# Open-Source_Control_V2_R2.net
KiCad netlist of a schematic drawn in EAGLE
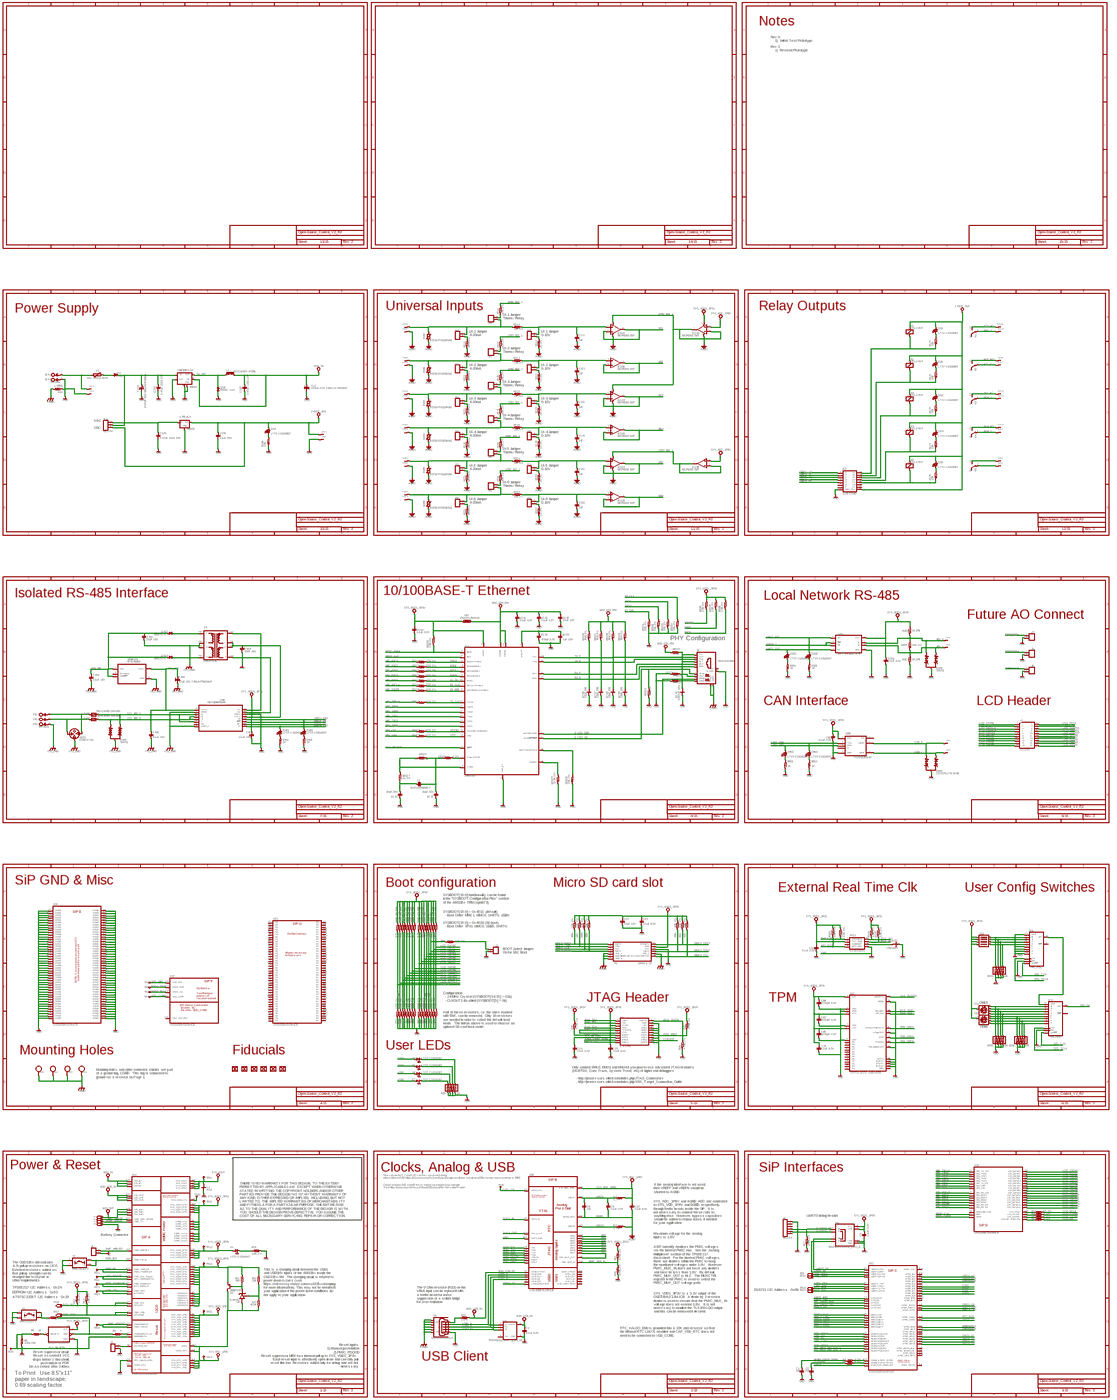
[diagram p0: schematic, sheet 1, overview]
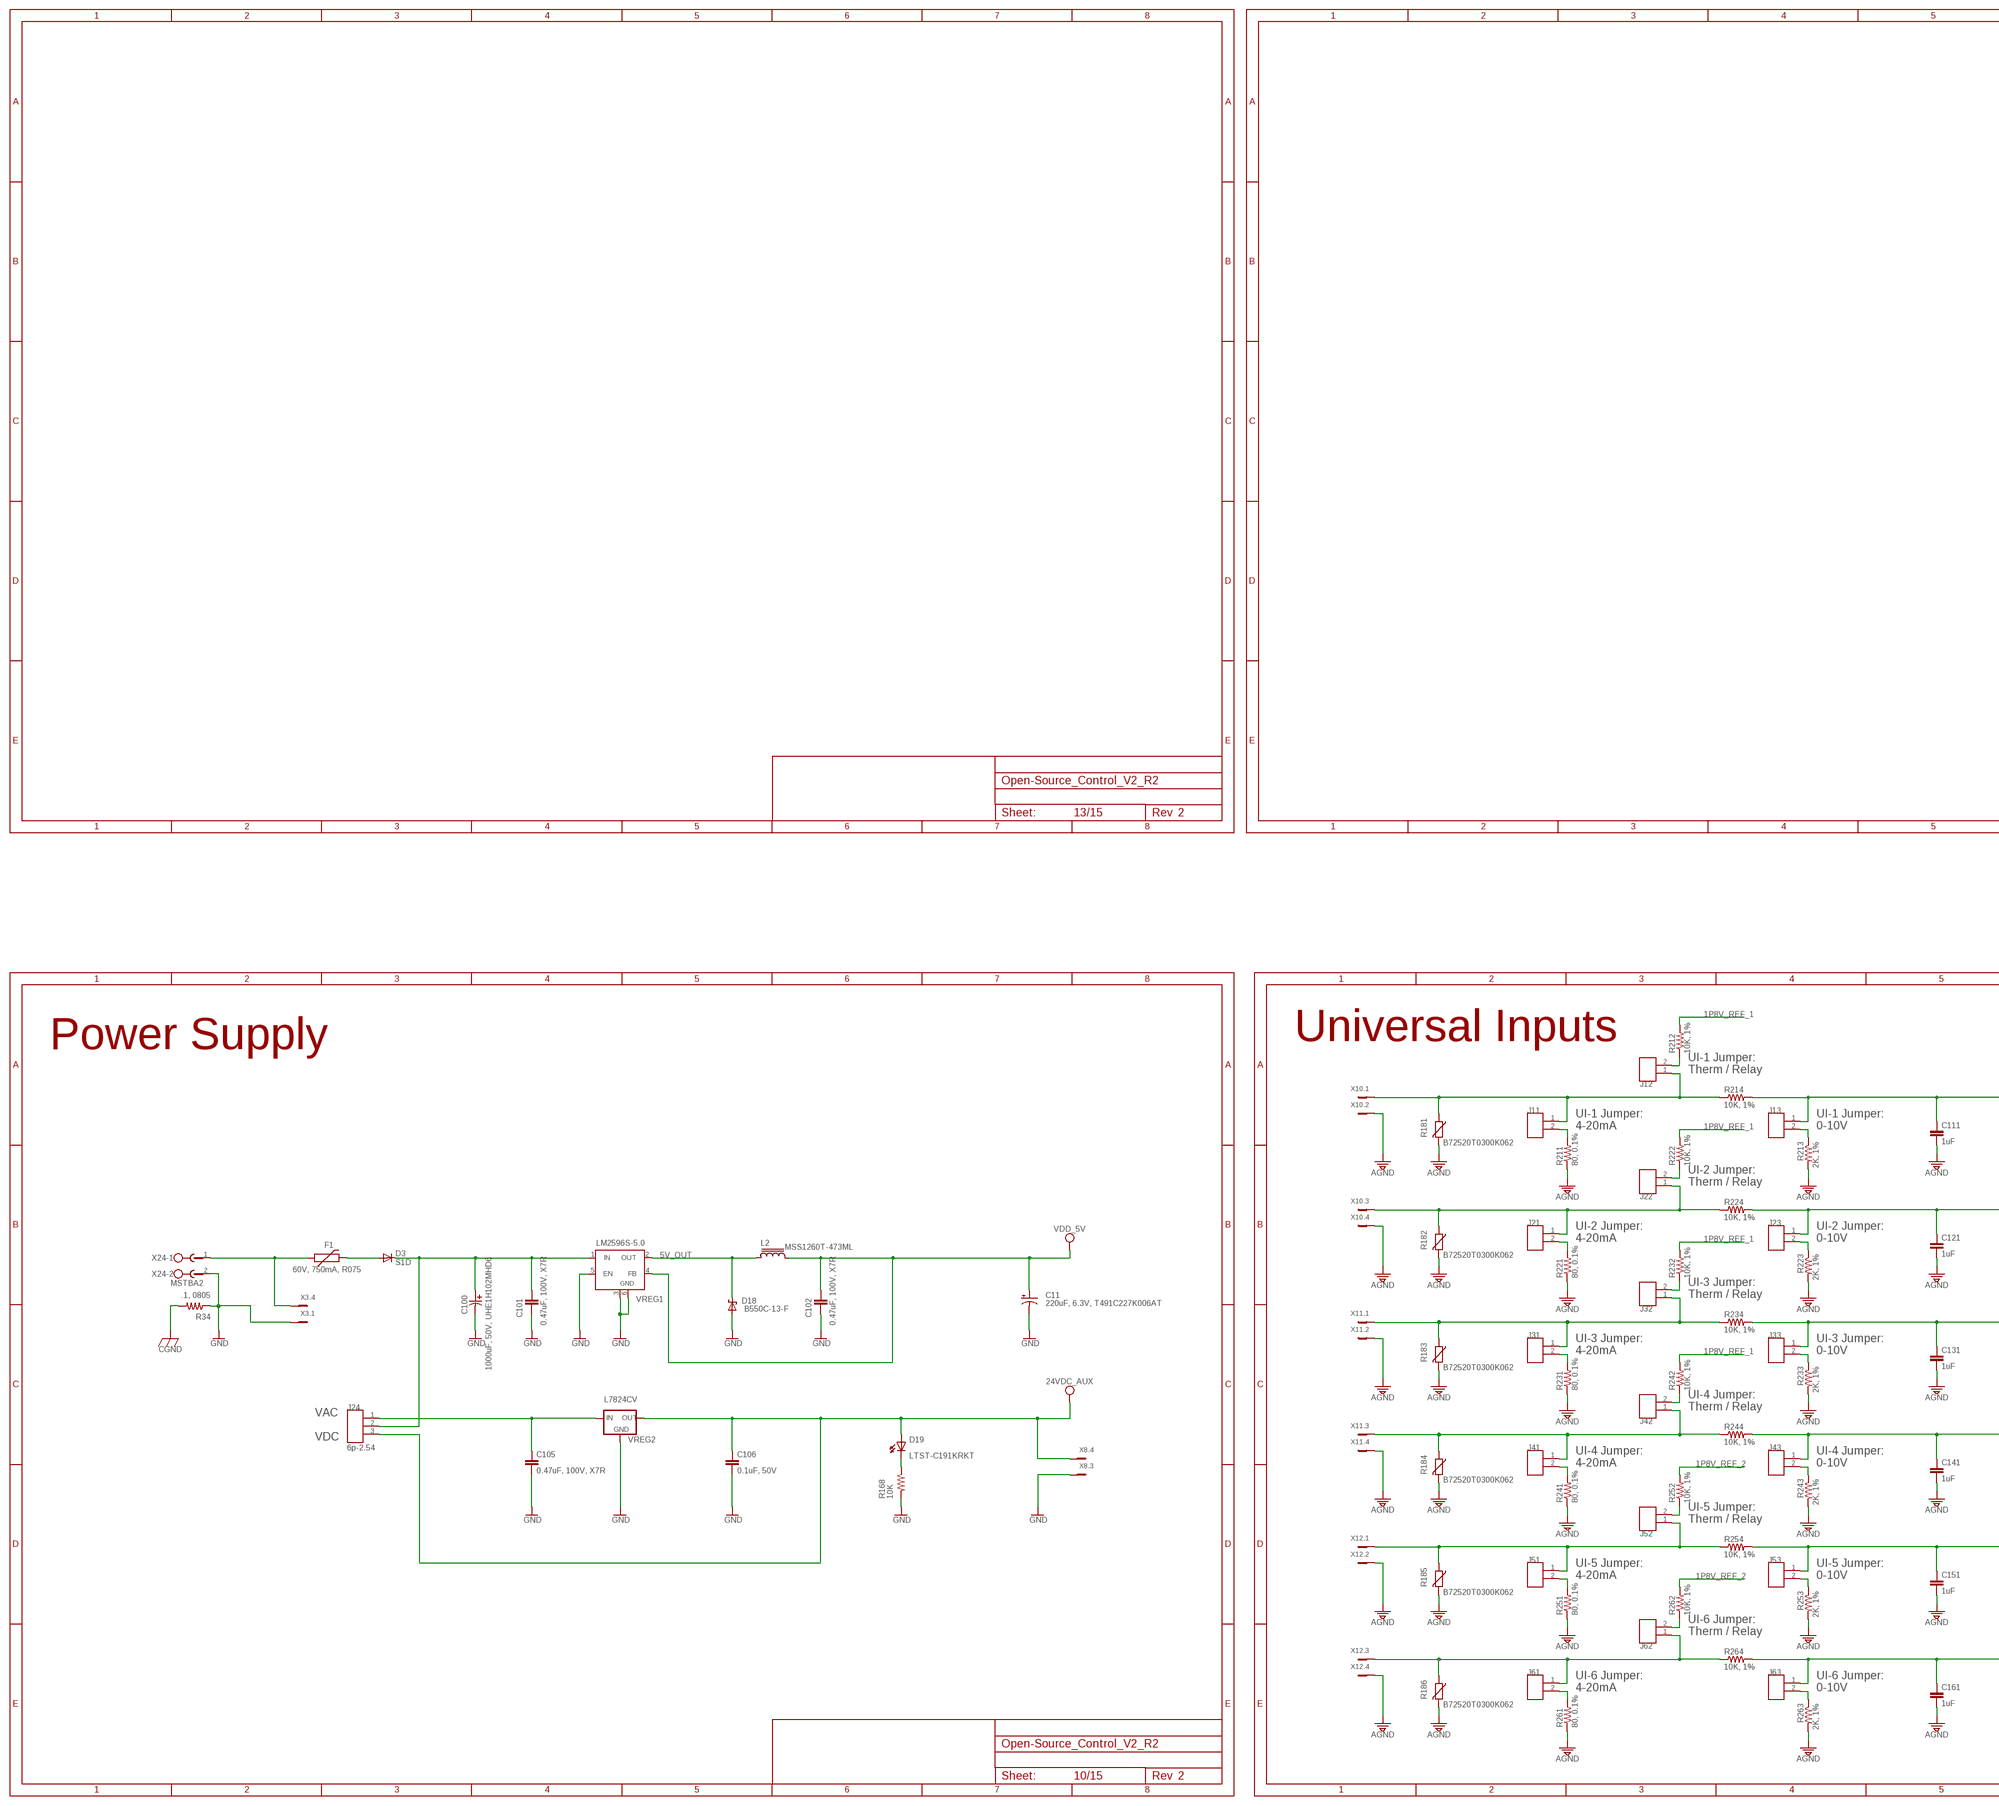
[diagram p1: schematic, sheet 1, part 1 of 6]
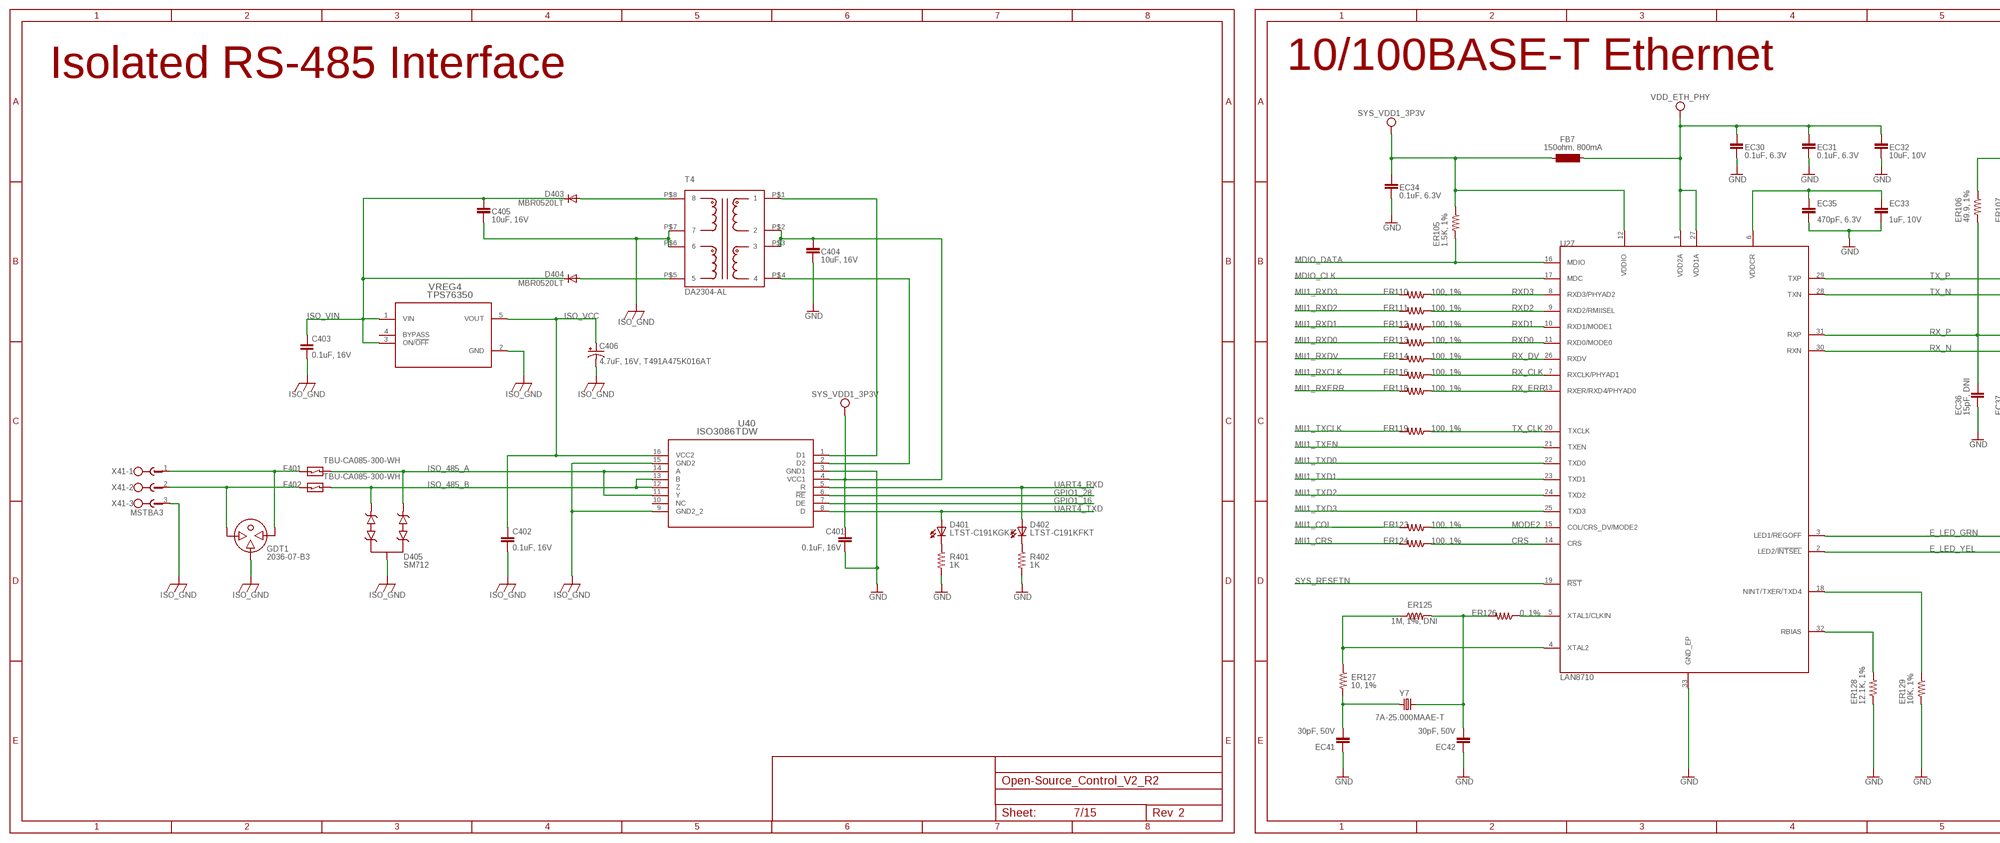
[diagram p2: schematic, sheet 1, part 2 of 6]
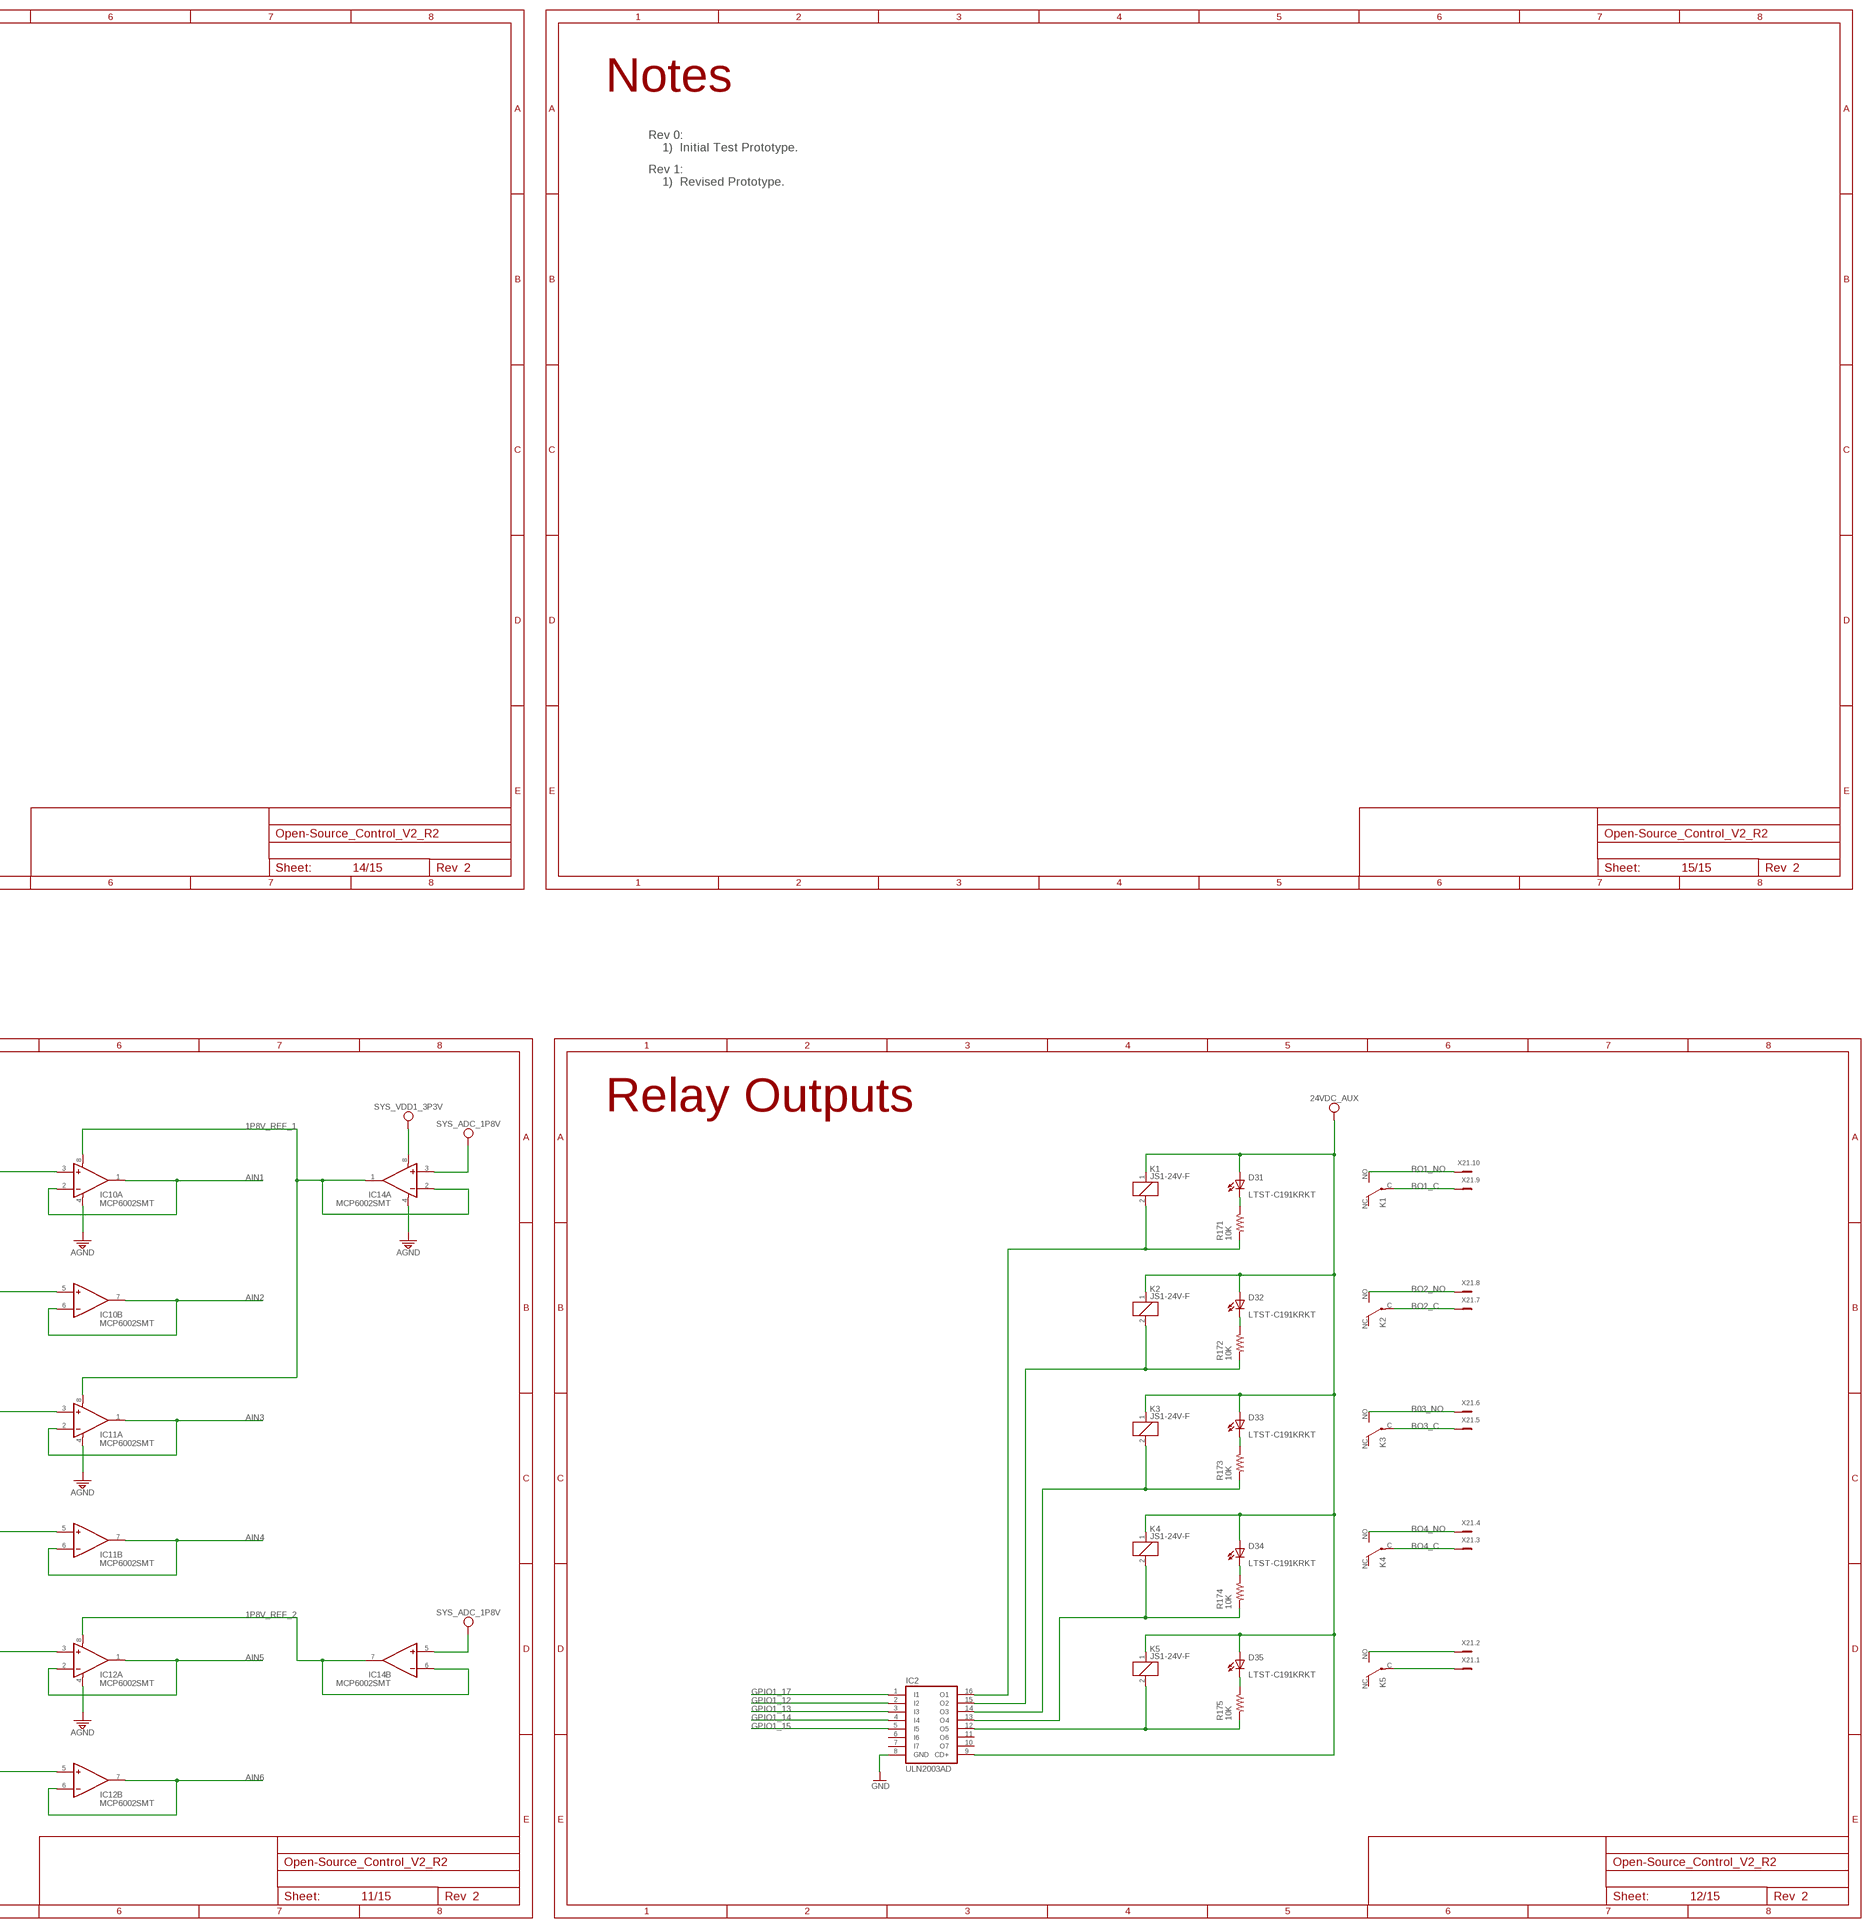
[diagram p3: schematic, sheet 1, part 3 of 6]
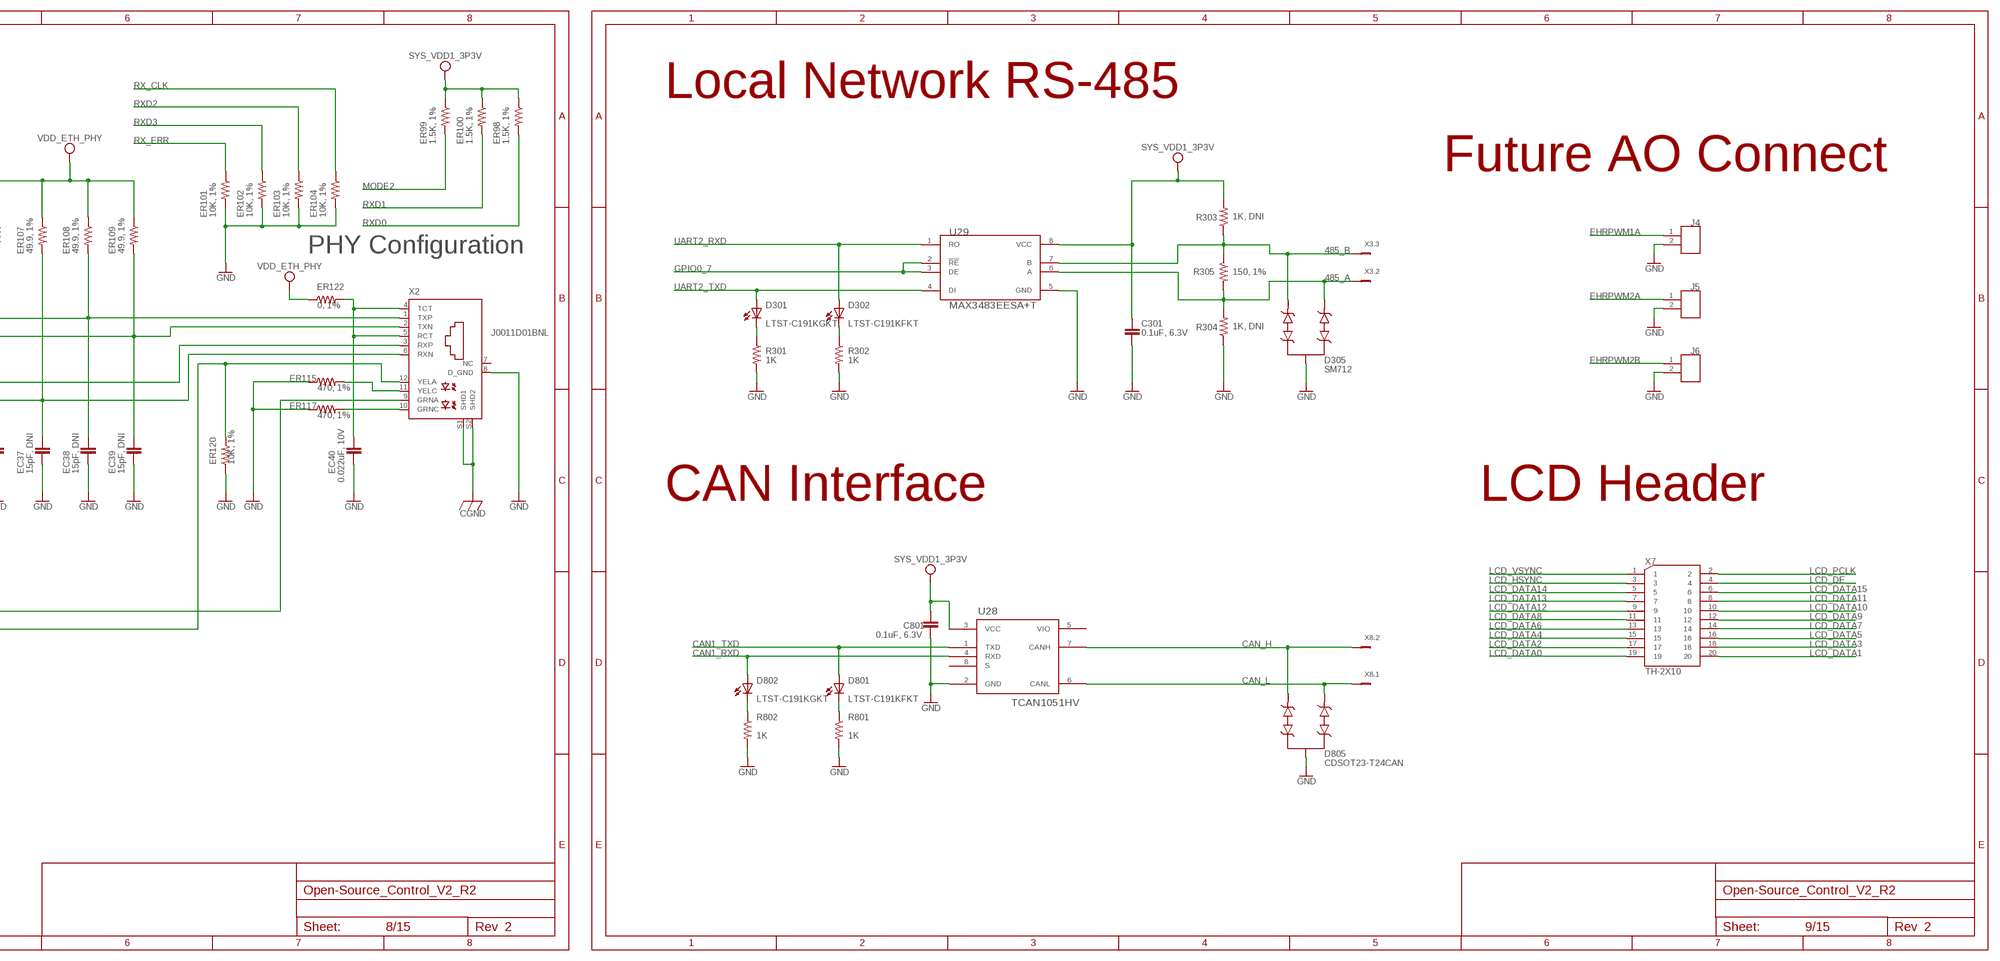
[diagram p4: schematic, sheet 1, part 4 of 6]
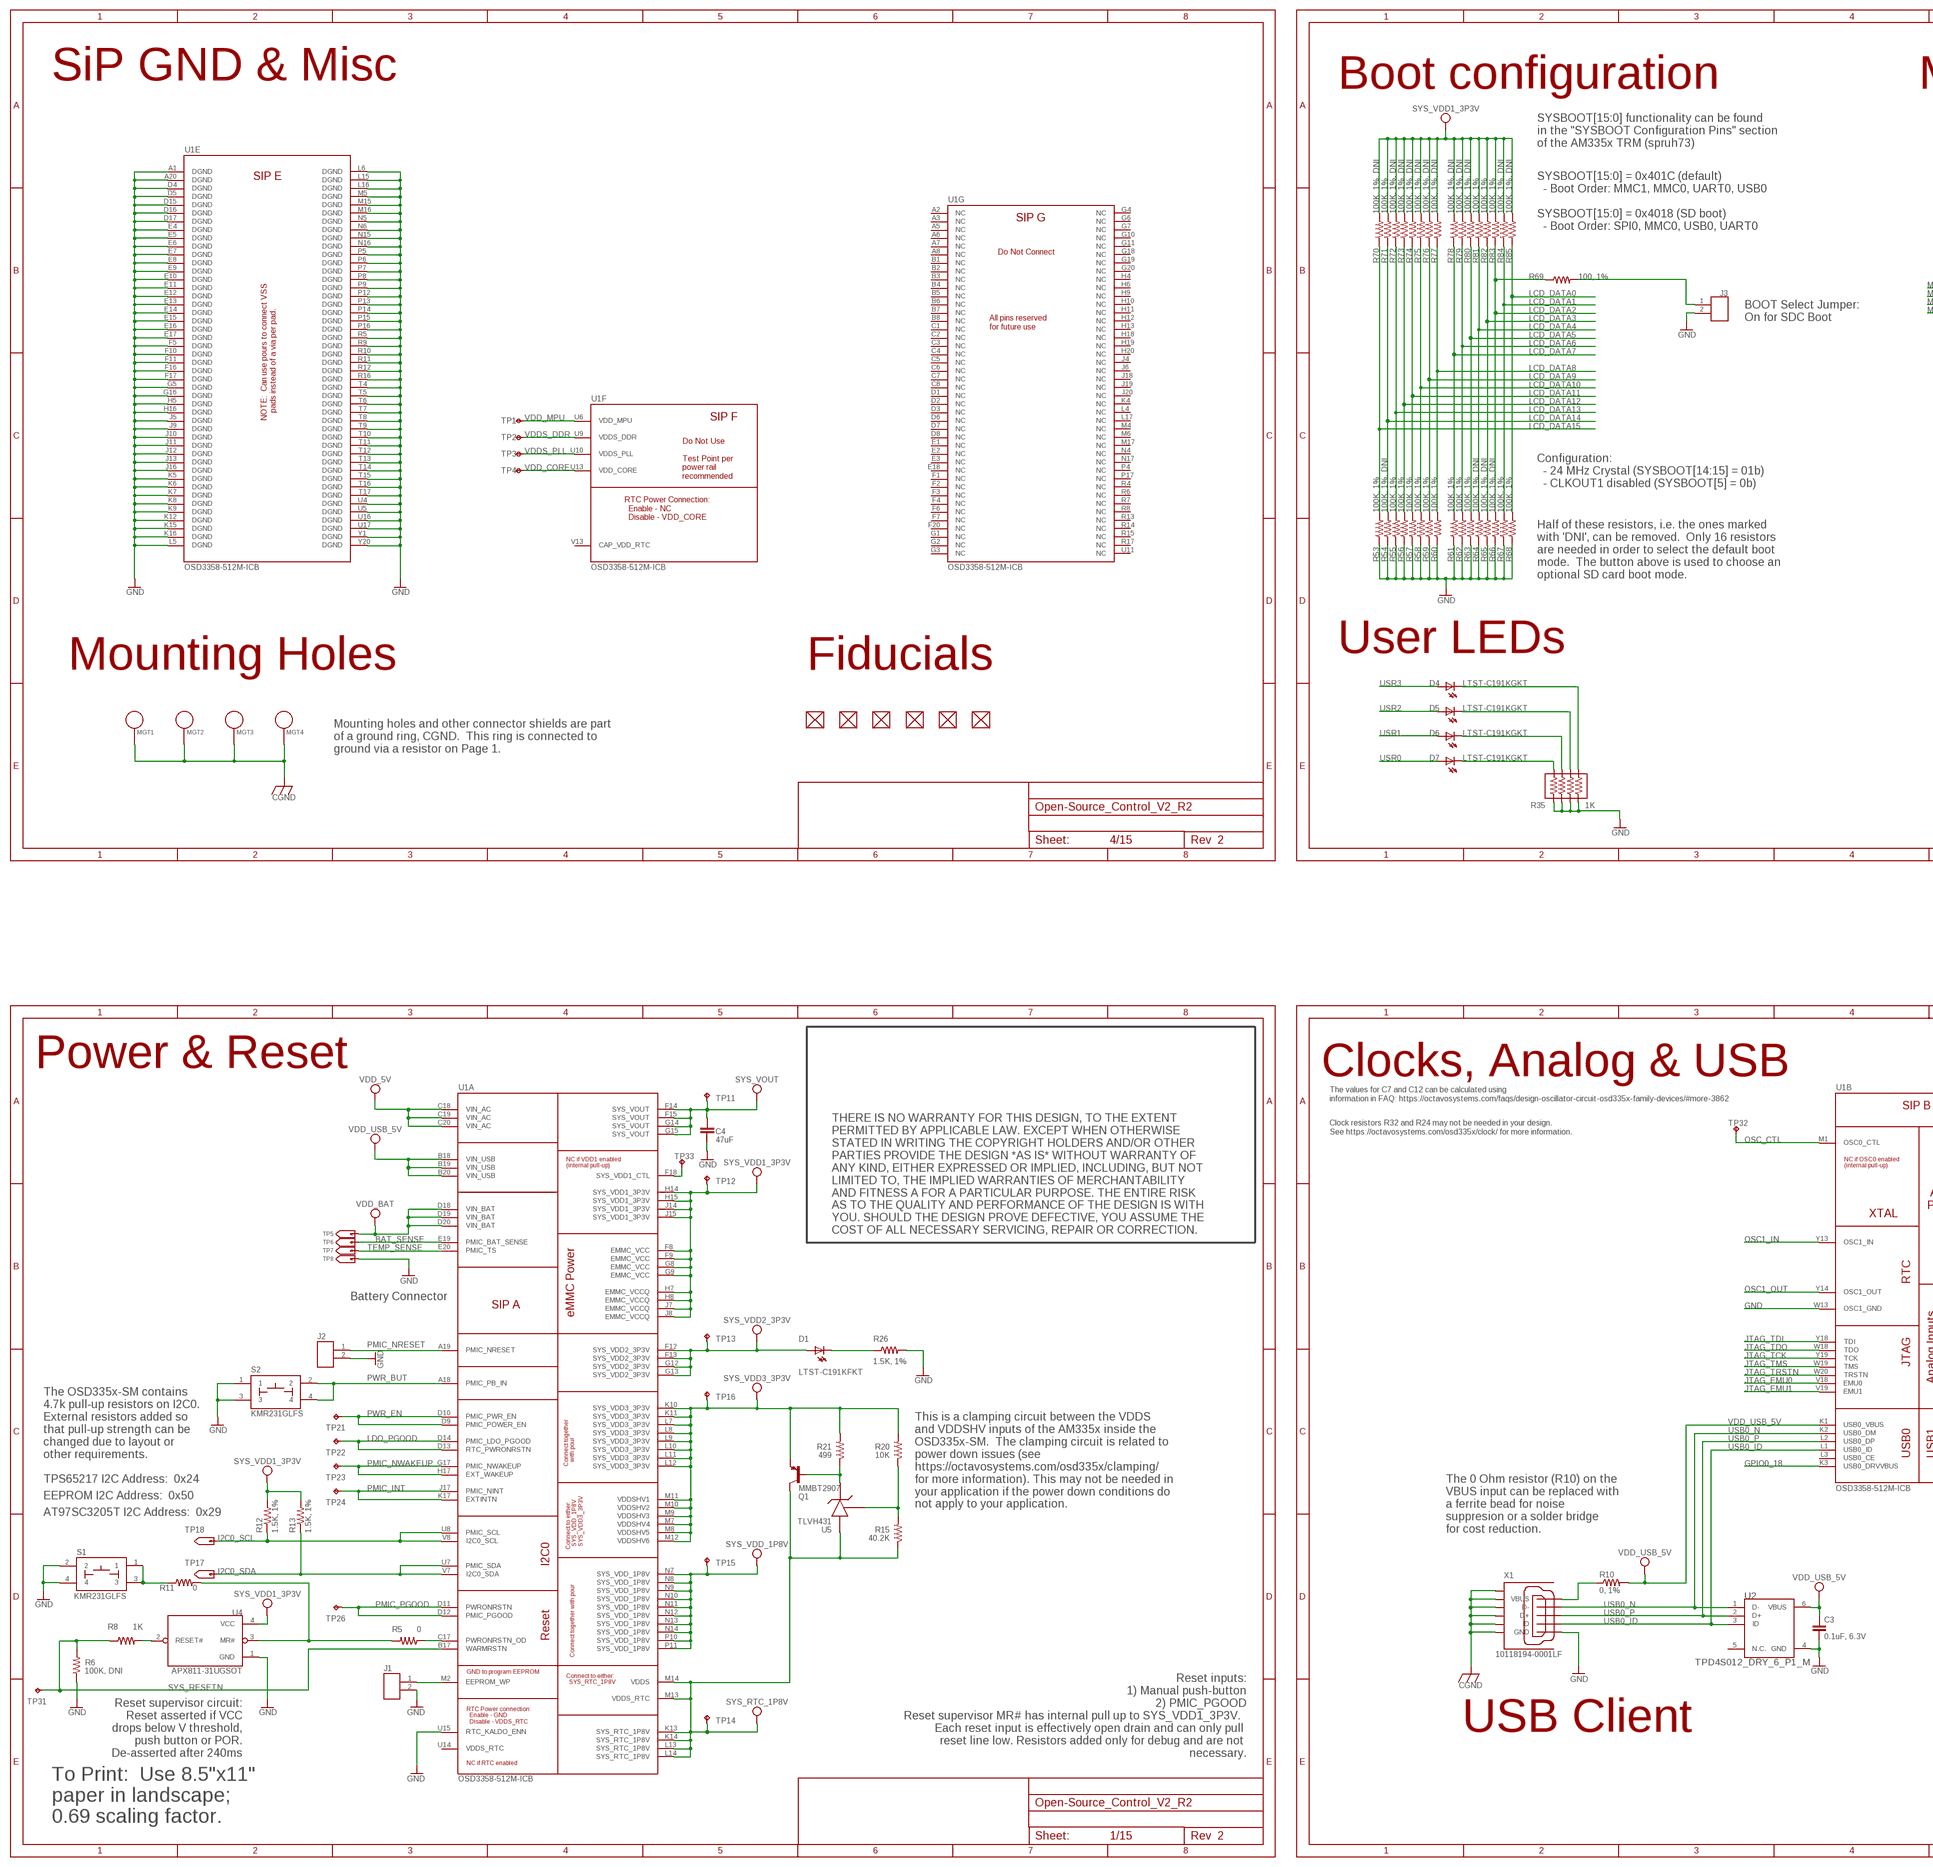
[diagram p5: schematic, sheet 1, part 5 of 6]
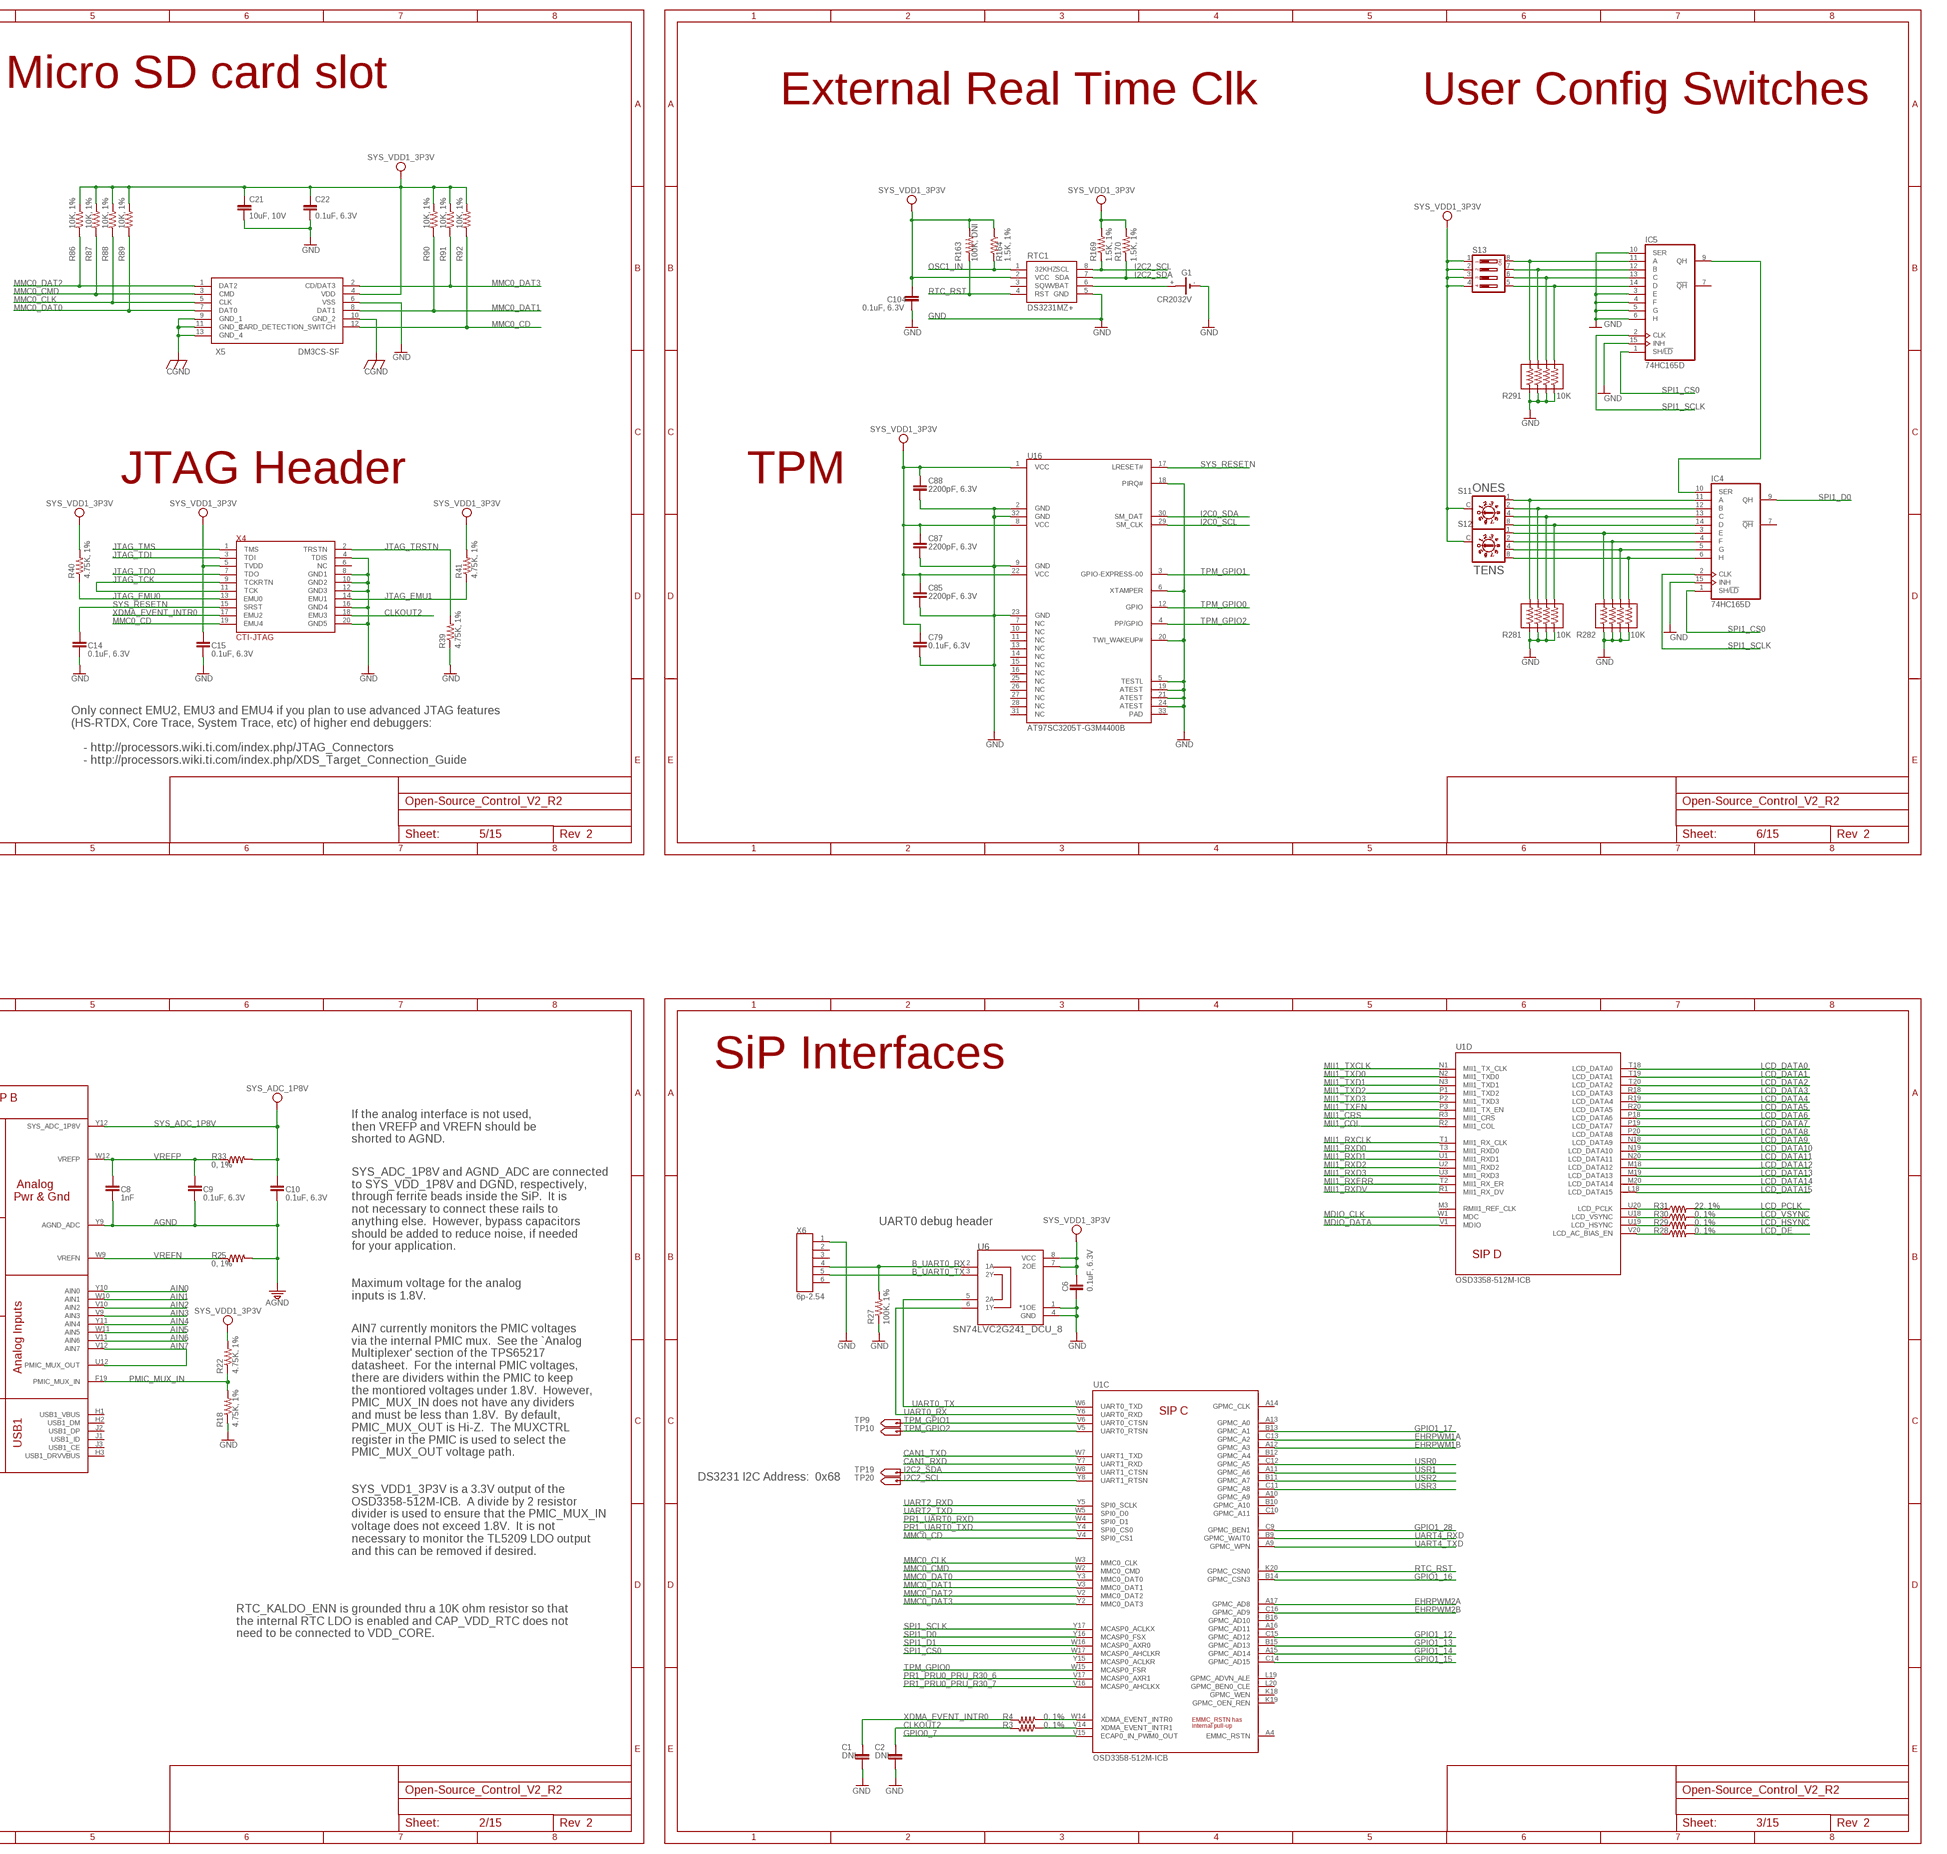
[diagram p6: schematic, sheet 1, part 6 of 6]

(export (version "E")
  (design (tool "Eeschema 10.0.6"))
  (components
    (comp (ref "C1")
      (value "DNI")
      (footprint "eagle-import:C0603")
      (libsource (lib "eagle-import") (part "CC0603"))
    )
    (comp (ref "C2")
      (value "DNI")
      (footprint "eagle-import:C0603")
      (libsource (lib "eagle-import") (part "CC0603"))
    )
    (comp (ref "C3")
      (value "0.1uF, 6.3V")
      (footprint "eagle-import:C0402")
      (libsource (lib "eagle-import") (part "CC0402"))
    )
    (comp (ref "C4")
      (value "47uF")
      (footprint "eagle-import:C0805")
      (libsource (lib "eagle-import") (part "CC0805"))
    )
    (comp (ref "C6")
      (value "0.1uF, 6.3V")
      (footprint "eagle-import:C0402")
      (libsource (lib "eagle-import") (part "CC0402"))
    )
    (comp (ref "C8")
      (value "1nF")
      (footprint "eagle-import:C0402")
      (libsource (lib "eagle-import") (part "CC0402"))
    )
    (comp (ref "C9")
      (value "0.1uF, 6.3V")
      (footprint "eagle-import:C0402")
      (libsource (lib "eagle-import") (part "CC0402"))
    )
    (comp (ref "C10")
      (value "0.1uF, 6.3V")
      (footprint "eagle-import:C0402")
      (libsource (lib "eagle-import") (part "CC0402"))
    )
    (comp (ref "C11")
      (value "220uF, 6.3V, T491C227K006AT")
      (footprint "eagle-import:C_6032-28R")
      (libsource (lib "eagle-import") (part "CPOL-USC/6032-28R"))
    )
    (comp (ref "C14")
      (value "0.1uF, 6.3V")
      (footprint "eagle-import:C0402")
      (libsource (lib "eagle-import") (part "CC0402"))
    )
    (comp (ref "C15")
      (value "0.1uF, 6.3V")
      (footprint "eagle-import:C0402")
      (libsource (lib "eagle-import") (part "CC0402"))
    )
    (comp (ref "C21")
      (value "10uF, 10V")
      (footprint "eagle-import:C0805")
      (libsource (lib "eagle-import") (part "CC0805"))
    )
    (comp (ref "C22")
      (value "0.1uF, 6.3V")
      (footprint "eagle-import:C0402")
      (libsource (lib "eagle-import") (part "CC0402"))
    )
    (comp (ref "C79")
      (value "0.1uF, 6.3V")
      (footprint "eagle-import:C0402")
      (libsource (lib "eagle-import") (part "CC0402"))
    )
    (comp (ref "C85")
      (value "2200pF, 6.3V")
      (footprint "eagle-import:C0402")
      (libsource (lib "eagle-import") (part "CC0402"))
    )
    (comp (ref "C87")
      (value "2200pF, 6.3V")
      (footprint "eagle-import:C0402")
      (libsource (lib "eagle-import") (part "CC0402"))
    )
    (comp (ref "C88")
      (value "2200pF, 6.3V")
      (footprint "eagle-import:C0402")
      (libsource (lib "eagle-import") (part "CC0402"))
    )
    (comp (ref "C100")
      (value "1000uF, 50V, UHE1H102MHD6")
      (footprint "eagle-import:PCAP_16X25-THRU-ELECT")
      (fields (field (name "MANUFACTURER_PART_NUMBER") "UHE1H102MHD6"))
      (libsource (lib "eagle-import") (part "UHE1H102MHD6"))
    )
    (comp (ref "C101")
      (value "0.47uF, 100V, X7R")
      (footprint "eagle-import:1206")
      (libsource (lib "eagle-import") (part "4.7UF-1206-16V-(+80/-20%)"))
    )
    (comp (ref "C102")
      (value "0.47uF, 100V, X7R")
      (footprint "eagle-import:1206")
      (libsource (lib "eagle-import") (part "4.7UF-1206-16V-(+80/-20%)"))
    )
    (comp (ref "C104")
      (value "0.1uF, 6.3V")
      (footprint "eagle-import:C0402")
      (libsource (lib "eagle-import") (part "CC0402"))
    )
    (comp (ref "C105")
      (value "0.47uF, 100V, X7R")
      (footprint "eagle-import:1206")
      (libsource (lib "eagle-import") (part "4.7UF-1206-16V-(+80/-20%)"))
    )
    (comp (ref "C106")
      (value "0.1uF, 50V")
      (footprint "eagle-import:1206")
      (libsource (lib "eagle-import") (part "4.7UF-1206-16V-(+80/-20%)"))
    )
    (comp (ref "C111")
      (value "1uF")
      (footprint "eagle-import:C0805")
      (libsource (lib "eagle-import") (part "CC0805"))
    )
    (comp (ref "C121")
      (value "1uF")
      (footprint "eagle-import:C0805")
      (libsource (lib "eagle-import") (part "CC0805"))
    )
    (comp (ref "C131")
      (value "1uF")
      (footprint "eagle-import:C0805")
      (libsource (lib "eagle-import") (part "CC0805"))
    )
    (comp (ref "C141")
      (value "1uF")
      (footprint "eagle-import:C0805")
      (libsource (lib "eagle-import") (part "CC0805"))
    )
    (comp (ref "C151")
      (value "1uF")
      (footprint "eagle-import:C0805")
      (libsource (lib "eagle-import") (part "CC0805"))
    )
    (comp (ref "C161")
      (value "1uF")
      (footprint "eagle-import:C0805")
      (libsource (lib "eagle-import") (part "CC0805"))
    )
    (comp (ref "C301")
      (value "0.1uF, 6.3V")
      (footprint "eagle-import:C0402")
      (libsource (lib "eagle-import") (part "CC0402"))
    )
    (comp (ref "C401")
      (value "0.1uF, 16V")
      (footprint "eagle-import:C0402")
      (libsource (lib "eagle-import") (part "CC0402"))
    )
    (comp (ref "C402")
      (value "0.1uF, 16V")
      (footprint "eagle-import:C0402")
      (libsource (lib "eagle-import") (part "CC0402"))
    )
    (comp (ref "C403")
      (value "0.1uF, 16V")
      (footprint "eagle-import:C0402")
      (libsource (lib "eagle-import") (part "CC0402"))
    )
    (comp (ref "C404")
      (value "10uF, 16V")
      (footprint "eagle-import:C0805")
      (libsource (lib "eagle-import") (part "CC0805"))
    )
    (comp (ref "C405")
      (value "10uF, 16V")
      (footprint "eagle-import:C0805")
      (libsource (lib "eagle-import") (part "CC0805"))
    )
    (comp (ref "C406")
      (value "4.7uF, 16V, T491A475K016AT")
      (footprint "eagle-import:A_3216-18R")
      (libsource (lib "eagle-import") (part "CPOL-USA/3216-18R"))
    )
    (comp (ref "C801")
      (value "0.1uF, 6.3V")
      (footprint "eagle-import:C0402")
      (libsource (lib "eagle-import") (part "CC0402"))
    )
    (comp (ref "D1")
      (value "LTST-C191KFKT")
      (footprint "eagle-import:EIA-STD")
      (libsource (lib "eagle-import") (part "LTST-C191KFKTLED_EIA-STD"))
    )
    (comp (ref "D3")
      (value "S1D")
      (footprint "eagle-import:SMA")
      (libsource (lib "eagle-import") (part "S1M"))
    )
    (comp (ref "D4")
      (value "LTST-C191KGKT")
      (footprint "eagle-import:EIA-STD")
      (libsource (lib "eagle-import") (part "LTST-C191KGKTLED_EIA-STD"))
    )
    (comp (ref "D5")
      (value "LTST-C191KGKT")
      (footprint "eagle-import:EIA-STD")
      (libsource (lib "eagle-import") (part "LTST-C191KGKTLED_EIA-STD"))
    )
    (comp (ref "D6")
      (value "LTST-C191KGKT")
      (footprint "eagle-import:EIA-STD")
      (libsource (lib "eagle-import") (part "LTST-C191KGKTLED_EIA-STD"))
    )
    (comp (ref "D7")
      (value "LTST-C191KGKT")
      (footprint "eagle-import:EIA-STD")
      (libsource (lib "eagle-import") (part "LTST-C191KGKTLED_EIA-STD"))
    )
    (comp (ref "D18")
      (value "B550C-13-F")
      (footprint "eagle-import:SMC")
      (libsource (lib "eagle-import") (part "B520C-13-F"))
    )
    (comp (ref "D19")
      (value "LTST-C191KRKT")
      (footprint "eagle-import:EIA-STD")
      (libsource (lib "eagle-import") (part "LTST-C191KRKTLED_EIA-STD"))
    )
    (comp (ref "D31")
      (value "LTST-C191KRKT")
      (footprint "eagle-import:EIA-STD")
      (libsource (lib "eagle-import") (part "LTST-C191KRKTLED_EIA-STD"))
    )
    (comp (ref "D32")
      (value "LTST-C191KRKT")
      (footprint "eagle-import:EIA-STD")
      (libsource (lib "eagle-import") (part "LTST-C191KRKTLED_EIA-STD"))
    )
    (comp (ref "D33")
      (value "LTST-C191KRKT")
      (footprint "eagle-import:EIA-STD")
      (libsource (lib "eagle-import") (part "LTST-C191KRKTLED_EIA-STD"))
    )
    (comp (ref "D34")
      (value "LTST-C191KRKT")
      (footprint "eagle-import:EIA-STD")
      (libsource (lib "eagle-import") (part "LTST-C191KRKTLED_EIA-STD"))
    )
    (comp (ref "D35")
      (value "LTST-C191KRKT")
      (footprint "eagle-import:EIA-STD")
      (libsource (lib "eagle-import") (part "LTST-C191KRKTLED_EIA-STD"))
    )
    (comp (ref "D301")
      (value "LTST-C191KGKT")
      (footprint "eagle-import:EIA-STD")
      (libsource (lib "eagle-import") (part "LTST-C191KGKTLED_EIA-STD"))
    )
    (comp (ref "D302")
      (value "LTST-C191KFKT")
      (footprint "eagle-import:EIA-STD")
      (libsource (lib "eagle-import") (part "LTST-C191KFKTLED_EIA-STD"))
    )
    (comp (ref "D305")
      (value "SM712")
      (footprint "eagle-import:SOT23-3")
      (libsource (lib "eagle-import") (part "SM712"))
    )
    (comp (ref "D401")
      (value "LTST-C191KGKT")
      (footprint "eagle-import:EIA-STD")
      (libsource (lib "eagle-import") (part "LTST-C191KGKTLED_EIA-STD"))
    )
    (comp (ref "D402")
      (value "LTST-C191KFKT")
      (footprint "eagle-import:EIA-STD")
      (libsource (lib "eagle-import") (part "LTST-C191KFKTLED_EIA-STD"))
    )
    (comp (ref "D403")
      (value "MBR0520LT")
      (footprint "eagle-import:SOD123")
      (libsource (lib "eagle-import") (part "MBR0520LT"))
    )
    (comp (ref "D404")
      (value "MBR0520LT")
      (footprint "eagle-import:SOD123")
      (libsource (lib "eagle-import") (part "MBR0520LT"))
    )
    (comp (ref "D405")
      (value "SM712")
      (footprint "eagle-import:SOT23-3")
      (libsource (lib "eagle-import") (part "SM712"))
    )
    (comp (ref "D801")
      (value "LTST-C191KFKT")
      (footprint "eagle-import:EIA-STD")
      (libsource (lib "eagle-import") (part "LTST-C191KFKTLED_EIA-STD"))
    )
    (comp (ref "D802")
      (value "LTST-C191KGKT")
      (footprint "eagle-import:EIA-STD")
      (libsource (lib "eagle-import") (part "LTST-C191KGKTLED_EIA-STD"))
    )
    (comp (ref "D805")
      (value "CDSOT23-T24CAN")
      (footprint "eagle-import:SOT23-3")
      (libsource (lib "eagle-import") (part "CDSOT23-T24CAN"))
    )
    (comp (ref "EC30")
      (value "0.1uF, 6.3V")
      (footprint "eagle-import:C0402")
      (libsource (lib "eagle-import") (part "CC0402"))
    )
    (comp (ref "EC31")
      (value "0.1uF, 6.3V")
      (footprint "eagle-import:C0402")
      (libsource (lib "eagle-import") (part "CC0402"))
    )
    (comp (ref "EC32")
      (value "10uF, 10V")
      (footprint "eagle-import:C0805")
      (libsource (lib "eagle-import") (part "CC0805"))
    )
    (comp (ref "EC33")
      (value "1uF, 10V")
      (footprint "eagle-import:C0402")
      (libsource (lib "eagle-import") (part "CC0402"))
    )
    (comp (ref "EC34")
      (value "0.1uF, 6.3V")
      (footprint "eagle-import:C0402")
      (libsource (lib "eagle-import") (part "CC0402"))
    )
    (comp (ref "EC35")
      (value "470pF, 6.3V")
      (footprint "eagle-import:C0402")
      (libsource (lib "eagle-import") (part "CC0402"))
    )
    (comp (ref "EC36")
      (value "15pF, DNI")
      (footprint "eagle-import:C0402")
      (libsource (lib "eagle-import") (part "CC0402"))
    )
    (comp (ref "EC37")
      (value "15pF, DNI")
      (footprint "eagle-import:C0402")
      (libsource (lib "eagle-import") (part "CC0402"))
    )
    (comp (ref "EC38")
      (value "15pF, DNI")
      (footprint "eagle-import:C0402")
      (libsource (lib "eagle-import") (part "CC0402"))
    )
    (comp (ref "EC39")
      (value "15pF, DNI")
      (footprint "eagle-import:C0402")
      (libsource (lib "eagle-import") (part "CC0402"))
    )
    (comp (ref "EC40")
      (value "0.022uF, 10V")
      (footprint "eagle-import:C0402")
      (libsource (lib "eagle-import") (part "CC0402"))
    )
    (comp (ref "EC41")
      (value "30pF, 50V")
      (footprint "eagle-import:C0402")
      (libsource (lib "eagle-import") (part "CC0402"))
    )
    (comp (ref "EC42")
      (value "30pF, 50V")
      (footprint "eagle-import:C0402")
      (libsource (lib "eagle-import") (part "CC0402"))
    )
    (comp (ref "ER98")
      (value "1.5K, 1%")
      (footprint "eagle-import:R0402")
      (libsource (lib "eagle-import") (part "OSD3358-SM-RED Platform_R-US_R0402"))
    )
    (comp (ref "ER99")
      (value "1.5K, 1%")
      (footprint "eagle-import:R0402")
      (libsource (lib "eagle-import") (part "OSD3358-SM-RED Platform_R-US_R0402"))
    )
    (comp (ref "ER100")
      (value "1.5K, 1%")
      (footprint "eagle-import:R0402")
      (libsource (lib "eagle-import") (part "OSD3358-SM-RED Platform_R-US_R0402"))
    )
    (comp (ref "ER101")
      (value "10K, 1%")
      (footprint "eagle-import:R0402")
      (libsource (lib "eagle-import") (part "OSD3358-SM-RED Platform_R-US_R0402"))
    )
    (comp (ref "ER102")
      (value "10K, 1%")
      (footprint "eagle-import:R0402")
      (libsource (lib "eagle-import") (part "OSD3358-SM-RED Platform_R-US_R0402"))
    )
    (comp (ref "ER103")
      (value "10K, 1%")
      (footprint "eagle-import:R0402")
      (libsource (lib "eagle-import") (part "OSD3358-SM-RED Platform_R-US_R0402"))
    )
    (comp (ref "ER104")
      (value "10K, 1%")
      (footprint "eagle-import:R0402")
      (libsource (lib "eagle-import") (part "OSD3358-SM-RED Platform_R-US_R0402"))
    )
    (comp (ref "ER105")
      (value "1.5K, 1%")
      (footprint "eagle-import:R0402")
      (libsource (lib "eagle-import") (part "OSD3358-SM-RED Platform_R-US_R0402"))
    )
    (comp (ref "ER106")
      (value "49.9, 1%")
      (footprint "eagle-import:R0402")
      (libsource (lib "eagle-import") (part "OSD3358-SM-RED Platform_R-US_R0402"))
    )
    (comp (ref "ER107")
      (value "49.9, 1%")
      (footprint "eagle-import:R0402")
      (libsource (lib "eagle-import") (part "OSD3358-SM-RED Platform_R-US_R0402"))
    )
    (comp (ref "ER108")
      (value "49.9, 1%")
      (footprint "eagle-import:R0402")
      (libsource (lib "eagle-import") (part "OSD3358-SM-RED Platform_R-US_R0402"))
    )
    (comp (ref "ER109")
      (value "49.9, 1%")
      (footprint "eagle-import:R0402")
      (libsource (lib "eagle-import") (part "OSD3358-SM-RED Platform_R-US_R0402"))
    )
    (comp (ref "ER110")
      (value "100, 1%")
      (footprint "eagle-import:R0402")
      (libsource (lib "eagle-import") (part "OSD3358-SM-RED Platform_R-US_R0402"))
    )
    (comp (ref "ER111")
      (value "100, 1%")
      (footprint "eagle-import:R0402")
      (libsource (lib "eagle-import") (part "OSD3358-SM-RED Platform_R-US_R0402"))
    )
    (comp (ref "ER112")
      (value "100, 1%")
      (footprint "eagle-import:R0402")
      (libsource (lib "eagle-import") (part "OSD3358-SM-RED Platform_R-US_R0402"))
    )
    (comp (ref "ER113")
      (value "100, 1%")
      (footprint "eagle-import:R0402")
      (libsource (lib "eagle-import") (part "OSD3358-SM-RED Platform_R-US_R0402"))
    )
    (comp (ref "ER114")
      (value "100, 1%")
      (footprint "eagle-import:R0402")
      (libsource (lib "eagle-import") (part "OSD3358-SM-RED Platform_R-US_R0402"))
    )
    (comp (ref "ER115")
      (value "470, 1%")
      (footprint "eagle-import:R0402")
      (libsource (lib "eagle-import") (part "OSD3358-SM-RED Platform_R-US_R0402"))
    )
    (comp (ref "ER116")
      (value "100, 1%")
      (footprint "eagle-import:R0402")
      (libsource (lib "eagle-import") (part "OSD3358-SM-RED Platform_R-US_R0402"))
    )
    (comp (ref "ER117")
      (value "470, 1%")
      (footprint "eagle-import:R0402")
      (libsource (lib "eagle-import") (part "OSD3358-SM-RED Platform_R-US_R0402"))
    )
    (comp (ref "ER118")
      (value "100, 1%")
      (footprint "eagle-import:R0402")
      (libsource (lib "eagle-import") (part "OSD3358-SM-RED Platform_R-US_R0402"))
    )
    (comp (ref "ER119")
      (value "100, 1%")
      (footprint "eagle-import:R0402")
      (libsource (lib "eagle-import") (part "OSD3358-SM-RED Platform_R-US_R0402"))
    )
    (comp (ref "ER120")
      (value "10K, 1%")
      (footprint "eagle-import:R0402")
      (libsource (lib "eagle-import") (part "OSD3358-SM-RED Platform_R-US_R0402"))
    )
    (comp (ref "ER122")
      (value "0, 1%")
      (footprint "eagle-import:R0402")
      (libsource (lib "eagle-import") (part "OSD3358-SM-RED Platform_R-US_R0402"))
    )
    (comp (ref "ER123")
      (value "100, 1%")
      (footprint "eagle-import:R0402")
      (libsource (lib "eagle-import") (part "OSD3358-SM-RED Platform_R-US_R0402"))
    )
    (comp (ref "ER124")
      (value "100, 1%")
      (footprint "eagle-import:R0402")
      (libsource (lib "eagle-import") (part "OSD3358-SM-RED Platform_R-US_R0402"))
    )
    (comp (ref "ER125")
      (value "1M, 1%, DNI")
      (footprint "eagle-import:R0402")
      (libsource (lib "eagle-import") (part "OSD3358-SM-RED Platform_R-US_R0402"))
    )
    (comp (ref "ER126")
      (value "0, 1%")
      (footprint "eagle-import:R0402")
      (libsource (lib "eagle-import") (part "OSD3358-SM-RED Platform_R-US_R0402"))
    )
    (comp (ref "ER127")
      (value "10, 1%")
      (footprint "eagle-import:R0402")
      (libsource (lib "eagle-import") (part "OSD3358-SM-RED Platform_R-US_R0402"))
    )
    (comp (ref "ER128")
      (value "12.1K, 1%")
      (footprint "eagle-import:R0402")
      (libsource (lib "eagle-import") (part "OSD3358-SM-RED Platform_R-US_R0402"))
    )
    (comp (ref "ER129")
      (value "10K, 1%")
      (footprint "eagle-import:R0402")
      (libsource (lib "eagle-import") (part "OSD3358-SM-RED Platform_R-US_R0402"))
    )
    (comp (ref "F1")
      (value "60V, 750mA, R075")
      (footprint "eagle-import:PTH")
      (libsource (lib "eagle-import") (part "PPTC_PTH"))
    )
    (comp (ref "F401")
      (value "TBU-CA085-300-WH")
      (footprint "eagle-import:TBU-CA")
      (libsource (lib "eagle-import") (part "TBU-CA085-300-WH"))
    )
    (comp (ref "F402")
      (value "TBU-CA085-300-WH")
      (footprint "eagle-import:TBU-CA")
      (libsource (lib "eagle-import") (part "TBU-CA085-300-WH"))
    )
    (comp (ref "FB7")
      (value "150ohm, 800mA")
      (footprint "eagle-import:C0805")
      (libsource (lib "eagle-import") (part "BLM21AG151SN1DFB_0805"))
    )
    (comp (ref "FUD1")
      (value "FIDUCIAL")
      (footprint "eagle-import:FIDUCIAL_40MIL")
      (libsource (lib "eagle-import") (part "FIDUCIAL"))
    )
    (comp (ref "FUD2")
      (value "FIDUCIAL")
      (footprint "eagle-import:FIDUCIAL_40MIL")
      (libsource (lib "eagle-import") (part "FIDUCIAL"))
    )
    (comp (ref "FUD3")
      (value "FIDUCIAL")
      (footprint "eagle-import:FIDUCIAL_40MIL")
      (libsource (lib "eagle-import") (part "FIDUCIAL"))
    )
    (comp (ref "FUD4")
      (value "FIDUCIAL")
      (footprint "eagle-import:FIDUCIAL_40MIL")
      (libsource (lib "eagle-import") (part "FIDUCIAL"))
    )
    (comp (ref "FUD5")
      (value "FIDUCIAL")
      (footprint "eagle-import:FIDUCIAL_40MIL")
      (libsource (lib "eagle-import") (part "FIDUCIAL"))
    )
    (comp (ref "FUD6")
      (value "FIDUCIAL")
      (footprint "eagle-import:FIDUCIAL_40MIL")
      (libsource (lib "eagle-import") (part "FIDUCIAL"))
    )
    (comp (ref "G1")
      (value "CR2032V")
      (footprint "eagle-import:CR2032V")
      (libsource (lib "eagle-import") (part "CR2032V"))
    )
    (comp (ref "GDT1")
      (value "2036-07-B3")
      (footprint "eagle-import:2036-XX-B3")
      (libsource (lib "eagle-import") (part "2036-09-B3"))
    )
    (comp (ref "IC2")
      (value "ULN2003AD")
      (footprint "eagle-import:SO16")
      (libsource (lib "eagle-import") (part "ULN2003AD"))
    )
    (comp (ref "IC4")
      (value "74HC165D")
      (footprint "eagle-import:SO16")
      (libsource (lib "eagle-import") (part "74165DHC"))
    )
    (comp (ref "IC5")
      (value "74HC165D")
      (footprint "eagle-import:SO16")
      (libsource (lib "eagle-import") (part "74165DHC"))
    )
    (comp (ref "IC10")
      (value "MCP6002SMT")
      (footprint "eagle-import:SOIC8")
      (libsource (lib "eagle-import") (part "MCP6002SMT"))
    )
    (comp (ref "IC11")
      (value "MCP6002SMT")
      (footprint "eagle-import:SOIC8")
      (libsource (lib "eagle-import") (part "MCP6002SMT"))
    )
    (comp (ref "IC12")
      (value "MCP6002SMT")
      (footprint "eagle-import:SOIC8")
      (libsource (lib "eagle-import") (part "MCP6002SMT"))
    )
    (comp (ref "IC14")
      (value "MCP6002SMT")
      (footprint "eagle-import:SOIC8")
      (libsource (lib "eagle-import") (part "MCP6002SMT"))
    )
    (comp (ref "J1")
      (value "826646-2")
      (footprint "eagle-import:H2-2.54")
      (libsource (lib "eagle-import") (part "826646-2"))
    )
    (comp (ref "J2")
      (value "826646-2")
      (footprint "eagle-import:H2-2.54")
      (libsource (lib "eagle-import") (part "OSD3358-SM-RED Platform_826646-2"))
    )
    (comp (ref "J3")
      (value "826646-2")
      (footprint "eagle-import:H2-2.54")
      (libsource (lib "eagle-import") (part "OSD3358-SM-RED Platform_826646-2"))
    )
    (comp (ref "J4")
      (value "826646-2")
      (footprint "eagle-import:H2-2.54")
      (libsource (lib "eagle-import") (part "OSD3358-SM-RED Platform_826646-2"))
    )
    (comp (ref "J5")
      (value "826646-2")
      (footprint "eagle-import:H2-2.54")
      (libsource (lib "eagle-import") (part "OSD3358-SM-RED Platform_826646-2"))
    )
    (comp (ref "J6")
      (value "826646-2")
      (footprint "eagle-import:H2-2.54")
      (libsource (lib "eagle-import") (part "OSD3358-SM-RED Platform_826646-2"))
    )
    (comp (ref "J11")
      (value "826646-2")
      (footprint "eagle-import:H2-2.54")
      (libsource (lib "eagle-import") (part "OSD3358-SM-RED Platform_826646-2"))
    )
    (comp (ref "J12")
      (value "826646-2")
      (footprint "eagle-import:H2-2.54")
      (libsource (lib "eagle-import") (part "OSD3358-SM-RED Platform_826646-2"))
    )
    (comp (ref "J13")
      (value "826646-2")
      (footprint "eagle-import:H2-2.54")
      (libsource (lib "eagle-import") (part "OSD3358-SM-RED Platform_826646-2"))
    )
    (comp (ref "J21")
      (value "826646-2")
      (footprint "eagle-import:H2-2.54")
      (libsource (lib "eagle-import") (part "OSD3358-SM-RED Platform_826646-2"))
    )
    (comp (ref "J22")
      (value "826646-2")
      (footprint "eagle-import:H2-2.54")
      (libsource (lib "eagle-import") (part "OSD3358-SM-RED Platform_826646-2"))
    )
    (comp (ref "J23")
      (value "826646-2")
      (footprint "eagle-import:H2-2.54")
      (libsource (lib "eagle-import") (part "OSD3358-SM-RED Platform_826646-2"))
    )
    (comp (ref "J24")
      (value "6p-2.54")
      (footprint "eagle-import:H3-2.54")
      (fields (field (name "MPN") "P125-1106A1BS116A1"))
      (libsource (lib "eagle-import") (part "826646-3"))
    )
    (comp (ref "J31")
      (value "826646-2")
      (footprint "eagle-import:H2-2.54")
      (libsource (lib "eagle-import") (part "OSD3358-SM-RED Platform_826646-2"))
    )
    (comp (ref "J32")
      (value "826646-2")
      (footprint "eagle-import:H2-2.54")
      (libsource (lib "eagle-import") (part "OSD3358-SM-RED Platform_826646-2"))
    )
    (comp (ref "J33")
      (value "826646-2")
      (footprint "eagle-import:H2-2.54")
      (libsource (lib "eagle-import") (part "OSD3358-SM-RED Platform_826646-2"))
    )
    (comp (ref "J41")
      (value "826646-2")
      (footprint "eagle-import:H2-2.54")
      (libsource (lib "eagle-import") (part "OSD3358-SM-RED Platform_826646-2"))
    )
    (comp (ref "J42")
      (value "826646-2")
      (footprint "eagle-import:H2-2.54")
      (libsource (lib "eagle-import") (part "OSD3358-SM-RED Platform_826646-2"))
    )
    (comp (ref "J43")
      (value "826646-2")
      (footprint "eagle-import:H2-2.54")
      (libsource (lib "eagle-import") (part "OSD3358-SM-RED Platform_826646-2"))
    )
    (comp (ref "J51")
      (value "826646-2")
      (footprint "eagle-import:H2-2.54")
      (libsource (lib "eagle-import") (part "OSD3358-SM-RED Platform_826646-2"))
    )
    (comp (ref "J52")
      (value "826646-2")
      (footprint "eagle-import:H2-2.54")
      (libsource (lib "eagle-import") (part "OSD3358-SM-RED Platform_826646-2"))
    )
    (comp (ref "J53")
      (value "826646-2")
      (footprint "eagle-import:H2-2.54")
      (libsource (lib "eagle-import") (part "OSD3358-SM-RED Platform_826646-2"))
    )
    (comp (ref "J61")
      (value "826646-2")
      (footprint "eagle-import:H2-2.54")
      (libsource (lib "eagle-import") (part "OSD3358-SM-RED Platform_826646-2"))
    )
    (comp (ref "J62")
      (value "826646-2")
      (footprint "eagle-import:H2-2.54")
      (libsource (lib "eagle-import") (part "OSD3358-SM-RED Platform_826646-2"))
    )
    (comp (ref "J63")
      (value "826646-2")
      (footprint "eagle-import:H2-2.54")
      (libsource (lib "eagle-import") (part "OSD3358-SM-RED Platform_826646-2"))
    )
    (comp (ref "K1")
      (value "JS1-24V-F")
      (footprint "eagle-import:JS-M")
      (fields (field (name "MF") "FARNELL") (field (name "MPN") "JSM1-12V-5"))
      (libsource (lib "eagle-import") (part "JS-M1-12V-5"))
    )
    (comp (ref "K2")
      (value "JS1-24V-F")
      (footprint "eagle-import:JS-M")
      (fields (field (name "MF") "FARNELL") (field (name "MPN") "JSM1-12V-5"))
      (libsource (lib "eagle-import") (part "JS-M1-12V-5"))
    )
    (comp (ref "K3")
      (value "JS1-24V-F")
      (footprint "eagle-import:JS-M")
      (fields (field (name "MF") "FARNELL") (field (name "MPN") "JSM1-12V-5"))
      (libsource (lib "eagle-import") (part "JS-M1-12V-5"))
    )
    (comp (ref "K4")
      (value "JS1-24V-F")
      (footprint "eagle-import:JS-M")
      (fields (field (name "MF") "FARNELL") (field (name "MPN") "JSM1-12V-5"))
      (libsource (lib "eagle-import") (part "JS-M1-12V-5"))
    )
    (comp (ref "K5")
      (value "JS1-24V-F")
      (footprint "eagle-import:JS-M")
      (fields (field (name "MF") "FARNELL") (field (name "MPN") "JSM1-12V-5"))
      (libsource (lib "eagle-import") (part "JS-M1-12V-5"))
    )
    (comp (ref "L2")
      (value "MSS1260T-473ML")
      (footprint "eagle-import:MSS1260")
      (libsource (lib "eagle-import") (part "MSS1260"))
    )
    (comp (ref "MGT1")
      (value "MOUNTING_HOLE")
      (footprint "eagle-import:MOUNTING_HOLE")
      (libsource (lib "eagle-import") (part "MOUNTING_HOLE"))
    )
    (comp (ref "MGT2")
      (value "MOUNTING_HOLE")
      (footprint "eagle-import:MOUNTING_HOLE")
      (libsource (lib "eagle-import") (part "MOUNTING_HOLE"))
    )
    (comp (ref "MGT3")
      (value "MOUNTING_HOLE")
      (footprint "eagle-import:MOUNTING_HOLE")
      (libsource (lib "eagle-import") (part "MOUNTING_HOLE"))
    )
    (comp (ref "MGT4")
      (value "MOUNTING_HOLE")
      (footprint "eagle-import:MOUNTING_HOLE")
      (libsource (lib "eagle-import") (part "MOUNTING_HOLE"))
    )
    (comp (ref "Q1")
      (value "MMBT2907")
      (footprint "eagle-import:SOT23-BEC")
      (libsource (lib "eagle-import") (part "MMBT2907SMD"))
    )
    (comp (ref "R3")
      (value "0, 1%")
      (footprint "eagle-import:R0402")
      (libsource (lib "eagle-import") (part "OSD3358-SM-RED Platform_R-US_R0402"))
    )
    (comp (ref "R4")
      (value "0, 1%")
      (footprint "eagle-import:R0402")
      (libsource (lib "eagle-import") (part "OSD3358-SM-RED Platform_R-US_R0402"))
    )
    (comp (ref "R5")
      (value "0")
      (footprint "eagle-import:R0402")
      (libsource (lib "eagle-import") (part "R-US_R0402"))
    )
    (comp (ref "R6")
      (value "100K, DNI")
      (footprint "eagle-import:R0402")
      (libsource (lib "eagle-import") (part "R-US_R0402"))
    )
    (comp (ref "R8")
      (value "1K")
      (footprint "eagle-import:R0402")
      (libsource (lib "eagle-import") (part "R-US_R0402"))
    )
    (comp (ref "R10")
      (value "0, 1%")
      (footprint "eagle-import:R0805")
      (libsource (lib "eagle-import") (part "OSD3358-SM-RED Platform_R-US_R0805"))
    )
    (comp (ref "R11")
      (value "0")
      (footprint "eagle-import:R0402")
      (libsource (lib "eagle-import") (part "R-US_R0402"))
    )
    (comp (ref "R12")
      (value "1.5K, 1%")
      (footprint "eagle-import:R0402")
      (libsource (lib "eagle-import") (part "OSD3358-SM-RED Platform_R-US_R0402"))
    )
    (comp (ref "R13")
      (value "1.5K, 1%")
      (footprint "eagle-import:R0402")
      (libsource (lib "eagle-import") (part "OSD3358-SM-RED Platform_R-US_R0402"))
    )
    (comp (ref "R15")
      (value "40.2K")
      (footprint "eagle-import:R0402")
      (libsource (lib "eagle-import") (part "R-US_R0402"))
    )
    (comp (ref "R18")
      (value "4.75K, 1%")
      (footprint "eagle-import:R0402")
      (libsource (lib "eagle-import") (part "OSD3358-SM-RED Platform_R-US_R0402"))
    )
    (comp (ref "R20")
      (value "10K")
      (footprint "eagle-import:R0402")
      (libsource (lib "eagle-import") (part "R-US_R0402"))
    )
    (comp (ref "R21")
      (value "499")
      (footprint "eagle-import:R0402")
      (libsource (lib "eagle-import") (part "R-US_R0402"))
    )
    (comp (ref "R22")
      (value "4.75K, 1%")
      (footprint "eagle-import:R0402")
      (libsource (lib "eagle-import") (part "OSD3358-SM-RED Platform_R-US_R0402"))
    )
    (comp (ref "R25")
      (value "0, 1%")
      (footprint "eagle-import:R0402")
      (libsource (lib "eagle-import") (part "OSD3358-SM-RED Platform_R-US_R0402"))
    )
    (comp (ref "R26")
      (value "1.5K, 1%")
      (footprint "eagle-import:R0402")
      (libsource (lib "eagle-import") (part "OSD3358-SM-RED Platform_R-US_R0402"))
    )
    (comp (ref "R27")
      (value "100K, 1%")
      (footprint "eagle-import:R0402")
      (libsource (lib "eagle-import") (part "OSD3358-SM-RED Platform_R-US_R0402"))
    )
    (comp (ref "R28")
      (value "0, 1%")
      (footprint "eagle-import:R0402")
      (libsource (lib "eagle-import") (part "OSD3358-SM-RED Platform_R-US_R0402"))
    )
    (comp (ref "R29")
      (value "0, 1%")
      (footprint "eagle-import:R0402")
      (libsource (lib "eagle-import") (part "OSD3358-SM-RED Platform_R-US_R0402"))
    )
    (comp (ref "R30")
      (value "0, 1%")
      (footprint "eagle-import:R0402")
      (libsource (lib "eagle-import") (part "OSD3358-SM-RED Platform_R-US_R0402"))
    )
    (comp (ref "R31")
      (value "22, 1%")
      (footprint "eagle-import:R0402")
      (libsource (lib "eagle-import") (part "OSD3358-SM-RED Platform_R-US_R0402"))
    )
    (comp (ref "R33")
      (value "0, 1%")
      (footprint "eagle-import:R0402")
      (libsource (lib "eagle-import") (part "OSD3358-SM-RED Platform_R-US_R0402"))
    )
    (comp (ref "R34")
      (value ".1, 0805")
      (footprint "eagle-import:R0805")
      (libsource (lib "eagle-import") (part "OSD3358-SM-RED Platform_R-US_R0805"))
    )
    (comp (ref "R35")
      (value "1K")
      (footprint "eagle-import:RN0804")
      (libsource (lib "eagle-import") (part "RESISTOR.NETWORK-(4)"))
    )
    (comp (ref "R39")
      (value "4.75K, 1%")
      (footprint "eagle-import:R0402")
      (libsource (lib "eagle-import") (part "OSD3358-SM-RED Platform_R-US_R0402"))
    )
    (comp (ref "R40")
      (value "4.75K, 1%")
      (footprint "eagle-import:R0402")
      (libsource (lib "eagle-import") (part "OSD3358-SM-RED Platform_R-US_R0402"))
    )
    (comp (ref "R41")
      (value "4.75K, 1%")
      (footprint "eagle-import:R0402")
      (libsource (lib "eagle-import") (part "OSD3358-SM-RED Platform_R-US_R0402"))
    )
    (comp (ref "R53")
      (value "100K, 1%")
      (footprint "eagle-import:R0402")
      (libsource (lib "eagle-import") (part "OSD3358-SM-RED Platform_R-US_R0402"))
    )
    (comp (ref "R54")
      (value "100K, 1%, DNI")
      (footprint "eagle-import:R0402")
      (libsource (lib "eagle-import") (part "OSD3358-SM-RED Platform_R-US_R0402"))
    )
    (comp (ref "R55")
      (value "100K, 1%")
      (footprint "eagle-import:R0402")
      (libsource (lib "eagle-import") (part "OSD3358-SM-RED Platform_R-US_R0402"))
    )
    (comp (ref "R56")
      (value "100K, 1%")
      (footprint "eagle-import:R0402")
      (libsource (lib "eagle-import") (part "OSD3358-SM-RED Platform_R-US_R0402"))
    )
    (comp (ref "R57")
      (value "100K, 1%")
      (footprint "eagle-import:R0402")
      (libsource (lib "eagle-import") (part "OSD3358-SM-RED Platform_R-US_R0402"))
    )
    (comp (ref "R58")
      (value "100K, 1%")
      (footprint "eagle-import:R0402")
      (libsource (lib "eagle-import") (part "OSD3358-SM-RED Platform_R-US_R0402"))
    )
    (comp (ref "R59")
      (value "100K, 1%")
      (footprint "eagle-import:R0402")
      (libsource (lib "eagle-import") (part "OSD3358-SM-RED Platform_R-US_R0402"))
    )
    (comp (ref "R60")
      (value "100K, 1%")
      (footprint "eagle-import:R0402")
      (libsource (lib "eagle-import") (part "OSD3358-SM-RED Platform_R-US_R0402"))
    )
    (comp (ref "R61")
      (value "100K, 1%")
      (footprint "eagle-import:R0402")
      (libsource (lib "eagle-import") (part "OSD3358-SM-RED Platform_R-US_R0402"))
    )
    (comp (ref "R62")
      (value "100K, 1%")
      (footprint "eagle-import:R0402")
      (libsource (lib "eagle-import") (part "OSD3358-SM-RED Platform_R-US_R0402"))
    )
    (comp (ref "R63")
      (value "100K, 1%")
      (footprint "eagle-import:R0402")
      (libsource (lib "eagle-import") (part "OSD3358-SM-RED Platform_R-US_R0402"))
    )
    (comp (ref "R64")
      (value "100K, 1%, DNI")
      (footprint "eagle-import:R0402")
      (libsource (lib "eagle-import") (part "OSD3358-SM-RED Platform_R-US_R0402"))
    )
    (comp (ref "R65")
      (value "100K, 1%, DNI")
      (footprint "eagle-import:R0402")
      (libsource (lib "eagle-import") (part "OSD3358-SM-RED Platform_R-US_R0402"))
    )
    (comp (ref "R66")
      (value "100K, 1%, DNI")
      (footprint "eagle-import:R0402")
      (libsource (lib "eagle-import") (part "OSD3358-SM-RED Platform_R-US_R0402"))
    )
    (comp (ref "R67")
      (value "100K, 1%")
      (footprint "eagle-import:R0402")
      (libsource (lib "eagle-import") (part "OSD3358-SM-RED Platform_R-US_R0402"))
    )
    (comp (ref "R68")
      (value "100K, 1%")
      (footprint "eagle-import:R0402")
      (libsource (lib "eagle-import") (part "OSD3358-SM-RED Platform_R-US_R0402"))
    )
    (comp (ref "R69")
      (value "100, 1%")
      (footprint "eagle-import:R0402")
      (libsource (lib "eagle-import") (part "OSD3358-SM-RED Platform_R-US_R0402"))
    )
    (comp (ref "R70")
      (value "100K, 1%, DNI")
      (footprint "eagle-import:R0402")
      (libsource (lib "eagle-import") (part "OSD3358-SM-RED Platform_R-US_R0402"))
    )
    (comp (ref "R71")
      (value "100K, 1%")
      (footprint "eagle-import:R0402")
      (libsource (lib "eagle-import") (part "OSD3358-SM-RED Platform_R-US_R0402"))
    )
    (comp (ref "R72")
      (value "100K, 1%, DNI")
      (footprint "eagle-import:R0402")
      (libsource (lib "eagle-import") (part "OSD3358-SM-RED Platform_R-US_R0402"))
    )
    (comp (ref "R73")
      (value "100K, 1%, DNI")
      (footprint "eagle-import:R0402")
      (libsource (lib "eagle-import") (part "OSD3358-SM-RED Platform_R-US_R0402"))
    )
    (comp (ref "R74")
      (value "100K, 1%, DNI")
      (footprint "eagle-import:R0402")
      (libsource (lib "eagle-import") (part "OSD3358-SM-RED Platform_R-US_R0402"))
    )
    (comp (ref "R75")
      (value "100K, 1%, DNI")
      (footprint "eagle-import:R0402")
      (libsource (lib "eagle-import") (part "OSD3358-SM-RED Platform_R-US_R0402"))
    )
    (comp (ref "R76")
      (value "100K, 1%, DNI")
      (footprint "eagle-import:R0402")
      (libsource (lib "eagle-import") (part "OSD3358-SM-RED Platform_R-US_R0402"))
    )
    (comp (ref "R77")
      (value "100K, 1%, DNI")
      (footprint "eagle-import:R0402")
      (libsource (lib "eagle-import") (part "OSD3358-SM-RED Platform_R-US_R0402"))
    )
    (comp (ref "R78")
      (value "100K, 1%, DNI")
      (footprint "eagle-import:R0402")
      (libsource (lib "eagle-import") (part "OSD3358-SM-RED Platform_R-US_R0402"))
    )
    (comp (ref "R79")
      (value "100K, 1%, DNI")
      (footprint "eagle-import:R0402")
      (libsource (lib "eagle-import") (part "OSD3358-SM-RED Platform_R-US_R0402"))
    )
    (comp (ref "R80")
      (value "100K, 1%, DNI")
      (footprint "eagle-import:R0402")
      (libsource (lib "eagle-import") (part "OSD3358-SM-RED Platform_R-US_R0402"))
    )
    (comp (ref "R81")
      (value "100K, 1%")
      (footprint "eagle-import:R0402")
      (libsource (lib "eagle-import") (part "OSD3358-SM-RED Platform_R-US_R0402"))
    )
    (comp (ref "R82")
      (value "100K, 1%")
      (footprint "eagle-import:R0402")
      (libsource (lib "eagle-import") (part "OSD3358-SM-RED Platform_R-US_R0402"))
    )
    (comp (ref "R83")
      (value "100K, 1%")
      (footprint "eagle-import:R0402")
      (libsource (lib "eagle-import") (part "OSD3358-SM-RED Platform_R-US_R0402"))
    )
    (comp (ref "R84")
      (value "100K, 1%, DNI")
      (footprint "eagle-import:R0402")
      (libsource (lib "eagle-import") (part "OSD3358-SM-RED Platform_R-US_R0402"))
    )
    (comp (ref "R85")
      (value "100K, 1%, DNI")
      (footprint "eagle-import:R0402")
      (libsource (lib "eagle-import") (part "OSD3358-SM-RED Platform_R-US_R0402"))
    )
    (comp (ref "R86")
      (value "10K, 1%")
      (footprint "eagle-import:R0402")
      (libsource (lib "eagle-import") (part "OSD3358-SM-RED Platform_R-US_R0402"))
    )
    (comp (ref "R87")
      (value "10K, 1%")
      (footprint "eagle-import:R0402")
      (libsource (lib "eagle-import") (part "OSD3358-SM-RED Platform_R-US_R0402"))
    )
    (comp (ref "R88")
      (value "10K, 1%")
      (footprint "eagle-import:R0402")
      (libsource (lib "eagle-import") (part "OSD3358-SM-RED Platform_R-US_R0402"))
    )
    (comp (ref "R89")
      (value "10K, 1%")
      (footprint "eagle-import:R0402")
      (libsource (lib "eagle-import") (part "OSD3358-SM-RED Platform_R-US_R0402"))
    )
    (comp (ref "R90")
      (value "10K, 1%")
      (footprint "eagle-import:R0402")
      (libsource (lib "eagle-import") (part "OSD3358-SM-RED Platform_R-US_R0402"))
    )
    (comp (ref "R91")
      (value "10K, 1%")
      (footprint "eagle-import:R0402")
      (libsource (lib "eagle-import") (part "OSD3358-SM-RED Platform_R-US_R0402"))
    )
    (comp (ref "R92")
      (value "10K, 1%")
      (footprint "eagle-import:R0402")
      (libsource (lib "eagle-import") (part "OSD3358-SM-RED Platform_R-US_R0402"))
    )
    (comp (ref "R163")
      (value "100K, DNI")
      (footprint "eagle-import:R0402")
      (libsource (lib "eagle-import") (part "OSD3358-SM-RED Platform_R-US_R0402"))
    )
    (comp (ref "R164")
      (value "1.5K, 1%")
      (footprint "eagle-import:R0402")
      (libsource (lib "eagle-import") (part "OSD3358-SM-RED Platform_R-US_R0402"))
    )
    (comp (ref "R168")
      (value "10K")
      (footprint "eagle-import:R0402")
      (libsource (lib "eagle-import") (part "OSD3358-SM-RED Platform_R-US_R0402"))
    )
    (comp (ref "R169")
      (value "1.5K, 1%")
      (footprint "eagle-import:R0402")
      (libsource (lib "eagle-import") (part "OSD3358-SM-RED Platform_R-US_R0402"))
    )
    (comp (ref "R170")
      (value "1.5K, 1%")
      (footprint "eagle-import:R0402")
      (libsource (lib "eagle-import") (part "OSD3358-SM-RED Platform_R-US_R0402"))
    )
    (comp (ref "R171")
      (value "10K")
      (footprint "eagle-import:R0402")
      (libsource (lib "eagle-import") (part "OSD3358-SM-RED Platform_R-US_R0402"))
    )
    (comp (ref "R172")
      (value "10K")
      (footprint "eagle-import:R0402")
      (libsource (lib "eagle-import") (part "OSD3358-SM-RED Platform_R-US_R0402"))
    )
    (comp (ref "R173")
      (value "10K")
      (footprint "eagle-import:R0402")
      (libsource (lib "eagle-import") (part "OSD3358-SM-RED Platform_R-US_R0402"))
    )
    (comp (ref "R174")
      (value "10K")
      (footprint "eagle-import:R0402")
      (libsource (lib "eagle-import") (part "OSD3358-SM-RED Platform_R-US_R0402"))
    )
    (comp (ref "R175")
      (value "10K")
      (footprint "eagle-import:R0402")
      (libsource (lib "eagle-import") (part "OSD3358-SM-RED Platform_R-US_R0402"))
    )
    (comp (ref "R181")
      (value "B72520T0300K062")
      (footprint "eagle-import:CT_CN1206")
      (libsource (lib "eagle-import") (part "VARISTORCN1206"))
    )
    (comp (ref "R182")
      (value "B72520T0300K062")
      (footprint "eagle-import:CT_CN1206")
      (libsource (lib "eagle-import") (part "VARISTORCN1206"))
    )
    (comp (ref "R183")
      (value "B72520T0300K062")
      (footprint "eagle-import:CT_CN1206")
      (libsource (lib "eagle-import") (part "VARISTORCN1206"))
    )
    (comp (ref "R184")
      (value "B72520T0300K062")
      (footprint "eagle-import:CT_CN1206")
      (libsource (lib "eagle-import") (part "VARISTORCN1206"))
    )
    (comp (ref "R185")
      (value "B72520T0300K062")
      (footprint "eagle-import:CT_CN1206")
      (libsource (lib "eagle-import") (part "VARISTORCN1206"))
    )
    (comp (ref "R186")
      (value "B72520T0300K062")
      (footprint "eagle-import:CT_CN1206")
      (libsource (lib "eagle-import") (part "VARISTORCN1206"))
    )
    (comp (ref "R211")
      (value "80, 0.1%")
      (footprint "eagle-import:0309_12")
      (libsource (lib "eagle-import") (part "resistor_348_R-US_0309/12"))
    )
    (comp (ref "R212")
      (value "10K, 1%")
      (footprint "eagle-import:R0805")
      (libsource (lib "eagle-import") (part "OSD3358-SM-RED Platform_R-US_R0805"))
    )
    (comp (ref "R213")
      (value "2K, 1%")
      (footprint "eagle-import:R0805")
      (libsource (lib "eagle-import") (part "OSD3358-SM-RED Platform_R-US_R0805"))
    )
    (comp (ref "R214")
      (value "10K, 1%")
      (footprint "eagle-import:R0805")
      (libsource (lib "eagle-import") (part "OSD3358-SM-RED Platform_R-US_R0805"))
    )
    (comp (ref "R221")
      (value "80, 0.1%")
      (footprint "eagle-import:0309_12")
      (libsource (lib "eagle-import") (part "resistor_348_R-US_0309/12"))
    )
    (comp (ref "R222")
      (value "10K, 1%")
      (footprint "eagle-import:R0805")
      (libsource (lib "eagle-import") (part "OSD3358-SM-RED Platform_R-US_R0805"))
    )
    (comp (ref "R223")
      (value "2K, 1%")
      (footprint "eagle-import:R0805")
      (libsource (lib "eagle-import") (part "OSD3358-SM-RED Platform_R-US_R0805"))
    )
    (comp (ref "R224")
      (value "10K, 1%")
      (footprint "eagle-import:R0805")
      (libsource (lib "eagle-import") (part "OSD3358-SM-RED Platform_R-US_R0805"))
    )
    (comp (ref "R231")
      (value "80, 0.1%")
      (footprint "eagle-import:0309_12")
      (libsource (lib "eagle-import") (part "resistor_348_R-US_0309/12"))
    )
    (comp (ref "R232")
      (value "10K, 1%")
      (footprint "eagle-import:R0805")
      (libsource (lib "eagle-import") (part "OSD3358-SM-RED Platform_R-US_R0805"))
    )
    (comp (ref "R233")
      (value "2K, 1%")
      (footprint "eagle-import:R0805")
      (libsource (lib "eagle-import") (part "OSD3358-SM-RED Platform_R-US_R0805"))
    )
    (comp (ref "R234")
      (value "10K, 1%")
      (footprint "eagle-import:R0805")
      (libsource (lib "eagle-import") (part "OSD3358-SM-RED Platform_R-US_R0805"))
    )
    (comp (ref "R241")
      (value "80, 0.1%")
      (footprint "eagle-import:0309_12")
      (libsource (lib "eagle-import") (part "resistor_348_R-US_0309/12"))
    )
    (comp (ref "R242")
      (value "10K, 1%")
      (footprint "eagle-import:R0805")
      (libsource (lib "eagle-import") (part "OSD3358-SM-RED Platform_R-US_R0805"))
    )
    (comp (ref "R243")
      (value "2K, 1%")
      (footprint "eagle-import:R0805")
      (libsource (lib "eagle-import") (part "OSD3358-SM-RED Platform_R-US_R0805"))
    )
    (comp (ref "R244")
      (value "10K, 1%")
      (footprint "eagle-import:R0805")
      (libsource (lib "eagle-import") (part "OSD3358-SM-RED Platform_R-US_R0805"))
    )
    (comp (ref "R251")
      (value "80, 0.1%")
      (footprint "eagle-import:0309_12")
      (libsource (lib "eagle-import") (part "resistor_348_R-US_0309/12"))
    )
    (comp (ref "R252")
      (value "10K, 1%")
      (footprint "eagle-import:R0805")
      (libsource (lib "eagle-import") (part "OSD3358-SM-RED Platform_R-US_R0805"))
    )
    (comp (ref "R253")
      (value "2K, 1%")
      (footprint "eagle-import:R0805")
      (libsource (lib "eagle-import") (part "OSD3358-SM-RED Platform_R-US_R0805"))
    )
    (comp (ref "R254")
      (value "10K, 1%")
      (footprint "eagle-import:R0805")
      (libsource (lib "eagle-import") (part "OSD3358-SM-RED Platform_R-US_R0805"))
    )
    (comp (ref "R261")
      (value "80, 0.1%")
      (footprint "eagle-import:0309_12")
      (libsource (lib "eagle-import") (part "resistor_348_R-US_0309/12"))
    )
    (comp (ref "R262")
      (value "10K, 1%")
      (footprint "eagle-import:R0805")
      (libsource (lib "eagle-import") (part "OSD3358-SM-RED Platform_R-US_R0805"))
    )
    (comp (ref "R263")
      (value "2K, 1%")
      (footprint "eagle-import:R0805")
      (libsource (lib "eagle-import") (part "OSD3358-SM-RED Platform_R-US_R0805"))
    )
    (comp (ref "R264")
      (value "10K, 1%")
      (footprint "eagle-import:R0805")
      (libsource (lib "eagle-import") (part "OSD3358-SM-RED Platform_R-US_R0805"))
    )
    (comp (ref "R281")
      (value "10K")
      (footprint "eagle-import:RN0804")
      (libsource (lib "eagle-import") (part "RESISTOR.NETWORK-(4)"))
    )
    (comp (ref "R282")
      (value "10K")
      (footprint "eagle-import:RN0804")
      (libsource (lib "eagle-import") (part "RESISTOR.NETWORK-(4)"))
    )
    (comp (ref "R291")
      (value "10K")
      (footprint "eagle-import:RN0804")
      (libsource (lib "eagle-import") (part "RESISTOR.NETWORK-(4)"))
    )
    (comp (ref "R301")
      (value "1K")
      (footprint "eagle-import:R0402")
      (libsource (lib "eagle-import") (part "OSD3358-SM-RED Platform_R-US_R0402"))
    )
    (comp (ref "R302")
      (value "1K")
      (footprint "eagle-import:R0402")
      (libsource (lib "eagle-import") (part "OSD3358-SM-RED Platform_R-US_R0402"))
    )
    (comp (ref "R303")
      (value "1K, DNI")
      (footprint "eagle-import:R0402")
      (libsource (lib "eagle-import") (part "OSD3358-SM-RED Platform_R-US_R0402"))
    )
    (comp (ref "R304")
      (value "1K, DNI")
      (footprint "eagle-import:R0402")
      (libsource (lib "eagle-import") (part "OSD3358-SM-RED Platform_R-US_R0402"))
    )
    (comp (ref "R305")
      (value "150, 1%")
      (footprint "eagle-import:R0805")
      (libsource (lib "eagle-import") (part "OSD3358-SM-RED Platform_R-US_R0805"))
    )
    (comp (ref "R401")
      (value "1K")
      (footprint "eagle-import:R0402")
      (libsource (lib "eagle-import") (part "OSD3358-SM-RED Platform_R-US_R0402"))
    )
    (comp (ref "R402")
      (value "1K")
      (footprint "eagle-import:R0402")
      (libsource (lib "eagle-import") (part "OSD3358-SM-RED Platform_R-US_R0402"))
    )
    (comp (ref "R801")
      (value "1K")
      (footprint "eagle-import:R0402")
      (libsource (lib "eagle-import") (part "OSD3358-SM-RED Platform_R-US_R0402"))
    )
    (comp (ref "R802")
      (value "1K")
      (footprint "eagle-import:R0402")
      (libsource (lib "eagle-import") (part "OSD3358-SM-RED Platform_R-US_R0402"))
    )
    (comp (ref "RTC1")
      (value "DS3231MZ+")
      (footprint "eagle-import:SO08")
      (libsource (lib "eagle-import") (part "DS3231M"))
    )
    (comp (ref "S1")
      (value "KMR231GLFS")
      (footprint "eagle-import:SW4SMD_63X161LS")
      (libsource (lib "eagle-import") (part "KMR231GLFS"))
    )
    (comp (ref "S2")
      (value "KMR231GLFS")
      (footprint "eagle-import:SW4SMD_63X161LS")
      (libsource (lib "eagle-import") (part "OSD3358-SM-RED Platform_KMR231GLFS"))
    )
    (comp (ref "S11")
      (value "P101")
      (footprint "eagle-import:P101")
      (libsource (lib "eagle-import") (part "P101"))
    )
    (comp (ref "S12")
      (value "P101")
      (footprint "eagle-import:P101")
      (libsource (lib "eagle-import") (part "P101"))
    )
    (comp (ref "S13")
      (value "DS04")
      (footprint "eagle-import:DS-04")
      (libsource (lib "eagle-import") (part "DS04"))
    )
    (comp (ref "T4")
      (value "DA2304-AL")
      (footprint "eagle-import:DA230X-AL")
      (libsource (lib "eagle-import") (part "DA2304-AL"))
    )
    (comp (ref "TP1")
      (value "TPB0,65")
      (footprint "eagle-import:TP_B0,65")
      (libsource (lib "eagle-import") (part "OSD3358-SM-RED Platform_TPB0,65"))
    )
    (comp (ref "TP2")
      (value "TPB0,65")
      (footprint "eagle-import:TP_B0,65")
      (libsource (lib "eagle-import") (part "OSD3358-SM-RED Platform_TPB0,65"))
    )
    (comp (ref "TP3")
      (value "TPB0,65")
      (footprint "eagle-import:TP_B0,65")
      (libsource (lib "eagle-import") (part "OSD3358-SM-RED Platform_TPB0,65"))
    )
    (comp (ref "TP4")
      (value "TPB0,65")
      (footprint "eagle-import:TP_B0,65")
      (libsource (lib "eagle-import") (part "OSD3358-SM-RED Platform_TPB0,65"))
    )
    (comp (ref "TP5")
      (value "TESTPAD/W_HOLE_1X1")
      (footprint "eagle-import:TESTPAD_W_HOLE_1X1")
      (libsource (lib "eagle-import") (part "TESTPAD/W_HOLE_1X1"))
    )
    (comp (ref "TP6")
      (value "TESTPAD/W_HOLE_1X1")
      (footprint "eagle-import:TESTPAD_W_HOLE_1X1")
      (libsource (lib "eagle-import") (part "TESTPAD/W_HOLE_1X1"))
    )
    (comp (ref "TP7")
      (value "TESTPAD/W_HOLE_1X1")
      (footprint "eagle-import:TESTPAD_W_HOLE_1X1")
      (libsource (lib "eagle-import") (part "TESTPAD/W_HOLE_1X1"))
    )
    (comp (ref "TP8")
      (value "TESTPAD/W_HOLE_1X1")
      (footprint "eagle-import:TESTPAD_W_HOLE_1X1")
      (libsource (lib "eagle-import") (part "TESTPAD/W_HOLE_1X1"))
    )
    (comp (ref "TP9")
      (value "TESTPAD/W_HOLE_1X1")
      (footprint "eagle-import:TESTPAD_W_HOLE_1X1")
      (libsource (lib "eagle-import") (part "TESTPAD/W_HOLE_1X1"))
    )
    (comp (ref "TP10")
      (value "TESTPAD/W_HOLE_1X1")
      (footprint "eagle-import:TESTPAD_W_HOLE_1X1")
      (libsource (lib "eagle-import") (part "TESTPAD/W_HOLE_1X1"))
    )
    (comp (ref "TP11")
      (value "TPB0,65")
      (footprint "eagle-import:TP_B0,65")
      (libsource (lib "eagle-import") (part "OSD3358-SM-RED Platform_TPB0,65"))
    )
    (comp (ref "TP12")
      (value "TPB0,65")
      (footprint "eagle-import:TP_B0,65")
      (libsource (lib "eagle-import") (part "OSD3358-SM-RED Platform_TPB0,65"))
    )
    (comp (ref "TP13")
      (value "TPB0,65")
      (footprint "eagle-import:TP_B0,65")
      (libsource (lib "eagle-import") (part "OSD3358-SM-RED Platform_TPB0,65"))
    )
    (comp (ref "TP14")
      (value "TPB0,65")
      (footprint "eagle-import:TP_B0,65")
      (libsource (lib "eagle-import") (part "OSD3358-SM-RED Platform_TPB0,65"))
    )
    (comp (ref "TP15")
      (value "TPB0,65")
      (footprint "eagle-import:TP_B0,65")
      (libsource (lib "eagle-import") (part "OSD3358-SM-RED Platform_TPB0,65"))
    )
    (comp (ref "TP16")
      (value "TPB0,65")
      (footprint "eagle-import:TP_B0,65")
      (libsource (lib "eagle-import") (part "OSD3358-SM-RED Platform_TPB0,65"))
    )
    (comp (ref "TP17")
      (value "TESTPAD/W_HOLE_1X1")
      (footprint "eagle-import:TESTPAD_W_HOLE_1X1")
      (libsource (lib "eagle-import") (part "TESTPAD/W_HOLE_1X1"))
    )
    (comp (ref "TP18")
      (value "TESTPAD/W_HOLE_1X1")
      (footprint "eagle-import:TESTPAD_W_HOLE_1X1")
      (libsource (lib "eagle-import") (part "TESTPAD/W_HOLE_1X1"))
    )
    (comp (ref "TP19")
      (value "TESTPAD/W_HOLE_1X1")
      (footprint "eagle-import:TESTPAD_W_HOLE_1X1")
      (libsource (lib "eagle-import") (part "TESTPAD/W_HOLE_1X1"))
    )
    (comp (ref "TP20")
      (value "TESTPAD/W_HOLE_1X1")
      (footprint "eagle-import:TESTPAD_W_HOLE_1X1")
      (libsource (lib "eagle-import") (part "TESTPAD/W_HOLE_1X1"))
    )
    (comp (ref "TP21")
      (value "TPB0,65")
      (footprint "eagle-import:TP_B0,65")
      (libsource (lib "eagle-import") (part "OSD3358-SM-RED Platform_TPB0,65"))
    )
    (comp (ref "TP22")
      (value "TPB0,65")
      (footprint "eagle-import:TP_B0,65")
      (libsource (lib "eagle-import") (part "OSD3358-SM-RED Platform_TPB0,65"))
    )
    (comp (ref "TP23")
      (value "TPB0,65")
      (footprint "eagle-import:TP_B0,65")
      (libsource (lib "eagle-import") (part "OSD3358-SM-RED Platform_TPB0,65"))
    )
    (comp (ref "TP24")
      (value "TPB0,65")
      (footprint "eagle-import:TP_B0,65")
      (libsource (lib "eagle-import") (part "OSD3358-SM-RED Platform_TPB0,65"))
    )
    (comp (ref "TP26")
      (value "TPB0,65")
      (footprint "eagle-import:TP_B0,65")
      (libsource (lib "eagle-import") (part "TPB0,65"))
    )
    (comp (ref "TP31")
      (value "TPB0,65")
      (footprint "eagle-import:TP_B0,65")
      (libsource (lib "eagle-import") (part "TPB0,65"))
    )
    (comp (ref "TP32")
      (value "TPB0,65")
      (footprint "eagle-import:TP_B0,65")
      (libsource (lib "eagle-import") (part "OSD3358-SM-RED Platform_TPB0,65"))
    )
    (comp (ref "TP33")
      (value "TPB0,65")
      (footprint "eagle-import:TP_B0,65")
      (libsource (lib "eagle-import") (part "OSD3358-SM-RED Platform_TPB0,65"))
    )
    (comp (ref "U1")
      (value "OSD3358-512M-ICB")
      (footprint "eagle-import:OSD335X-BGA-400")
      (libsource (lib "eagle-import") (part "OSD3358-512M-ICB"))
    )
    (comp (ref "U2")
      (value "TPD4S012_DRY_6_P1_M")
      (footprint "eagle-import:DRY6")
      (fields
        (field (name "GENERIC_PART_NUMBER") "TPD4S012")
        (field (name "MANUFACTURER") "Texas Instruments")
        (field (name "MANUFACTURER_PART_NUMBER") "tpd4s012_dry_6")
      )
      (libsource (lib "eagle-import") (part "TPD4S012_DRY_6_P1_M"))
    )
    (comp (ref "U4")
      (value "APX811-31UGSOT")
      (footprint "eagle-import:SOT143-R")
      (libsource (lib "eagle-import") (part "APX811-31UGSOT"))
    )
    (comp (ref "U5")
      (value "TLVH431")
      (footprint "eagle-import:SOT23-3")
      (libsource (lib "eagle-import") (part "TLVH431"))
    )
    (comp (ref "U6")
      (value "SN74LVC2G241_DCU_8")
      (footprint "eagle-import:DCU8")
      (fields
        (field (name "GENERIC_PART_NUMBER") "SN74LVC2G241")
        (field (name "MANUFACTURER") "Texas Instruments")
        (field (name "MANUFACTURER_PART_NUMBER") "sn74lvc2g241_dcu_8")
      )
      (libsource (lib "eagle-import") (part "SN74LVC2G241_DCU_8"))
    )
    (comp (ref "U16")
      (value "AT97SC3205T-G3M4400B")
      (footprint "eagle-import:QFN32-0.4-4X4MM")
      (libsource (lib "eagle-import") (part "AT97SC3205T-G3M4400B"))
    )
    (comp (ref "U27")
      (value "LAN8710")
      (footprint "eagle-import:LAN8710A-QFN32")
      (libsource (lib "eagle-import") (part "LAN8710"))
    )
    (comp (ref "U28")
      (value "TCAN1051HV")
      (footprint "eagle-import:BEAGLEBONE_BLUE_D8")
      (fields
        (field (name "MANUFACTURER") "Texas Instruments")
        (field (name "MANUFACTURER_PART_NUMBER") "TCAN1051HVD")
      )
      (libsource (lib "eagle-import") (part "TCAN1051HV"))
    )
    (comp (ref "U29")
      (value "MAX3483EESA+T")
      (footprint "eagle-import:21-0041B_8")
      (libsource (lib "eagle-import") (part "MAX3483EESA+T"))
    )
    (comp (ref "U40")
      (value "ISO3086TDW")
      (footprint "eagle-import:DW16")
      (libsource (lib "eagle-import") (part "ISO3086TDW"))
    )
    (comp (ref "VREG1")
      (value "LM2596S-5.0")
      (footprint "eagle-import:TO263-5")
      (libsource (lib "eagle-import") (part "LM2596S"))
    )
    (comp (ref "VREG2")
      (value "L7824CV")
      (footprint "eagle-import:78XXL")
      (libsource (lib "eagle-import") (part "78XXL"))
    )
    (comp (ref "VREG4")
      (value "TPS76350")
      (footprint "eagle-import:DBV5")
      (fields (field (name "MANUFACTURER_PART_NUMBER") "LP2985A33DBVR"))
      (libsource (lib "eagle-import") (part "LP2985A-33DBVR"))
    )
    (comp (ref "X1")
      (value "10118194-0001LF")
      (footprint "eagle-import:10118194-0001LF(MICRO-USB-B-AMPHENOL-FCI)")
      (libsource (lib "eagle-import") (part "10118194-0001LF"))
    )
    (comp (ref "X2")
      (value "J0011D01BNL")
      (footprint "eagle-import:J0011D01BNL")
      (libsource (lib "eagle-import") (part "J0011D01BNL"))
    )
    (comp (ref "X3")
      (value "MC4")
      (footprint "eagle-import:MC4")
      (libsource (lib "eagle-import") (part "MC4"))
    )
    (comp (ref "X4")
      (value "CTI-JTAG")
      (footprint "eagle-import:CTI-JTAG")
      (libsource (lib "eagle-import") (part "CTI-JTAG"))
    )
    (comp (ref "X5")
      (value "DM3CS-SF")
      (footprint "eagle-import:DM3CS-SF")
      (fields (field (name "MOUSER_PART_NUMBER") "798-DM3CSSF"))
      (libsource (lib "eagle-import") (part "DM3CS-SF"))
    )
    (comp (ref "X6")
      (value "6p-2.54")
      (footprint "eagle-import:H6-2.54")
      (fields (field (name "MPN") "P125-1106A1BS116A1"))
      (libsource (lib "eagle-import") (part "826646-6"))
    )
    (comp (ref "X7")
      (value "TH-2X10")
      (footprint "eagle-import:H2X10-2.54")
      (libsource (lib "eagle-import") (part "TH-2X10"))
    )
    (comp (ref "X8")
      (value "MC4")
      (footprint "eagle-import:MC4")
      (libsource (lib "eagle-import") (part "MC4"))
    )
    (comp (ref "X10")
      (value "MC4")
      (footprint "eagle-import:MC4")
      (libsource (lib "eagle-import") (part "MC4"))
    )
    (comp (ref "X11")
      (value "MC4")
      (footprint "eagle-import:MC4")
      (libsource (lib "eagle-import") (part "MC4"))
    )
    (comp (ref "X12")
      (value "MC4")
      (footprint "eagle-import:MC4")
      (libsource (lib "eagle-import") (part "MC4"))
    )
    (comp (ref "X21")
      (value "MC10")
      (footprint "eagle-import:MC10")
      (libsource (lib "eagle-import") (part "MC10"))
    )
    (comp (ref "X24")
      (value "MSTBA2")
      (footprint "eagle-import:MSTBA2")
      (fields (field (name "MF") "FARNELL") (field (name "MPN") "1757242"))
      (libsource (lib "eagle-import") (part "MSTBA2"))
    )
    (comp (ref "X41")
      (value "MSTBA3")
      (footprint "eagle-import:MSTBA3")
      (fields (field (name "MF") "FARNELL") (field (name "MPN") "1757255"))
      (libsource (lib "eagle-import") (part "MSTBA3"))
    )
    (comp (ref "Y7")
      (value "7A-25.000MAAE-T")
      (footprint "eagle-import:CRYSTAL-TXC-7A")
      (libsource (lib "eagle-import") (part "7A-25.000MAAE-T"))
    )
  )
  (nets
    (net (code "1") (name "/1P8V_REF_1") (class "Default")
      (node (ref "IC10") (pin "8") (pinfunction "V+_8") (pintype "power_in"))
      (node (ref "IC11") (pin "8") (pinfunction "V+_8") (pintype "power_in"))
      (node (ref "IC14") (pin "1") (pinfunction "OUT_1") (pintype "output"))
      (node (ref "IC14") (pin "2") (pinfunction "-IN_2") (pintype "input"))
      (node (ref "R212") (pin "2") (pinfunction "2_2") (pintype "passive"))
      (node (ref "R222") (pin "2") (pinfunction "2_2") (pintype "passive"))
      (node (ref "R232") (pin "2") (pinfunction "2_2") (pintype "passive"))
      (node (ref "R242") (pin "2") (pinfunction "2_2") (pintype "passive"))
    )
    (net (code "2") (name "/1P8V_REF_2") (class "Default")
      (node (ref "IC12") (pin "8") (pinfunction "V+_8") (pintype "power_in"))
      (node (ref "IC14") (pin "6") (pinfunction "-IN_6") (pintype "input"))
      (node (ref "IC14") (pin "7") (pinfunction "OUT_7") (pintype "output"))
      (node (ref "R252") (pin "2") (pinfunction "2_2") (pintype "passive"))
      (node (ref "R262") (pin "2") (pinfunction "2_2") (pintype "passive"))
    )
    (net (code "3") (name "/5V_OUT") (class "Default")
      (node (ref "D18") (pin "C") (pinfunction "C_C") (pintype "passive"))
      (node (ref "L2") (pin "1") (pinfunction "1_1") (pintype "passive"))
      (node (ref "VREG1") (pin "2") (pinfunction "OUT_2") (pintype "output"))
    )
    (net (code "4") (name "/485_A") (class "Default")
      (node (ref "D305") (pin "1") (pinfunction "1_1") (pintype "passive"))
      (node (ref "R304") (pin "2") (pinfunction "2_2") (pintype "passive"))
      (node (ref "R305") (pin "2") (pinfunction "2_2") (pintype "passive"))
      (node (ref "U29") (pin "6") (pinfunction "A_6") (pintype "bidirectional"))
      (node (ref "X3") (pin "2") (pinfunction "SK_2") (pintype "passive"))
    )
    (net (code "5") (name "/485_B") (class "Default")
      (node (ref "D305") (pin "2") (pinfunction "2_2") (pintype "passive"))
      (node (ref "R303") (pin "1") (pinfunction "1_1") (pintype "passive"))
      (node (ref "R305") (pin "1") (pinfunction "1_1") (pintype "passive"))
      (node (ref "U29") (pin "7") (pinfunction "B_7") (pintype "bidirectional"))
      (node (ref "X3") (pin "3") (pinfunction "SK_3") (pintype "passive"))
    )
    (net (code "6") (name "/AIN0") (class "Default")
      (node (ref "U1") (pin "Y10") (pinfunction "AIN0_Y10") (pintype "bidirectional"))
    )
    (net (code "7") (name "/AIN1") (class "Default")
      (node (ref "IC10") (pin "1") (pinfunction "OUT_1") (pintype "output"))
      (node (ref "IC10") (pin "2") (pinfunction "-IN_2") (pintype "input"))
      (node (ref "U1") (pin "W10") (pinfunction "AIN1_W10") (pintype "bidirectional"))
    )
    (net (code "8") (name "/AIN2") (class "Default")
      (node (ref "IC10") (pin "6") (pinfunction "-IN_6") (pintype "input"))
      (node (ref "IC10") (pin "7") (pinfunction "OUT_7") (pintype "output"))
      (node (ref "U1") (pin "V10") (pinfunction "AIN2_V10") (pintype "bidirectional"))
    )
    (net (code "9") (name "/AIN3") (class "Default")
      (node (ref "IC11") (pin "1") (pinfunction "OUT_1") (pintype "output"))
      (node (ref "IC11") (pin "2") (pinfunction "-IN_2") (pintype "input"))
      (node (ref "U1") (pin "V9") (pinfunction "AIN3_V9") (pintype "bidirectional"))
    )
    (net (code "10") (name "/AIN4") (class "Default")
      (node (ref "IC11") (pin "6") (pinfunction "-IN_6") (pintype "input"))
      (node (ref "IC11") (pin "7") (pinfunction "OUT_7") (pintype "output"))
      (node (ref "U1") (pin "Y11") (pinfunction "AIN4_Y11") (pintype "bidirectional"))
    )
    (net (code "11") (name "/AIN5") (class "Default")
      (node (ref "IC12") (pin "1") (pinfunction "OUT_1") (pintype "output"))
      (node (ref "IC12") (pin "2") (pinfunction "-IN_2") (pintype "input"))
      (node (ref "U1") (pin "W11") (pinfunction "AIN5_W11") (pintype "bidirectional"))
    )
    (net (code "12") (name "/AIN6") (class "Default")
      (node (ref "IC12") (pin "6") (pinfunction "-IN_6") (pintype "input"))
      (node (ref "IC12") (pin "7") (pinfunction "OUT_7") (pintype "output"))
      (node (ref "U1") (pin "V11") (pinfunction "AIN6_V11") (pintype "bidirectional"))
    )
    (net (code "13") (name "/AIN7") (class "Default")
      (node (ref "U1") (pin "U12") (pinfunction "PMIC_MUX_OUT_U12") (pintype "bidirectional"))
      (node (ref "U1") (pin "V12") (pinfunction "AIN7_V12") (pintype "bidirectional"))
    )
    (net (code "14") (name "/B03_NO") (class "Default")
      (node (ref "K3") (pin "NO") (pinfunction "S_NO") (pintype "passive"))
      (node (ref "X21") (pin "6") (pinfunction "SK_6") (pintype "passive"))
    )
    (net (code "15") (name "/BAT_SENSE") (class "Default")
      (node (ref "TP6") (pin "P$1") (pinfunction "TP_P$1") (pintype "bidirectional"))
      (node (ref "U1") (pin "E19") (pinfunction "PMIC_BAT_SENSE_E19") (pintype "bidirectional"))
    )
    (net (code "16") (name "/BO1_C") (class "Default")
      (node (ref "K1") (pin "C") (pinfunction "P_C") (pintype "passive"))
      (node (ref "X21") (pin "9") (pinfunction "SK_9") (pintype "passive"))
    )
    (net (code "17") (name "/BO1_NO") (class "Default")
      (node (ref "K1") (pin "NO") (pinfunction "S_NO") (pintype "passive"))
      (node (ref "X21") (pin "10") (pinfunction "SK_10") (pintype "passive"))
    )
    (net (code "18") (name "/BO2_C") (class "Default")
      (node (ref "K2") (pin "C") (pinfunction "P_C") (pintype "passive"))
      (node (ref "X21") (pin "7") (pinfunction "SK_7") (pintype "passive"))
    )
    (net (code "19") (name "/BO2_NO") (class "Default")
      (node (ref "K2") (pin "NO") (pinfunction "S_NO") (pintype "passive"))
      (node (ref "X21") (pin "8") (pinfunction "SK_8") (pintype "passive"))
    )
    (net (code "20") (name "/BO3_C") (class "Default")
      (node (ref "K3") (pin "C") (pinfunction "P_C") (pintype "passive"))
      (node (ref "X21") (pin "5") (pinfunction "SK_5") (pintype "passive"))
    )
    (net (code "21") (name "/BO4_C") (class "Default")
      (node (ref "K4") (pin "C") (pinfunction "P_C") (pintype "passive"))
      (node (ref "X21") (pin "3") (pinfunction "SK_3") (pintype "passive"))
    )
    (net (code "22") (name "/BO4_NO") (class "Default")
      (node (ref "K4") (pin "NO") (pinfunction "S_NO") (pintype "passive"))
      (node (ref "X21") (pin "4") (pinfunction "SK_4") (pintype "passive"))
    )
    (net (code "23") (name "/B_UART0_RX") (class "Default")
      (node (ref "R27") (pin "2") (pinfunction "2_2") (pintype "passive"))
      (node (ref "U6") (pin "2") (pinfunction "1A_2") (pintype "input"))
      (node (ref "X6") (pin "4") (pinfunction "4_4") (pintype "bidirectional"))
    )
    (net (code "24") (name "/B_UART0_TX") (class "Default")
      (node (ref "U6") (pin "3") (pinfunction "2Y_3") (pintype "output"))
      (node (ref "X6") (pin "5") (pinfunction "5_5") (pintype "bidirectional"))
    )
    (net (code "25") (name "/CAN1_RXD") (class "Default")
      (node (ref "D802") (pin "1") (pinfunction "A_1") (pintype "passive"))
      (node (ref "U1") (pin "Y7") (pinfunction "UART1_RXD_Y7") (pintype "bidirectional"))
      (node (ref "U28") (pin "4") (pinfunction "RXD_4") (pintype "output"))
    )
    (net (code "26") (name "/CAN1_TXD") (class "Default")
      (node (ref "D801") (pin "1") (pinfunction "A_1") (pintype "passive"))
      (node (ref "U1") (pin "W7") (pinfunction "UART1_TXD_W7") (pintype "bidirectional"))
      (node (ref "U28") (pin "1") (pinfunction "TXD_1") (pintype "input"))
    )
    (net (code "27") (name "/CAN_H") (class "Default")
      (node (ref "D805") (pin "2") (pinfunction "2_2") (pintype "passive"))
      (node (ref "U28") (pin "7") (pinfunction "CANH_7") (pintype "bidirectional"))
      (node (ref "X8") (pin "2") (pinfunction "SK_2") (pintype "passive"))
    )
    (net (code "28") (name "/CAN_L") (class "Default")
      (node (ref "D805") (pin "1") (pinfunction "1_1") (pintype "passive"))
      (node (ref "U28") (pin "6") (pinfunction "CANL_6") (pintype "bidirectional"))
      (node (ref "X8") (pin "1") (pinfunction "SK_1") (pintype "passive"))
    )
    (net (code "29") (name "/CLKOUT2") (class "Default")
      (node (ref "C2") (pin "2") (pinfunction "2_2") (pintype "passive"))
      (node (ref "R3") (pin "2") (pinfunction "2_2") (pintype "passive"))
      (node (ref "X4") (pin "18") (pinfunction "EMU3_18") (pintype "bidirectional"))
    )
    (net (code "30") (name "/CRS") (class "Default")
      (node (ref "ER124") (pin "1") (pinfunction "1_1") (pintype "passive"))
      (node (ref "U27") (pin "14") (pinfunction "CRS_14") (pintype "bidirectional"))
    )
    (net (code "31") (name "/EHRPWM1A") (class "Default")
      (node (ref "J4") (pin "1") (pinfunction "1_1") (pintype "bidirectional"))
      (node (ref "U1") (pin "C13") (pinfunction "GPMC_A2_C13") (pintype "bidirectional"))
    )
    (net (code "32") (name "/EHRPWM1B") (class "Default")
      (node (ref "U1") (pin "A12") (pinfunction "GPMC_A3_A12") (pintype "bidirectional"))
    )
    (net (code "33") (name "/EHRPWM2A") (class "Default")
      (node (ref "J5") (pin "1") (pinfunction "1_1") (pintype "bidirectional"))
      (node (ref "U1") (pin "A17") (pinfunction "GPMC_AD8_A17") (pintype "bidirectional"))
    )
    (net (code "34") (name "/EHRPWM2B") (class "Default")
      (node (ref "J6") (pin "1") (pinfunction "1_1") (pintype "bidirectional"))
      (node (ref "U1") (pin "C16") (pinfunction "GPMC_AD9_C16") (pintype "bidirectional"))
    )
    (net (code "35") (name "/E_LED_GRN") (class "Default")
      (node (ref "U27") (pin "3") (pinfunction "LED1/REGOFF_3") (pintype "bidirectional"))
      (node (ref "X2") (pin "9") (pinfunction "GRNA_9") (pintype "passive"))
    )
    (net (code "36") (name "/E_LED_YEL") (class "Default")
      (node (ref "ER120") (pin "2") (pinfunction "2_2") (pintype "passive"))
      (node (ref "U27") (pin "2") (pinfunction "LED2/~{INTSEL}_2") (pintype "bidirectional"))
      (node (ref "X2") (pin "12") (pinfunction "YELA_12") (pintype "passive"))
    )
    (net (code "37") (name "/GPIO0_7") (class "Default")
      (node (ref "U1") (pin "V15") (pinfunction "ECAP0_IN_PWM0_OUT_V15") (pintype "bidirectional"))
      (node (ref "U29") (pin "2") (pinfunction "~{RE}_2") (pintype "input"))
      (node (ref "U29") (pin "3") (pinfunction "DE_3") (pintype "input"))
    )
    (net (code "38") (name "/GPIO0_18") (class "Default")
      (node (ref "U1") (pin "K3") (pinfunction "USB0_DRVVBUS_K3") (pintype "bidirectional"))
    )
    (net (code "39") (name "/GPIO1_12") (class "Default")
      (node (ref "IC2") (pin "2") (pinfunction "I2_2") (pintype "input"))
      (node (ref "U1") (pin "C15") (pinfunction "GPMC_AD12_C15") (pintype "bidirectional"))
    )
    (net (code "40") (name "/GPIO1_13") (class "Default")
      (node (ref "IC2") (pin "3") (pinfunction "I3_3") (pintype "input"))
      (node (ref "U1") (pin "B15") (pinfunction "GPMC_AD13_B15") (pintype "bidirectional"))
    )
    (net (code "41") (name "/GPIO1_14") (class "Default")
      (node (ref "IC2") (pin "4") (pinfunction "I4_4") (pintype "input"))
      (node (ref "U1") (pin "A15") (pinfunction "GPMC_AD14_A15") (pintype "bidirectional"))
    )
    (net (code "42") (name "/GPIO1_15") (class "Default")
      (node (ref "IC2") (pin "5") (pinfunction "I5_5") (pintype "input"))
      (node (ref "U1") (pin "C14") (pinfunction "GPMC_AD15_C14") (pintype "bidirectional"))
    )
    (net (code "43") (name "/GPIO1_16") (class "Default")
      (node (ref "U1") (pin "B14") (pinfunction "GPMC_CSN3_B14") (pintype "bidirectional"))
      (node (ref "U40") (pin "7") (pinfunction "DE_7") (pintype "passive"))
    )
    (net (code "44") (name "/GPIO1_17") (class "Default")
      (node (ref "IC2") (pin "1") (pinfunction "I1_1") (pintype "input"))
      (node (ref "U1") (pin "B13") (pinfunction "GPMC_A1_B13") (pintype "bidirectional"))
    )
    (net (code "45") (name "/GPIO1_28") (class "Default")
      (node (ref "U1") (pin "C9") (pinfunction "GPMC_BEN1_C9") (pintype "bidirectional"))
      (node (ref "U40") (pin "6") (pinfunction "~{RE}_6") (pintype "passive"))
    )
    (net (code "46") (name "/I2C0_SCL") (class "Default")
      (node (ref "R12") (pin "1") (pinfunction "1_1") (pintype "passive"))
      (node (ref "TP18") (pin "P$1") (pinfunction "TP_P$1") (pintype "bidirectional"))
      (node (ref "U1") (pin "U8") (pinfunction "PMIC_SCL_U8") (pintype "bidirectional"))
      (node (ref "U1") (pin "V8") (pinfunction "I2C0_SCL_V8") (pintype "bidirectional"))
      (node (ref "U16") (pin "29") (pinfunction "SM_CLK_29") (pintype "bidirectional"))
    )
    (net (code "47") (name "/I2C0_SDA") (class "Default")
      (node (ref "R13") (pin "1") (pinfunction "1_1") (pintype "passive"))
      (node (ref "TP17") (pin "P$1") (pinfunction "TP_P$1") (pintype "bidirectional"))
      (node (ref "U1") (pin "U7") (pinfunction "PMIC_SDA_U7") (pintype "bidirectional"))
      (node (ref "U1") (pin "V7") (pinfunction "I2C0_SDA_V7") (pintype "bidirectional"))
      (node (ref "U16") (pin "30") (pinfunction "SM_DAT_30") (pintype "bidirectional"))
    )
    (net (code "48") (name "/I2C2_SCL") (class "Default")
      (node (ref "R169") (pin "1") (pinfunction "1_1") (pintype "passive"))
      (node (ref "RTC1") (pin "8") (pinfunction "SCL_8") (pintype "bidirectional"))
      (node (ref "TP20") (pin "P$1") (pinfunction "TP_P$1") (pintype "bidirectional"))
      (node (ref "U1") (pin "Y8") (pinfunction "UART1_RTSN_Y8") (pintype "bidirectional"))
    )
    (net (code "49") (name "/I2C2_SDA") (class "Default")
      (node (ref "R170") (pin "1") (pinfunction "1_1") (pintype "passive"))
      (node (ref "RTC1") (pin "7") (pinfunction "SDA_7") (pintype "bidirectional"))
      (node (ref "TP19") (pin "P$1") (pinfunction "TP_P$1") (pintype "bidirectional"))
      (node (ref "U1") (pin "W8") (pinfunction "UART1_CTSN_W8") (pintype "bidirectional"))
    )
    (net (code "50") (name "/ISO_485_A") (class "Default")
      (node (ref "D405") (pin "1") (pinfunction "1_1") (pintype "passive"))
      (node (ref "F401") (pin "3") (pinfunction "3_3") (pintype "passive"))
      (node (ref "U40") (pin "11") (pinfunction "Y_11") (pintype "passive"))
      (node (ref "U40") (pin "14") (pinfunction "A_14") (pintype "passive"))
    )
    (net (code "51") (name "/ISO_485_B") (class "Default")
      (node (ref "D405") (pin "2") (pinfunction "2_2") (pintype "passive"))
      (node (ref "F402") (pin "3") (pinfunction "3_3") (pintype "passive"))
      (node (ref "U40") (pin "12") (pinfunction "Z_12") (pintype "passive"))
      (node (ref "U40") (pin "13") (pinfunction "B_13") (pintype "passive"))
    )
    (net (code "52") (name "/ISO_VCC") (class "Default")
      (node (ref "C402") (pin "1") (pinfunction "1_1") (pintype "passive"))
      (node (ref "C406") (pin "+") (pinfunction "+_+") (pintype "passive"))
      (node (ref "U40") (pin "16") (pinfunction "VCC2_16") (pintype "power_in"))
      (node (ref "VREG4") (pin "5") (pinfunction "VOUT_5") (pintype "output"))
    )
    (net (code "53") (name "/ISO_VIN") (class "Default")
      (node (ref "C403") (pin "1") (pinfunction "1_1") (pintype "passive"))
      (node (ref "C405") (pin "1") (pinfunction "1_1") (pintype "passive"))
      (node (ref "D403") (pin "C") (pinfunction "C_C") (pintype "passive"))
      (node (ref "D404") (pin "C") (pinfunction "C_C") (pintype "passive"))
      (node (ref "VREG4") (pin "1") (pinfunction "VIN_1") (pintype "input"))
      (node (ref "VREG4") (pin "3") (pinfunction "ON/~{OFF}_3") (pintype "passive"))
    )
    (net (code "54") (name "/JTAG_EMU0") (class "Default")
      (node (ref "R40") (pin "1") (pinfunction "1_1") (pintype "passive"))
      (node (ref "U1") (pin "V18") (pinfunction "EMU0_V18") (pintype "bidirectional"))
      (node (ref "X4") (pin "13") (pinfunction "EMU0_13") (pintype "bidirectional"))
    )
    (net (code "55") (name "/JTAG_EMU1") (class "Default")
      (node (ref "R41") (pin "1") (pinfunction "1_1") (pintype "passive"))
      (node (ref "U1") (pin "V19") (pinfunction "EMU1_V19") (pintype "bidirectional"))
      (node (ref "X4") (pin "14") (pinfunction "EMU1_14") (pintype "bidirectional"))
    )
    (net (code "56") (name "/JTAG_TCK") (class "Default")
      (node (ref "U1") (pin "Y19") (pinfunction "TCK_Y19") (pintype "bidirectional"))
      (node (ref "X4") (pin "11") (pinfunction "TCK_11") (pintype "bidirectional"))
      (node (ref "X4") (pin "9") (pinfunction "TCKRTN_9") (pintype "bidirectional"))
    )
    (net (code "57") (name "/JTAG_TDI") (class "Default")
      (node (ref "U1") (pin "Y18") (pinfunction "TDI_Y18") (pintype "bidirectional"))
      (node (ref "X4") (pin "3") (pinfunction "TDI_3") (pintype "bidirectional"))
    )
    (net (code "58") (name "/JTAG_TDO") (class "Default")
      (node (ref "U1") (pin "W18") (pinfunction "TDO_W18") (pintype "bidirectional"))
      (node (ref "X4") (pin "7") (pinfunction "TDO_7") (pintype "bidirectional"))
    )
    (net (code "59") (name "/JTAG_TMS") (class "Default")
      (node (ref "U1") (pin "W19") (pinfunction "TMS_W19") (pintype "bidirectional"))
      (node (ref "X4") (pin "1") (pinfunction "TMS_1") (pintype "bidirectional"))
    )
    (net (code "60") (name "/JTAG_TRSTN") (class "Default")
      (node (ref "R39") (pin "2") (pinfunction "2_2") (pintype "passive"))
      (node (ref "U1") (pin "W20") (pinfunction "TRSTN_W20") (pintype "bidirectional"))
      (node (ref "X4") (pin "2") (pinfunction "TRSTN_2") (pintype "bidirectional"))
    )
    (net (code "61") (name "/LCD_DATA0") (class "Default")
      (node (ref "R68") (pin "2") (pinfunction "2_2") (pintype "passive"))
      (node (ref "R85") (pin "1") (pinfunction "1_1") (pintype "passive"))
      (node (ref "U1") (pin "T18") (pinfunction "LCD_DATA0_T18") (pintype "bidirectional"))
      (node (ref "X7") (pin "19") (pinfunction "19_19") (pintype "bidirectional"))
    )
    (net (code "62") (name "/LCD_DATA1") (class "Default")
      (node (ref "R67") (pin "2") (pinfunction "2_2") (pintype "passive"))
      (node (ref "R84") (pin "1") (pinfunction "1_1") (pintype "passive"))
      (node (ref "U1") (pin "T19") (pinfunction "LCD_DATA1_T19") (pintype "bidirectional"))
      (node (ref "X7") (pin "20") (pinfunction "20_20") (pintype "bidirectional"))
    )
    (net (code "63") (name "/LCD_DATA2") (class "Default")
      (node (ref "R66") (pin "2") (pinfunction "2_2") (pintype "passive"))
      (node (ref "R69") (pin "1") (pinfunction "1_1") (pintype "passive"))
      (node (ref "R83") (pin "1") (pinfunction "1_1") (pintype "passive"))
      (node (ref "U1") (pin "T20") (pinfunction "LCD_DATA2_T20") (pintype "bidirectional"))
      (node (ref "X7") (pin "17") (pinfunction "17_17") (pintype "bidirectional"))
    )
    (net (code "64") (name "/LCD_DATA3") (class "Default")
      (node (ref "R65") (pin "2") (pinfunction "2_2") (pintype "passive"))
      (node (ref "R82") (pin "1") (pinfunction "1_1") (pintype "passive"))
      (node (ref "U1") (pin "R18") (pinfunction "LCD_DATA3_R18") (pintype "bidirectional"))
      (node (ref "X7") (pin "18") (pinfunction "18_18") (pintype "bidirectional"))
    )
    (net (code "65") (name "/LCD_DATA4") (class "Default")
      (node (ref "R64") (pin "2") (pinfunction "2_2") (pintype "passive"))
      (node (ref "R81") (pin "1") (pinfunction "1_1") (pintype "passive"))
      (node (ref "U1") (pin "R19") (pinfunction "LCD_DATA4_R19") (pintype "bidirectional"))
      (node (ref "X7") (pin "15") (pinfunction "15_15") (pintype "bidirectional"))
    )
    (net (code "66") (name "/LCD_DATA5") (class "Default")
      (node (ref "R63") (pin "2") (pinfunction "2_2") (pintype "passive"))
      (node (ref "R80") (pin "1") (pinfunction "1_1") (pintype "passive"))
      (node (ref "U1") (pin "R20") (pinfunction "LCD_DATA5_R20") (pintype "bidirectional"))
      (node (ref "X7") (pin "16") (pinfunction "16_16") (pintype "bidirectional"))
    )
    (net (code "67") (name "/LCD_DATA6") (class "Default")
      (node (ref "R62") (pin "2") (pinfunction "2_2") (pintype "passive"))
      (node (ref "R79") (pin "1") (pinfunction "1_1") (pintype "passive"))
      (node (ref "U1") (pin "P18") (pinfunction "LCD_DATA6_P18") (pintype "bidirectional"))
      (node (ref "X7") (pin "13") (pinfunction "13_13") (pintype "bidirectional"))
    )
    (net (code "68") (name "/LCD_DATA7") (class "Default")
      (node (ref "R61") (pin "2") (pinfunction "2_2") (pintype "passive"))
      (node (ref "R78") (pin "1") (pinfunction "1_1") (pintype "passive"))
      (node (ref "U1") (pin "P19") (pinfunction "LCD_DATA7_P19") (pintype "bidirectional"))
      (node (ref "X7") (pin "14") (pinfunction "14_14") (pintype "bidirectional"))
    )
    (net (code "69") (name "/LCD_DATA8") (class "Default")
      (node (ref "R60") (pin "2") (pinfunction "2_2") (pintype "passive"))
      (node (ref "R77") (pin "1") (pinfunction "1_1") (pintype "passive"))
      (node (ref "U1") (pin "P20") (pinfunction "LCD_DATA8_P20") (pintype "bidirectional"))
      (node (ref "X7") (pin "11") (pinfunction "11_11") (pintype "bidirectional"))
    )
    (net (code "70") (name "/LCD_DATA9") (class "Default")
      (node (ref "R59") (pin "2") (pinfunction "2_2") (pintype "passive"))
      (node (ref "R76") (pin "1") (pinfunction "1_1") (pintype "passive"))
      (node (ref "U1") (pin "N18") (pinfunction "LCD_DATA9_N18") (pintype "bidirectional"))
      (node (ref "X7") (pin "12") (pinfunction "12_12") (pintype "bidirectional"))
    )
    (net (code "71") (name "/LCD_DATA10") (class "Default")
      (node (ref "R58") (pin "2") (pinfunction "2_2") (pintype "passive"))
      (node (ref "R75") (pin "1") (pinfunction "1_1") (pintype "passive"))
      (node (ref "U1") (pin "N19") (pinfunction "LCD_DATA10_N19") (pintype "bidirectional"))
      (node (ref "X7") (pin "10") (pinfunction "10_10") (pintype "bidirectional"))
    )
    (net (code "72") (name "/LCD_DATA11") (class "Default")
      (node (ref "R57") (pin "2") (pinfunction "2_2") (pintype "passive"))
      (node (ref "R74") (pin "1") (pinfunction "1_1") (pintype "passive"))
      (node (ref "U1") (pin "N20") (pinfunction "LCD_DATA11_N20") (pintype "bidirectional"))
      (node (ref "X7") (pin "8") (pinfunction "8_8") (pintype "bidirectional"))
    )
    (net (code "73") (name "/LCD_DATA12") (class "Default")
      (node (ref "R56") (pin "2") (pinfunction "2_2") (pintype "passive"))
      (node (ref "R73") (pin "1") (pinfunction "1_1") (pintype "passive"))
      (node (ref "U1") (pin "M18") (pinfunction "LCD_DATA12_M18") (pintype "bidirectional"))
      (node (ref "X7") (pin "9") (pinfunction "9_9") (pintype "bidirectional"))
    )
    (net (code "74") (name "/LCD_DATA13") (class "Default")
      (node (ref "R55") (pin "2") (pinfunction "2_2") (pintype "passive"))
      (node (ref "R72") (pin "1") (pinfunction "1_1") (pintype "passive"))
      (node (ref "U1") (pin "M19") (pinfunction "LCD_DATA13_M19") (pintype "bidirectional"))
      (node (ref "X7") (pin "7") (pinfunction "7_7") (pintype "bidirectional"))
    )
    (net (code "75") (name "/LCD_DATA14") (class "Default")
      (node (ref "R54") (pin "2") (pinfunction "2_2") (pintype "passive"))
      (node (ref "R71") (pin "1") (pinfunction "1_1") (pintype "passive"))
      (node (ref "U1") (pin "M20") (pinfunction "LCD_DATA14_M20") (pintype "bidirectional"))
      (node (ref "X7") (pin "5") (pinfunction "5_5") (pintype "bidirectional"))
    )
    (net (code "76") (name "/LCD_DATA15") (class "Default")
      (node (ref "R53") (pin "2") (pinfunction "2_2") (pintype "passive"))
      (node (ref "R70") (pin "1") (pinfunction "1_1") (pintype "passive"))
      (node (ref "U1") (pin "L18") (pinfunction "LCD_DATA15_L18") (pintype "bidirectional"))
      (node (ref "X7") (pin "6") (pinfunction "6_6") (pintype "bidirectional"))
    )
    (net (code "77") (name "/LCD_DE") (class "Default")
      (node (ref "R28") (pin "2") (pinfunction "2_2") (pintype "passive"))
      (node (ref "X7") (pin "4") (pinfunction "4_4") (pintype "bidirectional"))
    )
    (net (code "78") (name "/LCD_HSYNC") (class "Default")
      (node (ref "R29") (pin "2") (pinfunction "2_2") (pintype "passive"))
      (node (ref "X7") (pin "3") (pinfunction "3_3") (pintype "bidirectional"))
    )
    (net (code "79") (name "/LCD_PCLK") (class "Default")
      (node (ref "R31") (pin "2") (pinfunction "2_2") (pintype "passive"))
      (node (ref "X7") (pin "2") (pinfunction "2_2") (pintype "bidirectional"))
    )
    (net (code "80") (name "/LCD_VSYNC") (class "Default")
      (node (ref "R30") (pin "2") (pinfunction "2_2") (pintype "passive"))
      (node (ref "X7") (pin "1") (pinfunction "1_1") (pintype "bidirectional"))
    )
    (net (code "81") (name "/LDO_PGOOD") (class "Default")
      (node (ref "TP22") (pin "TP") (pinfunction "TP_TP") (pintype "input"))
      (node (ref "U1") (pin "D13") (pinfunction "RTC_PWRONRSTN_D13") (pintype "bidirectional"))
      (node (ref "U1") (pin "D14") (pinfunction "PMIC_LDO_PGOOD_D14") (pintype "output"))
    )
    (net (code "82") (name "/MDIO_CLK") (class "Default")
      (node (ref "U1") (pin "W1") (pinfunction "MDC_W1") (pintype "bidirectional"))
      (node (ref "U27") (pin "17") (pinfunction "MDC_17") (pintype "input"))
    )
    (net (code "83") (name "/MDIO_DATA") (class "Default")
      (node (ref "ER105") (pin "2") (pinfunction "2_2") (pintype "passive"))
      (node (ref "U1") (pin "V1") (pinfunction "MDIO_V1") (pintype "bidirectional"))
      (node (ref "U27") (pin "16") (pinfunction "MDIO_16") (pintype "bidirectional"))
    )
    (net (code "84") (name "/MII1_COL") (class "Default")
      (node (ref "ER123") (pin "2") (pinfunction "2_2") (pintype "passive"))
      (node (ref "U1") (pin "R2") (pinfunction "MII1_COL_R2") (pintype "bidirectional"))
    )
    (net (code "85") (name "/MII1_CRS") (class "Default")
      (node (ref "ER124") (pin "2") (pinfunction "2_2") (pintype "passive"))
      (node (ref "U1") (pin "R3") (pinfunction "MII1_CRS_R3") (pintype "bidirectional"))
    )
    (net (code "86") (name "/MII1_RXCLK") (class "Default")
      (node (ref "ER116") (pin "2") (pinfunction "2_2") (pintype "passive"))
      (node (ref "U1") (pin "T1") (pinfunction "MII1_RX_CLK_T1") (pintype "bidirectional"))
    )
    (net (code "87") (name "/MII1_RXD0") (class "Default")
      (node (ref "ER113") (pin "2") (pinfunction "2_2") (pintype "passive"))
      (node (ref "U1") (pin "T3") (pinfunction "MII1_RXD0_T3") (pintype "bidirectional"))
    )
    (net (code "88") (name "/MII1_RXD1") (class "Default")
      (node (ref "ER112") (pin "2") (pinfunction "2_2") (pintype "passive"))
      (node (ref "U1") (pin "U1") (pinfunction "MII1_RXD1_U1") (pintype "bidirectional"))
    )
    (net (code "89") (name "/MII1_RXD2") (class "Default")
      (node (ref "ER111") (pin "2") (pinfunction "2_2") (pintype "passive"))
      (node (ref "U1") (pin "U2") (pinfunction "MII1_RXD2_U2") (pintype "bidirectional"))
    )
    (net (code "90") (name "/MII1_RXD3") (class "Default")
      (node (ref "ER110") (pin "2") (pinfunction "2_2") (pintype "passive"))
      (node (ref "U1") (pin "U3") (pinfunction "MII1_RXD3_U3") (pintype "bidirectional"))
    )
    (net (code "91") (name "/MII1_RXDV") (class "Default")
      (node (ref "ER114") (pin "2") (pinfunction "2_2") (pintype "passive"))
      (node (ref "U1") (pin "R1") (pinfunction "MII1_RX_DV_R1") (pintype "bidirectional"))
    )
    (net (code "92") (name "/MII1_RXERR") (class "Default")
      (node (ref "ER118") (pin "2") (pinfunction "2_2") (pintype "passive"))
      (node (ref "U1") (pin "T2") (pinfunction "MII1_RX_ER_T2") (pintype "bidirectional"))
    )
    (net (code "93") (name "/MII1_TXCLK") (class "Default")
      (node (ref "ER119") (pin "2") (pinfunction "2_2") (pintype "passive"))
      (node (ref "U1") (pin "N1") (pinfunction "MII1_TX_CLK_N1") (pintype "bidirectional"))
    )
    (net (code "94") (name "/MII1_TXD0") (class "Default")
      (node (ref "U1") (pin "N2") (pinfunction "MII1_TXD0_N2") (pintype "bidirectional"))
      (node (ref "U27") (pin "22") (pinfunction "TXD0_22") (pintype "input"))
    )
    (net (code "95") (name "/MII1_TXD1") (class "Default")
      (node (ref "U1") (pin "N3") (pinfunction "MII1_TXD1_N3") (pintype "bidirectional"))
      (node (ref "U27") (pin "23") (pinfunction "TXD1_23") (pintype "input"))
    )
    (net (code "96") (name "/MII1_TXD2") (class "Default")
      (node (ref "U1") (pin "P1") (pinfunction "MII1_TXD2_P1") (pintype "bidirectional"))
      (node (ref "U27") (pin "24") (pinfunction "TXD2_24") (pintype "input"))
    )
    (net (code "97") (name "/MII1_TXD3") (class "Default")
      (node (ref "U1") (pin "P2") (pinfunction "MII1_TXD3_P2") (pintype "bidirectional"))
      (node (ref "U27") (pin "25") (pinfunction "TXD3_25") (pintype "input"))
    )
    (net (code "98") (name "/MII1_TXEN") (class "Default")
      (node (ref "U1") (pin "P3") (pinfunction "MII1_TX_EN_P3") (pintype "bidirectional"))
      (node (ref "U27") (pin "21") (pinfunction "TXEN_21") (pintype "input"))
    )
    (net (code "99") (name "/MMC0_CD") (class "Default")
      (node (ref "R92") (pin "1") (pinfunction "1_1") (pintype "passive"))
      (node (ref "U1") (pin "V4") (pinfunction "SPI0_CS1_V4") (pintype "bidirectional"))
      (node (ref "X4") (pin "19") (pinfunction "EMU4_19") (pintype "bidirectional"))
      (node (ref "X5") (pin "12") (pinfunction "CARD_DETECTION_SWITCH_12") (pintype "bidirectional"))
    )
    (net (code "100") (name "/MMC0_CLK") (class "Default")
      (node (ref "R88") (pin "1") (pinfunction "1_1") (pintype "passive"))
      (node (ref "U1") (pin "W3") (pinfunction "MMC0_CLK_W3") (pintype "bidirectional"))
      (node (ref "X5") (pin "5") (pinfunction "CLK_5") (pintype "bidirectional"))
    )
    (net (code "101") (name "/MMC0_CMD") (class "Default")
      (node (ref "R87") (pin "1") (pinfunction "1_1") (pintype "passive"))
      (node (ref "U1") (pin "W2") (pinfunction "MMC0_CMD_W2") (pintype "bidirectional"))
      (node (ref "X5") (pin "3") (pinfunction "CMD_3") (pintype "bidirectional"))
    )
    (net (code "102") (name "/MMC0_DAT0") (class "Default")
      (node (ref "R89") (pin "1") (pinfunction "1_1") (pintype "passive"))
      (node (ref "U1") (pin "Y3") (pinfunction "MMC0_DAT0_Y3") (pintype "bidirectional"))
      (node (ref "X5") (pin "7") (pinfunction "DAT0_7") (pintype "bidirectional"))
    )
    (net (code "103") (name "/MMC0_DAT1") (class "Default")
      (node (ref "R90") (pin "1") (pinfunction "1_1") (pintype "passive"))
      (node (ref "U1") (pin "V3") (pinfunction "MMC0_DAT1_V3") (pintype "bidirectional"))
      (node (ref "X5") (pin "8") (pinfunction "DAT1_8") (pintype "bidirectional"))
    )
    (net (code "104") (name "/MMC0_DAT2") (class "Default")
      (node (ref "R86") (pin "1") (pinfunction "1_1") (pintype "passive"))
      (node (ref "U1") (pin "V2") (pinfunction "MMC0_DAT2_V2") (pintype "bidirectional"))
      (node (ref "X5") (pin "1") (pinfunction "DAT2_1") (pintype "bidirectional"))
    )
    (net (code "105") (name "/MMC0_DAT3") (class "Default")
      (node (ref "R91") (pin "1") (pinfunction "1_1") (pintype "passive"))
      (node (ref "U1") (pin "Y2") (pinfunction "MMC0_DAT3_Y2") (pintype "bidirectional"))
      (node (ref "X5") (pin "2") (pinfunction "CD/DAT3_2") (pintype "bidirectional"))
    )
    (net (code "106") (name "/MODE2") (class "Default")
      (node (ref "ER123") (pin "1") (pinfunction "1_1") (pintype "passive"))
      (node (ref "ER99") (pin "2") (pinfunction "2_2") (pintype "passive"))
      (node (ref "U27") (pin "15") (pinfunction "COL/CRS_DV/MODE2_15") (pintype "bidirectional"))
    )
    (net (code "107") (name "/OSC1_IN") (class "Default")
      (node (ref "R164") (pin "2") (pinfunction "2_2") (pintype "passive"))
      (node (ref "RTC1") (pin "1") (pinfunction "32KHZ_1") (pintype "output"))
      (node (ref "U1") (pin "Y13") (pinfunction "OSC1_IN_Y13") (pintype "bidirectional"))
    )
    (net (code "108") (name "/OSC1_OUT") (class "Default")
      (node (ref "U1") (pin "Y14") (pinfunction "OSC1_OUT_Y14") (pintype "bidirectional"))
    )
    (net (code "109") (name "/OSC_CTL") (class "Default")
      (node (ref "TP32") (pin "TP") (pinfunction "TP_TP") (pintype "input"))
      (node (ref "U1") (pin "M1") (pinfunction "OSC0_CTL_M1") (pintype "bidirectional"))
    )
    (net (code "110") (name "/PMIC_INT") (class "Default")
      (node (ref "TP24") (pin "TP") (pinfunction "TP_TP") (pintype "input"))
      (node (ref "U1") (pin "J17") (pinfunction "PMIC_NINT_J17") (pintype "output"))
      (node (ref "U1") (pin "K17") (pinfunction "EXTINTN_K17") (pintype "bidirectional"))
    )
    (net (code "111") (name "/PMIC_MUX_IN") (class "Default")
      (node (ref "R18") (pin "2") (pinfunction "2_2") (pintype "passive"))
      (node (ref "R22") (pin "1") (pinfunction "1_1") (pintype "passive"))
      (node (ref "U1") (pin "F19") (pinfunction "PMIC_MUX_IN_F19") (pintype "bidirectional"))
    )
    (net (code "112") (name "/PMIC_NRESET") (class "Default")
      (node (ref "J2") (pin "1") (pinfunction "1_1") (pintype "bidirectional"))
      (node (ref "U1") (pin "A19") (pinfunction "PMIC_NRESET_A19") (pintype "bidirectional"))
    )
    (net (code "113") (name "/PMIC_NWAKEUP") (class "Default")
      (node (ref "TP23") (pin "TP") (pinfunction "TP_TP") (pintype "input"))
      (node (ref "U1") (pin "G17") (pinfunction "PMIC_NWAKEUP_G17") (pintype "output"))
      (node (ref "U1") (pin "H17") (pinfunction "EXT_WAKEUP_H17") (pintype "bidirectional"))
    )
    (net (code "114") (name "/PMIC_PGOOD") (class "Default")
      (node (ref "TP26") (pin "TP") (pinfunction "TP_TP") (pintype "input"))
      (node (ref "U1") (pin "D11") (pinfunction "PWRONRSTN_D11") (pintype "bidirectional"))
      (node (ref "U1") (pin "D12") (pinfunction "PMIC_PGOOD_D12") (pintype "output"))
    )
    (net (code "115") (name "/PR1_PRU0_PRU_R30_6") (class "Default")
      (node (ref "U1") (pin "V17") (pinfunction "MCASP0_AXR1_V17") (pintype "bidirectional"))
    )
    (net (code "116") (name "/PR1_PRU0_PRU_R30_7") (class "Default")
      (node (ref "U1") (pin "V16") (pinfunction "MCASP0_AHCLKX_V16") (pintype "bidirectional"))
    )
    (net (code "117") (name "/PR1_UART0_RXD") (class "Default")
      (node (ref "U1") (pin "W4") (pinfunction "SPI0_D1_W4") (pintype "bidirectional"))
    )
    (net (code "118") (name "/PR1_UART0_TXD") (class "Default")
      (node (ref "U1") (pin "Y4") (pinfunction "SPI0_CS0_Y4") (pintype "bidirectional"))
    )
    (net (code "119") (name "/PWR_BUT") (class "Default")
      (node (ref "S2") (pin "2") (pinfunction "2_2") (pintype "bidirectional"))
      (node (ref "S2") (pin "4") (pinfunction "4_4") (pintype "bidirectional"))
      (node (ref "U1") (pin "A18") (pinfunction "PMIC_PB_IN_A18") (pintype "bidirectional"))
    )
    (net (code "120") (name "/PWR_EN") (class "Default")
      (node (ref "TP21") (pin "TP") (pinfunction "TP_TP") (pintype "input"))
      (node (ref "U1") (pin "D10") (pinfunction "PMIC_PWR_EN_D10") (pintype "input"))
      (node (ref "U1") (pin "D9") (pinfunction "PMIC_POWER_EN_D9") (pintype "output"))
    )
    (net (code "121") (name "/RTC_RST") (class "Default")
      (node (ref "R163") (pin "1") (pinfunction "1_1") (pintype "passive"))
      (node (ref "RTC1") (pin "4") (pinfunction "RST_4") (pintype "bidirectional"))
      (node (ref "U1") (pin "K20") (pinfunction "GPMC_CSN0_K20") (pintype "bidirectional"))
    )
    (net (code "122") (name "/RXD0") (class "Default")
      (node (ref "ER113") (pin "1") (pinfunction "1_1") (pintype "passive"))
      (node (ref "ER98") (pin "2") (pinfunction "2_2") (pintype "passive"))
      (node (ref "U27") (pin "11") (pinfunction "RXD0/MODE0_11") (pintype "bidirectional"))
    )
    (net (code "123") (name "/RXD1") (class "Default")
      (node (ref "ER100") (pin "2") (pinfunction "2_2") (pintype "passive"))
      (node (ref "ER112") (pin "1") (pinfunction "1_1") (pintype "passive"))
      (node (ref "U27") (pin "10") (pinfunction "RXD1/MODE1_10") (pintype "bidirectional"))
    )
    (net (code "124") (name "/RXD2") (class "Default")
      (node (ref "ER103") (pin "1") (pinfunction "1_1") (pintype "passive"))
      (node (ref "ER111") (pin "1") (pinfunction "1_1") (pintype "passive"))
      (node (ref "U27") (pin "9") (pinfunction "RXD2/RMIISEL_9") (pintype "bidirectional"))
    )
    (net (code "125") (name "/RXD3") (class "Default")
      (node (ref "ER102") (pin "1") (pinfunction "1_1") (pintype "passive"))
      (node (ref "ER110") (pin "1") (pinfunction "1_1") (pintype "passive"))
      (node (ref "U27") (pin "8") (pinfunction "RXD3/PHYAD2_8") (pintype "bidirectional"))
    )
    (net (code "126") (name "/RX_CLK") (class "Default")
      (node (ref "ER104") (pin "1") (pinfunction "1_1") (pintype "passive"))
      (node (ref "ER116") (pin "1") (pinfunction "1_1") (pintype "passive"))
      (node (ref "U27") (pin "7") (pinfunction "RXCLK/PHYAD1_7") (pintype "bidirectional"))
    )
    (net (code "127") (name "/RX_DV") (class "Default")
      (node (ref "ER114") (pin "1") (pinfunction "1_1") (pintype "passive"))
      (node (ref "U27") (pin "26") (pinfunction "RXDV_26") (pintype "bidirectional"))
    )
    (net (code "128") (name "/RX_ERR") (class "Default")
      (node (ref "ER101") (pin "1") (pinfunction "1_1") (pintype "passive"))
      (node (ref "ER118") (pin "1") (pinfunction "1_1") (pintype "passive"))
      (node (ref "U27") (pin "13") (pinfunction "RXER/RXD4/PHYAD0_13") (pintype "bidirectional"))
    )
    (net (code "129") (name "/RX_N") (class "Default")
      (node (ref "EC37") (pin "1") (pinfunction "1_1") (pintype "passive"))
      (node (ref "ER107") (pin "2") (pinfunction "2_2") (pintype "passive"))
      (node (ref "U27") (pin "30") (pinfunction "RXN_30") (pintype "bidirectional"))
      (node (ref "X2") (pin "6") (pinfunction "RXN_6") (pintype "passive"))
    )
    (net (code "130") (name "/RX_P") (class "Default")
      (node (ref "EC36") (pin "1") (pinfunction "1_1") (pintype "passive"))
      (node (ref "ER106") (pin "2") (pinfunction "2_2") (pintype "passive"))
      (node (ref "U27") (pin "31") (pinfunction "RXP_31") (pintype "bidirectional"))
      (node (ref "X2") (pin "3") (pinfunction "RXP_3") (pintype "passive"))
    )
    (net (code "131") (name "/SPI1_CS0") (class "Default")
      (node (ref "IC4") (pin "1") (pinfunction "SH/~{LD}_1") (pintype "input"))
      (node (ref "IC5") (pin "1") (pinfunction "SH/~{LD}_1") (pintype "input"))
      (node (ref "U1") (pin "W17") (pinfunction "MCASP0_AHCLKR_W17") (pintype "bidirectional"))
    )
    (net (code "132") (name "/SPI1_D0") (class "Default")
      (node (ref "IC4") (pin "9") (pinfunction "QH_9") (pintype "output"))
      (node (ref "U1") (pin "Y16") (pinfunction "MCASP0_FSX_Y16") (pintype "bidirectional"))
    )
    (net (code "133") (name "/SPI1_D1") (class "Default")
      (node (ref "U1") (pin "W16") (pinfunction "MCASP0_AXR0_W16") (pintype "bidirectional"))
    )
    (net (code "134") (name "/SPI1_SCLK") (class "Default")
      (node (ref "IC4") (pin "2") (pinfunction "CLK_2") (pintype "input"))
      (node (ref "IC5") (pin "2") (pinfunction "CLK_2") (pintype "input"))
      (node (ref "U1") (pin "Y17") (pinfunction "MCASP0_ACLKX_Y17") (pintype "bidirectional"))
    )
    (net (code "135") (name "/SYS_RESETN") (class "Default")
      (node (ref "C14") (pin "1") (pinfunction "1_1") (pintype "passive"))
      (node (ref "R6") (pin "2") (pinfunction "2_2") (pintype "passive"))
      (node (ref "R8") (pin "1") (pinfunction "1_1") (pintype "passive"))
      (node (ref "TP31") (pin "TP") (pinfunction "TP_TP") (pintype "input"))
      (node (ref "U1") (pin "B17") (pinfunction "WARMRSTN_B17") (pintype "bidirectional"))
      (node (ref "U16") (pin "17") (pinfunction "LRESET#_17") (pintype "bidirectional"))
      (node (ref "U27") (pin "19") (pinfunction "~{RST}_19") (pintype "bidirectional"))
      (node (ref "X4") (pin "15") (pinfunction "SRST_15") (pintype "bidirectional"))
    )
    (net (code "136") (name "/TEMP_SENSE") (class "Default")
      (node (ref "TP7") (pin "P$1") (pinfunction "TP_P$1") (pintype "bidirectional"))
      (node (ref "U1") (pin "E20") (pinfunction "PMIC_TS_E20") (pintype "bidirectional"))
    )
    (net (code "137") (name "/TPM_GPIO0") (class "Default")
      (node (ref "U1") (pin "W15") (pinfunction "MCASP0_FSR_W15") (pintype "bidirectional"))
      (node (ref "U16") (pin "12") (pinfunction "GPIO_12") (pintype "bidirectional"))
    )
    (net (code "138") (name "/TPM_GPIO1") (class "Default")
      (node (ref "TP9") (pin "P$1") (pinfunction "TP_P$1") (pintype "bidirectional"))
      (node (ref "U1") (pin "V6") (pinfunction "UART0_CTSN_V6") (pintype "bidirectional"))
      (node (ref "U16") (pin "3") (pinfunction "GPIO-EXPRESS-00_3") (pintype "bidirectional"))
    )
    (net (code "139") (name "/TPM_GPIO2") (class "Default")
      (node (ref "TP10") (pin "P$1") (pinfunction "TP_P$1") (pintype "bidirectional"))
      (node (ref "U1") (pin "V5") (pinfunction "UART0_RTSN_V5") (pintype "bidirectional"))
      (node (ref "U16") (pin "4") (pinfunction "PP/GPIO_4") (pintype "bidirectional"))
    )
    (net (code "140") (name "/TX_CLK") (class "Default")
      (node (ref "ER119") (pin "1") (pinfunction "1_1") (pintype "passive"))
      (node (ref "U27") (pin "20") (pinfunction "TXCLK_20") (pintype "bidirectional"))
    )
    (net (code "141") (name "/TX_N") (class "Default")
      (node (ref "EC39") (pin "1") (pinfunction "1_1") (pintype "passive"))
      (node (ref "ER109") (pin "2") (pinfunction "2_2") (pintype "passive"))
      (node (ref "U27") (pin "28") (pinfunction "TXN_28") (pintype "bidirectional"))
      (node (ref "X2") (pin "2") (pinfunction "TXN_2") (pintype "passive"))
    )
    (net (code "142") (name "/TX_P") (class "Default")
      (node (ref "EC38") (pin "1") (pinfunction "1_1") (pintype "passive"))
      (node (ref "ER108") (pin "2") (pinfunction "2_2") (pintype "passive"))
      (node (ref "U27") (pin "29") (pinfunction "TXP_29") (pintype "bidirectional"))
      (node (ref "X2") (pin "1") (pinfunction "TXP_1") (pintype "passive"))
    )
    (net (code "143") (name "/UART0_RX") (class "Default")
      (node (ref "U1") (pin "Y6") (pinfunction "UART0_RXD_Y6") (pintype "bidirectional"))
      (node (ref "U6") (pin "6") (pinfunction "1Y_6") (pintype "output"))
    )
    (net (code "144") (name "/UART0_TX") (class "Default")
      (node (ref "U1") (pin "W6") (pinfunction "UART0_TXD_W6") (pintype "bidirectional"))
      (node (ref "U6") (pin "5") (pinfunction "2A_5") (pintype "input"))
    )
    (net (code "145") (name "/UART2_RXD") (class "Default")
      (node (ref "D302") (pin "1") (pinfunction "A_1") (pintype "passive"))
      (node (ref "U1") (pin "Y5") (pinfunction "SPI0_SCLK_Y5") (pintype "bidirectional"))
      (node (ref "U29") (pin "1") (pinfunction "RO_1") (pintype "output"))
    )
    (net (code "146") (name "/UART2_TXD") (class "Default")
      (node (ref "D301") (pin "1") (pinfunction "A_1") (pintype "passive"))
      (node (ref "U1") (pin "W5") (pinfunction "SPI0_D0_W5") (pintype "bidirectional"))
      (node (ref "U29") (pin "4") (pinfunction "DI_4") (pintype "input"))
    )
    (net (code "147") (name "/UART4_RXD") (class "Default")
      (node (ref "D402") (pin "1") (pinfunction "A_1") (pintype "passive"))
      (node (ref "U1") (pin "B9") (pinfunction "GPMC_WAIT0_B9") (pintype "bidirectional"))
      (node (ref "U40") (pin "5") (pinfunction "R_5") (pintype "passive"))
    )
    (net (code "148") (name "/UART4_TXD") (class "Default")
      (node (ref "D401") (pin "1") (pinfunction "A_1") (pintype "passive"))
      (node (ref "U1") (pin "A9") (pinfunction "GPMC_WPN_A9") (pintype "bidirectional"))
      (node (ref "U40") (pin "8") (pinfunction "D_8") (pintype "passive"))
    )
    (net (code "149") (name "/USB0_ID") (class "Default")
      (node (ref "U1") (pin "L1") (pinfunction "USB0_ID_L1") (pintype "bidirectional"))
      (node (ref "U2") (pin "3") (pinfunction "ID_3") (pintype "passive"))
      (node (ref "X1") (pin "ID") (pinfunction "ID_ID") (pintype "input"))
    )
    (net (code "150") (name "/USB0_N") (class "Default")
      (node (ref "U1") (pin "K2") (pinfunction "USB0_DM_K2") (pintype "bidirectional"))
      (node (ref "U2") (pin "1") (pinfunction "D-_1") (pintype "passive"))
      (node (ref "X1") (pin "D-") (pinfunction "D-_D-") (pintype "input"))
    )
    (net (code "151") (name "/USB0_P") (class "Default")
      (node (ref "U1") (pin "L2") (pinfunction "USB0_DP_L2") (pintype "bidirectional"))
      (node (ref "U2") (pin "2") (pinfunction "D+_2") (pintype "passive"))
      (node (ref "X1") (pin "D+") (pinfunction "D+_D+") (pintype "input"))
    )
    (net (code "152") (name "/USR0") (class "Default")
      (node (ref "D7") (pin "1") (pinfunction "A_1") (pintype "passive"))
      (node (ref "U1") (pin "C12") (pinfunction "GPMC_A5_C12") (pintype "bidirectional"))
    )
    (net (code "153") (name "/USR1") (class "Default")
      (node (ref "D6") (pin "1") (pinfunction "A_1") (pintype "passive"))
      (node (ref "U1") (pin "A11") (pinfunction "GPMC_A6_A11") (pintype "bidirectional"))
    )
    (net (code "154") (name "/USR2") (class "Default")
      (node (ref "D5") (pin "1") (pinfunction "A_1") (pintype "passive"))
      (node (ref "U1") (pin "B11") (pinfunction "GPMC_A7_B11") (pintype "bidirectional"))
    )
    (net (code "155") (name "/USR3") (class "Default")
      (node (ref "D4") (pin "1") (pinfunction "A_1") (pintype "passive"))
      (node (ref "U1") (pin "C11") (pinfunction "GPMC_A8_C11") (pintype "bidirectional"))
    )
    (net (code "156") (name "/VDDS_DDR") (class "Default")
      (node (ref "TP2") (pin "TP") (pinfunction "TP_TP") (pintype "input"))
      (node (ref "U1") (pin "U9") (pinfunction "VDDS_DDR_U9") (pintype "bidirectional"))
    )
    (net (code "157") (name "/VDDS_PLL") (class "Default")
      (node (ref "TP3") (pin "TP") (pinfunction "TP_TP") (pintype "input"))
      (node (ref "U1") (pin "U10") (pinfunction "VDDS_PLL_U10") (pintype "bidirectional"))
    )
    (net (code "158") (name "/VDD_CORE") (class "Default")
      (node (ref "TP4") (pin "TP") (pinfunction "TP_TP") (pintype "input"))
      (node (ref "U1") (pin "U13") (pinfunction "VDD_CORE_U13") (pintype "bidirectional"))
    )
    (net (code "159") (name "/VDD_MPU") (class "Default")
      (node (ref "TP1") (pin "TP") (pinfunction "TP_TP") (pintype "input"))
      (node (ref "U1") (pin "U6") (pinfunction "VDD_MPU_U6") (pintype "bidirectional"))
    )
    (net (code "160") (name "/VIO") (class "Default")
      (node (ref "U28") (pin "5") (pinfunction "VIO_5") (pintype "power_in"))
    )
    (net (code "161") (name "/VREFN") (class "Default")
      (node (ref "R25") (pin "1") (pinfunction "1_1") (pintype "passive"))
      (node (ref "U1") (pin "W9") (pinfunction "VREFN_W9") (pintype "bidirectional"))
    )
    (net (code "162") (name "/VREFP") (class "Default")
      (node (ref "C8") (pin "1") (pinfunction "1_1") (pintype "passive"))
      (node (ref "C9") (pin "1") (pinfunction "1_1") (pintype "passive"))
      (node (ref "R33") (pin "1") (pinfunction "1_1") (pintype "passive"))
      (node (ref "U1") (pin "W12") (pinfunction "VREFP_W12") (pintype "bidirectional"))
    )
    (net (code "163") (name "/XDMA_EVENT_INTR0") (class "Default")
      (node (ref "C1") (pin "2") (pinfunction "2_2") (pintype "passive"))
      (node (ref "R4") (pin "2") (pinfunction "2_2") (pintype "passive"))
      (node (ref "X4") (pin "17") (pinfunction "EMU2_17") (pintype "bidirectional"))
    )
    (net (code "164") (name "24VDC_AUX") (class "Default")
      (node (ref "C106") (pin "1") (pinfunction "1_1") (pintype "passive"))
      (node (ref "D19") (pin "1") (pinfunction "A_1") (pintype "passive"))
      (node (ref "D31") (pin "1") (pinfunction "A_1") (pintype "passive"))
      (node (ref "D32") (pin "1") (pinfunction "A_1") (pintype "passive"))
      (node (ref "D33") (pin "1") (pinfunction "A_1") (pintype "passive"))
      (node (ref "D34") (pin "1") (pinfunction "A_1") (pintype "passive"))
      (node (ref "D35") (pin "1") (pinfunction "A_1") (pintype "passive"))
      (node (ref "IC2") (pin "9") (pinfunction "CD+_9") (pintype "passive"))
      (node (ref "J24") (pin "3") (pinfunction "3_3") (pintype "bidirectional"))
      (node (ref "K1") (pin "1") (pinfunction "1_1") (pintype "passive"))
      (node (ref "K2") (pin "1") (pinfunction "1_1") (pintype "passive"))
      (node (ref "K3") (pin "1") (pinfunction "1_1") (pintype "passive"))
      (node (ref "K4") (pin "1") (pinfunction "1_1") (pintype "passive"))
      (node (ref "K5") (pin "1") (pinfunction "1_1") (pintype "passive"))
      (node (ref "VREG2") (pin "OUT") (pinfunction "OUT_OUT") (pintype "passive"))
      (node (ref "X8") (pin "4") (pinfunction "SK_4") (pintype "passive"))
    )
    (net (code "165") (name "AGND") (class "Default")
      (node (ref "C10") (pin "2") (pinfunction "2_2") (pintype "passive"))
      (node (ref "C111") (pin "2") (pinfunction "2_2") (pintype "passive"))
      (node (ref "C121") (pin "2") (pinfunction "2_2") (pintype "passive"))
      (node (ref "C131") (pin "2") (pinfunction "2_2") (pintype "passive"))
      (node (ref "C141") (pin "2") (pinfunction "2_2") (pintype "passive"))
      (node (ref "C151") (pin "2") (pinfunction "2_2") (pintype "passive"))
      (node (ref "C161") (pin "2") (pinfunction "2_2") (pintype "passive"))
      (node (ref "C8") (pin "2") (pinfunction "2_2") (pintype "passive"))
      (node (ref "C9") (pin "2") (pinfunction "2_2") (pintype "passive"))
      (node (ref "IC10") (pin "4") (pinfunction "V-_4") (pintype "power_in"))
      (node (ref "IC11") (pin "4") (pinfunction "V-_4") (pintype "power_in"))
      (node (ref "IC12") (pin "4") (pinfunction "V-_4") (pintype "power_in"))
      (node (ref "IC14") (pin "4") (pinfunction "V-_4") (pintype "power_in"))
      (node (ref "R181") (pin "2") (pinfunction "2_2") (pintype "passive"))
      (node (ref "R182") (pin "2") (pinfunction "2_2") (pintype "passive"))
      (node (ref "R183") (pin "2") (pinfunction "2_2") (pintype "passive"))
      (node (ref "R184") (pin "2") (pinfunction "2_2") (pintype "passive"))
      (node (ref "R185") (pin "2") (pinfunction "2_2") (pintype "passive"))
      (node (ref "R186") (pin "2") (pinfunction "2_2") (pintype "passive"))
      (node (ref "R211") (pin "1") (pinfunction "1_1") (pintype "passive"))
      (node (ref "R213") (pin "2") (pinfunction "2_2") (pintype "passive"))
      (node (ref "R221") (pin "1") (pinfunction "1_1") (pintype "passive"))
      (node (ref "R223") (pin "2") (pinfunction "2_2") (pintype "passive"))
      (node (ref "R231") (pin "1") (pinfunction "1_1") (pintype "passive"))
      (node (ref "R233") (pin "2") (pinfunction "2_2") (pintype "passive"))
      (node (ref "R241") (pin "1") (pinfunction "1_1") (pintype "passive"))
      (node (ref "R243") (pin "2") (pinfunction "2_2") (pintype "passive"))
      (node (ref "R25") (pin "2") (pinfunction "2_2") (pintype "passive"))
      (node (ref "R251") (pin "1") (pinfunction "1_1") (pintype "passive"))
      (node (ref "R253") (pin "2") (pinfunction "2_2") (pintype "passive"))
      (node (ref "R261") (pin "1") (pinfunction "1_1") (pintype "passive"))
      (node (ref "R263") (pin "2") (pinfunction "2_2") (pintype "passive"))
      (node (ref "U1") (pin "Y9") (pinfunction "AGND_ADC_Y9") (pintype "bidirectional"))
      (node (ref "X10") (pin "2") (pinfunction "SK_2") (pintype "passive"))
      (node (ref "X10") (pin "4") (pinfunction "SK_4") (pintype "passive"))
      (node (ref "X11") (pin "2") (pinfunction "SK_2") (pintype "passive"))
      (node (ref "X11") (pin "4") (pinfunction "SK_4") (pintype "passive"))
      (node (ref "X12") (pin "2") (pinfunction "SK_2") (pintype "passive"))
      (node (ref "X12") (pin "4") (pinfunction "SK_4") (pintype "passive"))
    )
    (net (code "166") (name "CGND") (class "Default")
      (node (ref "MGT1") (pin "P$1") (pinfunction "P$1_P$1") (pintype "bidirectional"))
      (node (ref "MGT2") (pin "P$1") (pinfunction "P$1_P$1") (pintype "bidirectional"))
      (node (ref "MGT3") (pin "P$1") (pinfunction "P$1_P$1") (pintype "bidirectional"))
      (node (ref "MGT4") (pin "P$1") (pinfunction "P$1_P$1") (pintype "bidirectional"))
      (node (ref "R34") (pin "2") (pinfunction "2_2") (pintype "passive"))
      (node (ref "X1") (pin "CGND1") (pinfunction "SGND1_CGND1") (pintype "bidirectional"))
      (node (ref "X1") (pin "CGND2") (pinfunction "SGND2_CGND2") (pintype "bidirectional"))
      (node (ref "X1") (pin "CGND3") (pinfunction "SGND3_CGND3") (pintype "bidirectional"))
      (node (ref "X1") (pin "CGND4") (pinfunction "SGND4_CGND4") (pintype "bidirectional"))
      (node (ref "X1") (pin "CGND5") (pinfunction "SGND5_CGND5") (pintype "bidirectional"))
      (node (ref "X1") (pin "CGND6") (pinfunction "SGND6_CGND6") (pintype "bidirectional"))
      (node (ref "X2") (pin "S1") (pinfunction "SHD1_S1") (pintype "passive"))
      (node (ref "X2") (pin "S2") (pinfunction "SHD2_S2") (pintype "passive"))
      (node (ref "X5") (pin "10") (pinfunction "GND_2_10") (pintype "bidirectional"))
      (node (ref "X5") (pin "11") (pinfunction "GND_3_11") (pintype "bidirectional"))
      (node (ref "X5") (pin "13") (pinfunction "GND_4_13") (pintype "bidirectional"))
      (node (ref "X5") (pin "9") (pinfunction "GND_1_9") (pintype "bidirectional"))
    )
    (net (code "167") (name "GND") (class "Default")
      (node (ref "C1") (pin "1") (pinfunction "1_1") (pintype "passive"))
      (node (ref "C100") (pin "2") (pinfunction "2_2") (pintype "passive"))
      (node (ref "C101") (pin "2") (pinfunction "2_2") (pintype "passive"))
      (node (ref "C102") (pin "2") (pinfunction "2_2") (pintype "passive"))
      (node (ref "C104") (pin "2") (pinfunction "2_2") (pintype "passive"))
      (node (ref "C105") (pin "2") (pinfunction "2_2") (pintype "passive"))
      (node (ref "C106") (pin "2") (pinfunction "2_2") (pintype "passive"))
      (node (ref "C11") (pin "-") (pinfunction "-_-") (pintype "passive"))
      (node (ref "C14") (pin "2") (pinfunction "2_2") (pintype "passive"))
      (node (ref "C15") (pin "2") (pinfunction "2_2") (pintype "passive"))
      (node (ref "C2") (pin "1") (pinfunction "1_1") (pintype "passive"))
      (node (ref "C21") (pin "2") (pinfunction "2_2") (pintype "passive"))
      (node (ref "C22") (pin "2") (pinfunction "2_2") (pintype "passive"))
      (node (ref "C3") (pin "2") (pinfunction "2_2") (pintype "passive"))
      (node (ref "C301") (pin "2") (pinfunction "2_2") (pintype "passive"))
      (node (ref "C4") (pin "2") (pinfunction "2_2") (pintype "passive"))
      (node (ref "C401") (pin "2") (pinfunction "2_2") (pintype "passive"))
      (node (ref "C404") (pin "2") (pinfunction "2_2") (pintype "passive"))
      (node (ref "C6") (pin "1") (pinfunction "1_1") (pintype "passive"))
      (node (ref "C79") (pin "2") (pinfunction "2_2") (pintype "passive"))
      (node (ref "C801") (pin "2") (pinfunction "2_2") (pintype "passive"))
      (node (ref "C85") (pin "2") (pinfunction "2_2") (pintype "passive"))
      (node (ref "C87") (pin "2") (pinfunction "2_2") (pintype "passive"))
      (node (ref "C88") (pin "2") (pinfunction "2_2") (pintype "passive"))
      (node (ref "D18") (pin "A") (pinfunction "A_A") (pintype "passive"))
      (node (ref "D305") (pin "3") (pinfunction "3_3") (pintype "passive"))
      (node (ref "D805") (pin "3") (pinfunction "3_3") (pintype "passive"))
      (node (ref "EC30") (pin "2") (pinfunction "2_2") (pintype "passive"))
      (node (ref "EC31") (pin "2") (pinfunction "2_2") (pintype "passive"))
      (node (ref "EC32") (pin "2") (pinfunction "2_2") (pintype "passive"))
      (node (ref "EC33") (pin "2") (pinfunction "2_2") (pintype "passive"))
      (node (ref "EC34") (pin "2") (pinfunction "2_2") (pintype "passive"))
      (node (ref "EC35") (pin "2") (pinfunction "2_2") (pintype "passive"))
      (node (ref "EC36") (pin "2") (pinfunction "2_2") (pintype "passive"))
      (node (ref "EC37") (pin "2") (pinfunction "2_2") (pintype "passive"))
      (node (ref "EC38") (pin "2") (pinfunction "2_2") (pintype "passive"))
      (node (ref "EC39") (pin "2") (pinfunction "2_2") (pintype "passive"))
      (node (ref "EC40") (pin "2") (pinfunction "2_2") (pintype "passive"))
      (node (ref "EC41") (pin "2") (pinfunction "2_2") (pintype "passive"))
      (node (ref "EC42") (pin "2") (pinfunction "2_2") (pintype "passive"))
      (node (ref "ER101") (pin "2") (pinfunction "2_2") (pintype "passive"))
      (node (ref "ER102") (pin "2") (pinfunction "2_2") (pintype "passive"))
      (node (ref "ER103") (pin "2") (pinfunction "2_2") (pintype "passive"))
      (node (ref "ER104") (pin "2") (pinfunction "2_2") (pintype "passive"))
      (node (ref "ER115") (pin "1") (pinfunction "1_1") (pintype "passive"))
      (node (ref "ER117") (pin "1") (pinfunction "1_1") (pintype "passive"))
      (node (ref "ER120") (pin "1") (pinfunction "1_1") (pintype "passive"))
      (node (ref "ER128") (pin "1") (pinfunction "1_1") (pintype "passive"))
      (node (ref "ER129") (pin "2") (pinfunction "2_2") (pintype "passive"))
      (node (ref "G1") (pin "-") (pinfunction "-_-") (pintype "passive"))
      (node (ref "IC2") (pin "8") (pinfunction "GND_8") (pintype "power_in"))
      (node (ref "IC4") (pin "15") (pinfunction "INH_15") (pintype "input"))
      (node (ref "IC5") (pin "10") (pinfunction "SER_10") (pintype "input"))
      (node (ref "IC5") (pin "15") (pinfunction "INH_15") (pintype "input"))
      (node (ref "IC5") (pin "3") (pinfunction "E_3") (pintype "input"))
      (node (ref "IC5") (pin "4") (pinfunction "F_4") (pintype "input"))
      (node (ref "IC5") (pin "5") (pinfunction "G_5") (pintype "input"))
      (node (ref "IC5") (pin "6") (pinfunction "H_6") (pintype "input"))
      (node (ref "J1") (pin "2") (pinfunction "2_2") (pintype "bidirectional"))
      (node (ref "J2") (pin "2") (pinfunction "2_2") (pintype "bidirectional"))
      (node (ref "J3") (pin "2") (pinfunction "2_2") (pintype "bidirectional"))
      (node (ref "J4") (pin "2") (pinfunction "2_2") (pintype "bidirectional"))
      (node (ref "J5") (pin "2") (pinfunction "2_2") (pintype "bidirectional"))
      (node (ref "J6") (pin "2") (pinfunction "2_2") (pintype "bidirectional"))
      (node (ref "R168") (pin "2") (pinfunction "2_2") (pintype "passive"))
      (node (ref "R18") (pin "1") (pinfunction "1_1") (pintype "passive"))
      (node (ref "R26") (pin "2") (pinfunction "2_2") (pintype "passive"))
      (node (ref "R27") (pin "1") (pinfunction "1_1") (pintype "passive"))
      (node (ref "R281") (pin "1") (pinfunction "1_1") (pintype "bidirectional"))
      (node (ref "R281") (pin "2") (pinfunction "2_2") (pintype "bidirectional"))
      (node (ref "R281") (pin "3") (pinfunction "3_3") (pintype "bidirectional"))
      (node (ref "R281") (pin "4") (pinfunction "4_4") (pintype "bidirectional"))
      (node (ref "R282") (pin "1") (pinfunction "1_1") (pintype "bidirectional"))
      (node (ref "R282") (pin "2") (pinfunction "2_2") (pintype "bidirectional"))
      (node (ref "R282") (pin "3") (pinfunction "3_3") (pintype "bidirectional"))
      (node (ref "R282") (pin "4") (pinfunction "4_4") (pintype "bidirectional"))
      (node (ref "R291") (pin "1") (pinfunction "1_1") (pintype "bidirectional"))
      (node (ref "R291") (pin "2") (pinfunction "2_2") (pintype "bidirectional"))
      (node (ref "R291") (pin "3") (pinfunction "3_3") (pintype "bidirectional"))
      (node (ref "R291") (pin "4") (pinfunction "4_4") (pintype "bidirectional"))
      (node (ref "R301") (pin "2") (pinfunction "2_2") (pintype "passive"))
      (node (ref "R302") (pin "2") (pinfunction "2_2") (pintype "passive"))
      (node (ref "R304") (pin "1") (pinfunction "1_1") (pintype "passive"))
      (node (ref "R34") (pin "1") (pinfunction "1_1") (pintype "passive"))
      (node (ref "R35") (pin "1") (pinfunction "1_1") (pintype "bidirectional"))
      (node (ref "R35") (pin "2") (pinfunction "2_2") (pintype "bidirectional"))
      (node (ref "R35") (pin "3") (pinfunction "3_3") (pintype "bidirectional"))
      (node (ref "R35") (pin "4") (pinfunction "4_4") (pintype "bidirectional"))
      (node (ref "R39") (pin "1") (pinfunction "1_1") (pintype "passive"))
      (node (ref "R401") (pin "2") (pinfunction "2_2") (pintype "passive"))
      (node (ref "R402") (pin "2") (pinfunction "2_2") (pintype "passive"))
      (node (ref "R53") (pin "1") (pinfunction "1_1") (pintype "passive"))
      (node (ref "R54") (pin "1") (pinfunction "1_1") (pintype "passive"))
      (node (ref "R55") (pin "1") (pinfunction "1_1") (pintype "passive"))
      (node (ref "R56") (pin "1") (pinfunction "1_1") (pintype "passive"))
      (node (ref "R57") (pin "1") (pinfunction "1_1") (pintype "passive"))
      (node (ref "R58") (pin "1") (pinfunction "1_1") (pintype "passive"))
      (node (ref "R59") (pin "1") (pinfunction "1_1") (pintype "passive"))
      (node (ref "R6") (pin "1") (pinfunction "1_1") (pintype "passive"))
      (node (ref "R60") (pin "1") (pinfunction "1_1") (pintype "passive"))
      (node (ref "R61") (pin "1") (pinfunction "1_1") (pintype "passive"))
      (node (ref "R62") (pin "1") (pinfunction "1_1") (pintype "passive"))
      (node (ref "R63") (pin "1") (pinfunction "1_1") (pintype "passive"))
      (node (ref "R64") (pin "1") (pinfunction "1_1") (pintype "passive"))
      (node (ref "R65") (pin "1") (pinfunction "1_1") (pintype "passive"))
      (node (ref "R66") (pin "1") (pinfunction "1_1") (pintype "passive"))
      (node (ref "R67") (pin "1") (pinfunction "1_1") (pintype "passive"))
      (node (ref "R68") (pin "1") (pinfunction "1_1") (pintype "passive"))
      (node (ref "R801") (pin "2") (pinfunction "2_2") (pintype "passive"))
      (node (ref "R802") (pin "2") (pinfunction "2_2") (pintype "passive"))
      (node (ref "RTC1") (pin "5") (pinfunction "GND_5") (pintype "power_in"))
      (node (ref "S1") (pin "2") (pinfunction "2_2") (pintype "bidirectional"))
      (node (ref "S1") (pin "4") (pinfunction "4_4") (pintype "bidirectional"))
      (node (ref "S2") (pin "1") (pinfunction "1_1") (pintype "bidirectional"))
      (node (ref "S2") (pin "3") (pinfunction "3_3") (pintype "bidirectional"))
      (node (ref "TP8") (pin "P$1") (pinfunction "TP_P$1") (pintype "bidirectional"))
      (node (ref "U1") (pin "A1") (pinfunction "DGND_A1") (pintype "bidirectional"))
      (node (ref "U1") (pin "A20") (pinfunction "DGND_A20") (pintype "bidirectional"))
      (node (ref "U1") (pin "D15") (pinfunction "DGND_D15") (pintype "bidirectional"))
      (node (ref "U1") (pin "D16") (pinfunction "DGND_D16") (pintype "bidirectional"))
      (node (ref "U1") (pin "D17") (pinfunction "DGND_D17") (pintype "bidirectional"))
      (node (ref "U1") (pin "D4") (pinfunction "DGND_D4") (pintype "bidirectional"))
      (node (ref "U1") (pin "D5") (pinfunction "DGND_D5") (pintype "bidirectional"))
      (node (ref "U1") (pin "E10") (pinfunction "DGND_E10") (pintype "bidirectional"))
      (node (ref "U1") (pin "E11") (pinfunction "DGND_E11") (pintype "bidirectional"))
      (node (ref "U1") (pin "E12") (pinfunction "DGND_E12") (pintype "bidirectional"))
      (node (ref "U1") (pin "E13") (pinfunction "DGND_E13") (pintype "bidirectional"))
      (node (ref "U1") (pin "E14") (pinfunction "DGND_E14") (pintype "bidirectional"))
      (node (ref "U1") (pin "E15") (pinfunction "DGND_E15") (pintype "bidirectional"))
      (node (ref "U1") (pin "E16") (pinfunction "DGND_E16") (pintype "bidirectional"))
      (node (ref "U1") (pin "E17") (pinfunction "DGND_E17") (pintype "bidirectional"))
      (node (ref "U1") (pin "E4") (pinfunction "DGND_E4") (pintype "bidirectional"))
      (node (ref "U1") (pin "E5") (pinfunction "DGND_E5") (pintype "bidirectional"))
      (node (ref "U1") (pin "E6") (pinfunction "DGND_E6") (pintype "bidirectional"))
      (node (ref "U1") (pin "E7") (pinfunction "DGND_E7") (pintype "bidirectional"))
      (node (ref "U1") (pin "E8") (pinfunction "DGND_E8") (pintype "bidirectional"))
      (node (ref "U1") (pin "E9") (pinfunction "DGND_E9") (pintype "bidirectional"))
      (node (ref "U1") (pin "F10") (pinfunction "DGND_F10") (pintype "bidirectional"))
      (node (ref "U1") (pin "F11") (pinfunction "DGND_F11") (pintype "bidirectional"))
      (node (ref "U1") (pin "F16") (pinfunction "DGND_F16") (pintype "bidirectional"))
      (node (ref "U1") (pin "F17") (pinfunction "DGND_F17") (pintype "bidirectional"))
      (node (ref "U1") (pin "F5") (pinfunction "DGND_F5") (pintype "bidirectional"))
      (node (ref "U1") (pin "G16") (pinfunction "DGND_G16") (pintype "bidirectional"))
      (node (ref "U1") (pin "G5") (pinfunction "DGND_G5") (pintype "bidirectional"))
      (node (ref "U1") (pin "H16") (pinfunction "DGND_H16") (pintype "bidirectional"))
      (node (ref "U1") (pin "H5") (pinfunction "DGND_H5") (pintype "bidirectional"))
      (node (ref "U1") (pin "J10") (pinfunction "DGND_J10") (pintype "bidirectional"))
      (node (ref "U1") (pin "J11") (pinfunction "DGND_J11") (pintype "bidirectional"))
      (node (ref "U1") (pin "J12") (pinfunction "DGND_J12") (pintype "bidirectional"))
      (node (ref "U1") (pin "J13") (pinfunction "DGND_J13") (pintype "bidirectional"))
      (node (ref "U1") (pin "J16") (pinfunction "DGND_J16") (pintype "bidirectional"))
      (node (ref "U1") (pin "J5") (pinfunction "DGND_J5") (pintype "bidirectional"))
      (node (ref "U1") (pin "J9") (pinfunction "DGND_J9") (pintype "bidirectional"))
      (node (ref "U1") (pin "K12") (pinfunction "DGND_K12") (pintype "bidirectional"))
      (node (ref "U1") (pin "K15") (pinfunction "DGND_K15") (pintype "bidirectional"))
      (node (ref "U1") (pin "K16") (pinfunction "DGND_K16") (pintype "bidirectional"))
      (node (ref "U1") (pin "K5") (pinfunction "DGND_K5") (pintype "bidirectional"))
      (node (ref "U1") (pin "K6") (pinfunction "DGND_K6") (pintype "bidirectional"))
      (node (ref "U1") (pin "K7") (pinfunction "DGND_K7") (pintype "bidirectional"))
      (node (ref "U1") (pin "K8") (pinfunction "DGND_K8") (pintype "bidirectional"))
      (node (ref "U1") (pin "K9") (pinfunction "DGND_K9") (pintype "bidirectional"))
      (node (ref "U1") (pin "L15") (pinfunction "DGND_L15") (pintype "bidirectional"))
      (node (ref "U1") (pin "L16") (pinfunction "DGND_L16") (pintype "bidirectional"))
      (node (ref "U1") (pin "L5") (pinfunction "DGND_L5") (pintype "bidirectional"))
      (node (ref "U1") (pin "L6") (pinfunction "DGND_L6") (pintype "bidirectional"))
      (node (ref "U1") (pin "M15") (pinfunction "DGND_M15") (pintype "bidirectional"))
      (node (ref "U1") (pin "M16") (pinfunction "DGND_M16") (pintype "bidirectional"))
      (node (ref "U1") (pin "M5") (pinfunction "DGND_M5") (pintype "bidirectional"))
      (node (ref "U1") (pin "N15") (pinfunction "DGND_N15") (pintype "bidirectional"))
      (node (ref "U1") (pin "N16") (pinfunction "DGND_N16") (pintype "bidirectional"))
      (node (ref "U1") (pin "N5") (pinfunction "DGND_N5") (pintype "bidirectional"))
      (node (ref "U1") (pin "N6") (pinfunction "DGND_N6") (pintype "bidirectional"))
      (node (ref "U1") (pin "P12") (pinfunction "DGND_P12") (pintype "bidirectional"))
      (node (ref "U1") (pin "P13") (pinfunction "DGND_P13") (pintype "bidirectional"))
      (node (ref "U1") (pin "P14") (pinfunction "DGND_P14") (pintype "bidirectional"))
      (node (ref "U1") (pin "P15") (pinfunction "DGND_P15") (pintype "bidirectional"))
      (node (ref "U1") (pin "P16") (pinfunction "DGND_P16") (pintype "bidirectional"))
      (node (ref "U1") (pin "P5") (pinfunction "DGND_P5") (pintype "bidirectional"))
      (node (ref "U1") (pin "P6") (pinfunction "DGND_P6") (pintype "bidirectional"))
      (node (ref "U1") (pin "P7") (pinfunction "DGND_P7") (pintype "bidirectional"))
      (node (ref "U1") (pin "P8") (pinfunction "DGND_P8") (pintype "bidirectional"))
      (node (ref "U1") (pin "P9") (pinfunction "DGND_P9") (pintype "bidirectional"))
      (node (ref "U1") (pin "R10") (pinfunction "DGND_R10") (pintype "bidirectional"))
      (node (ref "U1") (pin "R11") (pinfunction "DGND_R11") (pintype "bidirectional"))
      (node (ref "U1") (pin "R12") (pinfunction "DGND_R12") (pintype "bidirectional"))
      (node (ref "U1") (pin "R16") (pinfunction "DGND_R16") (pintype "bidirectional"))
      (node (ref "U1") (pin "R5") (pinfunction "DGND_R5") (pintype "bidirectional"))
      (node (ref "U1") (pin "R9") (pinfunction "DGND_R9") (pintype "bidirectional"))
      (node (ref "U1") (pin "T10") (pinfunction "DGND_T10") (pintype "bidirectional"))
      (node (ref "U1") (pin "T11") (pinfunction "DGND_T11") (pintype "bidirectional"))
      (node (ref "U1") (pin "T12") (pinfunction "DGND_T12") (pintype "bidirectional"))
      (node (ref "U1") (pin "T13") (pinfunction "DGND_T13") (pintype "bidirectional"))
      (node (ref "U1") (pin "T14") (pinfunction "DGND_T14") (pintype "bidirectional"))
      (node (ref "U1") (pin "T15") (pinfunction "DGND_T15") (pintype "bidirectional"))
      (node (ref "U1") (pin "T16") (pinfunction "DGND_T16") (pintype "bidirectional"))
      (node (ref "U1") (pin "T17") (pinfunction "DGND_T17") (pintype "bidirectional"))
      (node (ref "U1") (pin "T4") (pinfunction "DGND_T4") (pintype "bidirectional"))
      (node (ref "U1") (pin "T5") (pinfunction "DGND_T5") (pintype "bidirectional"))
      (node (ref "U1") (pin "T6") (pinfunction "DGND_T6") (pintype "bidirectional"))
      (node (ref "U1") (pin "T7") (pinfunction "DGND_T7") (pintype "bidirectional"))
      (node (ref "U1") (pin "T8") (pinfunction "DGND_T8") (pintype "bidirectional"))
      (node (ref "U1") (pin "T9") (pinfunction "DGND_T9") (pintype "bidirectional"))
      (node (ref "U1") (pin "U15") (pinfunction "RTC_KALDO_ENN_U15") (pintype "bidirectional"))
      (node (ref "U1") (pin "U16") (pinfunction "DGND_U16") (pintype "bidirectional"))
      (node (ref "U1") (pin "U17") (pinfunction "DGND_U17") (pintype "bidirectional"))
      (node (ref "U1") (pin "U4") (pinfunction "DGND_U4") (pintype "bidirectional"))
      (node (ref "U1") (pin "U5") (pinfunction "DGND_U5") (pintype "bidirectional"))
      (node (ref "U1") (pin "W13") (pinfunction "OSC1_GND_W13") (pintype "bidirectional"))
      (node (ref "U1") (pin "Y1") (pinfunction "DGND_Y1") (pintype "bidirectional"))
      (node (ref "U1") (pin "Y20") (pinfunction "DGND_Y20") (pintype "bidirectional"))
      (node (ref "U16") (pin "18") (pinfunction "PIRQ#_18") (pintype "bidirectional"))
      (node (ref "U16") (pin "19") (pinfunction "ATEST_19") (pintype "bidirectional"))
      (node (ref "U16") (pin "2") (pinfunction "GND_2") (pintype "bidirectional"))
      (node (ref "U16") (pin "20") (pinfunction "TWI_WAKEUP#_20") (pintype "bidirectional"))
      (node (ref "U16") (pin "21") (pinfunction "ATEST_21") (pintype "bidirectional"))
      (node (ref "U16") (pin "23") (pinfunction "GND_23") (pintype "bidirectional"))
      (node (ref "U16") (pin "24") (pinfunction "ATEST_24") (pintype "bidirectional"))
      (node (ref "U16") (pin "32") (pinfunction "GND_32") (pintype "bidirectional"))
      (node (ref "U16") (pin "5") (pinfunction "TESTL_5") (pintype "bidirectional"))
      (node (ref "U16") (pin "6") (pinfunction "XTAMPER_6") (pintype "bidirectional"))
      (node (ref "U16") (pin "9") (pinfunction "GND_9") (pintype "bidirectional"))
      (node (ref "U2") (pin "4") (pinfunction "GND_4") (pintype "power_in"))
      (node (ref "U27") (pin "33") (pinfunction "GND_EP_33") (pintype "power_in"))
      (node (ref "U28") (pin "2") (pinfunction "GND_2") (pintype "power_in"))
      (node (ref "U29") (pin "5") (pinfunction "GND_5") (pintype "power_in"))
      (node (ref "U4") (pin "1") (pinfunction "GND_1") (pintype "bidirectional"))
      (node (ref "U40") (pin "3") (pinfunction "GND1_3") (pintype "power_in"))
      (node (ref "U6") (pin "1") (pinfunction "*1OE_1") (pintype "input"))
      (node (ref "U6") (pin "4") (pinfunction "GND_4") (pintype "power_in"))
      (node (ref "VREG1") (pin "3") (pinfunction "GND_3") (pintype "power_in"))
      (node (ref "VREG1") (pin "5") (pinfunction "EN_5") (pintype "input"))
      (node (ref "VREG1") (pin "6") (pinfunction "GND_6") (pintype "power_in"))
      (node (ref "VREG2") (pin "GND") (pinfunction "GND_GND") (pintype "input"))
      (node (ref "X1") (pin "GND") (pinfunction "GND_GND") (pintype "input"))
      (node (ref "X2") (pin "8") (pinfunction "D_GND_8") (pintype "passive"))
      (node (ref "X24") (pin "2") (pinfunction "1_2") (pintype "passive"))
      (node (ref "X3") (pin "1") (pinfunction "SK_1") (pintype "passive"))
      (node (ref "X4") (pin "10") (pinfunction "GND2_10") (pintype "bidirectional"))
      (node (ref "X4") (pin "12") (pinfunction "GND3_12") (pintype "bidirectional"))
      (node (ref "X4") (pin "16") (pinfunction "GND4_16") (pintype "bidirectional"))
      (node (ref "X4") (pin "20") (pinfunction "GND5_20") (pintype "bidirectional"))
      (node (ref "X4") (pin "4") (pinfunction "TDIS_4") (pintype "bidirectional"))
      (node (ref "X4") (pin "8") (pinfunction "GND1_8") (pintype "bidirectional"))
      (node (ref "X5") (pin "6") (pinfunction "VSS_6") (pintype "bidirectional"))
      (node (ref "X6") (pin "1") (pinfunction "1_1") (pintype "bidirectional"))
      (node (ref "X8") (pin "3") (pinfunction "SK_3") (pintype "passive"))
    )
    (net (code "168") (name "ISO_GND") (class "Default")
      (node (ref "C402") (pin "2") (pinfunction "2_2") (pintype "passive"))
      (node (ref "C403") (pin "2") (pinfunction "2_2") (pintype "passive"))
      (node (ref "C405") (pin "2") (pinfunction "2_2") (pintype "passive"))
      (node (ref "C406") (pin "-") (pinfunction "-_-") (pintype "passive"))
      (node (ref "D405") (pin "3") (pinfunction "3_3") (pintype "passive"))
      (node (ref "GDT1") (pin "3") (pinfunction "3_3") (pintype "passive"))
      (node (ref "T4") (pin "P$6") (pinfunction "6_P$6") (pintype "passive"))
      (node (ref "T4") (pin "P$7") (pinfunction "7_P$7") (pintype "passive"))
      (node (ref "U40") (pin "15") (pinfunction "GND2_15") (pintype "power_in"))
      (node (ref "U40") (pin "9") (pinfunction "GND2_2_9") (pintype "power_in"))
      (node (ref "VREG4") (pin "2") (pinfunction "GND_2") (pintype "power_in"))
      (node (ref "X41") (pin "3") (pinfunction "1_3") (pintype "passive"))
    )
    (net (code "169") (name "Net-(C105-Pad1)") (class "Default")
      (node (ref "C105") (pin "1") (pinfunction "1_1") (pintype "passive"))
      (node (ref "J24") (pin "1") (pinfunction "1_1") (pintype "bidirectional"))
      (node (ref "VREG2") (pin "IN") (pinfunction "IN_IN") (pintype "input"))
    )
    (net (code "170") (name "Net-(D1-C)") (class "Default")
      (node (ref "D1") (pin "2") (pinfunction "C_2") (pintype "passive"))
      (node (ref "R26") (pin "1") (pinfunction "1_1") (pintype "passive"))
    )
    (net (code "171") (name "Net-(D4-C)") (class "Default")
      (node (ref "D4") (pin "2") (pinfunction "C_2") (pintype "passive"))
      (node (ref "R35") (pin "5") (pinfunction "5_5") (pintype "bidirectional"))
    )
    (net (code "172") (name "Net-(D5-C)") (class "Default")
      (node (ref "D5") (pin "2") (pinfunction "C_2") (pintype "passive"))
      (node (ref "R35") (pin "6") (pinfunction "6_6") (pintype "bidirectional"))
    )
    (net (code "173") (name "Net-(D6-C)") (class "Default")
      (node (ref "D6") (pin "2") (pinfunction "C_2") (pintype "passive"))
      (node (ref "R35") (pin "7") (pinfunction "7_7") (pintype "bidirectional"))
    )
    (net (code "174") (name "Net-(D7-C)") (class "Default")
      (node (ref "D7") (pin "2") (pinfunction "C_2") (pintype "passive"))
      (node (ref "R35") (pin "8") (pinfunction "8_8") (pintype "bidirectional"))
    )
    (net (code "175") (name "Net-(D19-C)") (class "Default")
      (node (ref "D19") (pin "2") (pinfunction "C_2") (pintype "passive"))
      (node (ref "R168") (pin "1") (pinfunction "1_1") (pintype "passive"))
    )
    (net (code "176") (name "Net-(D31-C)") (class "Default")
      (node (ref "D31") (pin "2") (pinfunction "C_2") (pintype "passive"))
      (node (ref "R171") (pin "1") (pinfunction "1_1") (pintype "passive"))
    )
    (net (code "177") (name "Net-(D32-C)") (class "Default")
      (node (ref "D32") (pin "2") (pinfunction "C_2") (pintype "passive"))
      (node (ref "R172") (pin "1") (pinfunction "1_1") (pintype "passive"))
    )
    (net (code "178") (name "Net-(D33-C)") (class "Default")
      (node (ref "D33") (pin "2") (pinfunction "C_2") (pintype "passive"))
      (node (ref "R173") (pin "1") (pinfunction "1_1") (pintype "passive"))
    )
    (net (code "179") (name "Net-(D34-C)") (class "Default")
      (node (ref "D34") (pin "2") (pinfunction "C_2") (pintype "passive"))
      (node (ref "R174") (pin "1") (pinfunction "1_1") (pintype "passive"))
    )
    (net (code "180") (name "Net-(D35-C)") (class "Default")
      (node (ref "D35") (pin "2") (pinfunction "C_2") (pintype "passive"))
      (node (ref "R175") (pin "1") (pinfunction "1_1") (pintype "passive"))
    )
    (net (code "181") (name "Net-(D301-C)") (class "Default")
      (node (ref "D301") (pin "2") (pinfunction "C_2") (pintype "passive"))
      (node (ref "R301") (pin "1") (pinfunction "1_1") (pintype "passive"))
    )
    (net (code "182") (name "Net-(D302-C)") (class "Default")
      (node (ref "D302") (pin "2") (pinfunction "C_2") (pintype "passive"))
      (node (ref "R302") (pin "1") (pinfunction "1_1") (pintype "passive"))
    )
    (net (code "183") (name "Net-(D401-C)") (class "Default")
      (node (ref "D401") (pin "2") (pinfunction "C_2") (pintype "passive"))
      (node (ref "R401") (pin "1") (pinfunction "1_1") (pintype "passive"))
    )
    (net (code "184") (name "Net-(D402-C)") (class "Default")
      (node (ref "D402") (pin "2") (pinfunction "C_2") (pintype "passive"))
      (node (ref "R402") (pin "1") (pinfunction "1_1") (pintype "passive"))
    )
    (net (code "185") (name "Net-(D801-C)") (class "Default")
      (node (ref "D801") (pin "2") (pinfunction "C_2") (pintype "passive"))
      (node (ref "R801") (pin "1") (pinfunction "1_1") (pintype "passive"))
    )
    (net (code "186") (name "Net-(D802-C)") (class "Default")
      (node (ref "D802") (pin "2") (pinfunction "C_2") (pintype "passive"))
      (node (ref "R802") (pin "1") (pinfunction "1_1") (pintype "passive"))
    )
    (net (code "187") (name "Net-(F1-1)") (class "Default")
      (node (ref "F1") (pin "P$1") (pinfunction "1_P$1") (pintype "bidirectional"))
      (node (ref "X24") (pin "1") (pinfunction "1_1") (pintype "passive"))
      (node (ref "X3") (pin "4") (pinfunction "SK_4") (pintype "passive"))
    )
    (net (code "188") (name "Net-(F1-2)") (class "Default")
      (node (ref "D3") (pin "A") (pinfunction "A_A") (pintype "passive"))
      (node (ref "F1") (pin "P$2") (pinfunction "2_P$2") (pintype "bidirectional"))
    )
    (net (code "189") (name "Net-(F401-Pad1)") (class "Default")
      (node (ref "F401") (pin "1") (pinfunction "1_1") (pintype "passive"))
      (node (ref "GDT1") (pin "2") (pinfunction "2_2") (pintype "passive"))
      (node (ref "X41") (pin "1") (pinfunction "1_1") (pintype "passive"))
    )
    (net (code "190") (name "Net-(IC2-O1)") (class "Default")
      (node (ref "IC2") (pin "16") (pinfunction "O1_16") (pintype "open_collector"))
      (node (ref "K1") (pin "2") (pinfunction "2_2") (pintype "passive"))
      (node (ref "R171") (pin "2") (pinfunction "2_2") (pintype "passive"))
    )
    (net (code "191") (name "Net-(IC2-O2)") (class "Default")
      (node (ref "IC2") (pin "15") (pinfunction "O2_15") (pintype "open_collector"))
      (node (ref "K2") (pin "2") (pinfunction "2_2") (pintype "passive"))
      (node (ref "R172") (pin "2") (pinfunction "2_2") (pintype "passive"))
    )
    (net (code "192") (name "Net-(IC2-O3)") (class "Default")
      (node (ref "IC2") (pin "14") (pinfunction "O3_14") (pintype "open_collector"))
      (node (ref "K3") (pin "2") (pinfunction "2_2") (pintype "passive"))
      (node (ref "R173") (pin "2") (pinfunction "2_2") (pintype "passive"))
    )
    (net (code "193") (name "Net-(IC2-O4)") (class "Default")
      (node (ref "IC2") (pin "13") (pinfunction "O4_13") (pintype "open_collector"))
      (node (ref "K4") (pin "2") (pinfunction "2_2") (pintype "passive"))
      (node (ref "R174") (pin "2") (pinfunction "2_2") (pintype "passive"))
    )
    (net (code "194") (name "Net-(IC2-O5)") (class "Default")
      (node (ref "IC2") (pin "12") (pinfunction "O5_12") (pintype "open_collector"))
      (node (ref "K5") (pin "2") (pinfunction "2_2") (pintype "passive"))
      (node (ref "R175") (pin "2") (pinfunction "2_2") (pintype "passive"))
    )
    (net (code "195") (name "Net-(IC4A-A)") (class "Default")
      (node (ref "IC4") (pin "11") (pinfunction "A_11") (pintype "input"))
      (node (ref "R281") (pin "8") (pinfunction "8_8") (pintype "bidirectional"))
      (node (ref "S11") (pin "1") (pinfunction "1_1") (pintype "passive"))
    )
    (net (code "196") (name "Net-(IC4A-B)") (class "Default")
      (node (ref "IC4") (pin "12") (pinfunction "B_12") (pintype "input"))
      (node (ref "R281") (pin "7") (pinfunction "7_7") (pintype "bidirectional"))
      (node (ref "S11") (pin "2") (pinfunction "2_2") (pintype "passive"))
    )
    (net (code "197") (name "Net-(IC4A-C)") (class "Default")
      (node (ref "IC4") (pin "13") (pinfunction "C_13") (pintype "input"))
      (node (ref "R281") (pin "6") (pinfunction "6_6") (pintype "bidirectional"))
      (node (ref "S11") (pin "4") (pinfunction "4_4") (pintype "passive"))
    )
    (net (code "198") (name "Net-(IC4A-D)") (class "Default")
      (node (ref "IC4") (pin "14") (pinfunction "D_14") (pintype "input"))
      (node (ref "R281") (pin "5") (pinfunction "5_5") (pintype "bidirectional"))
      (node (ref "S11") (pin "8") (pinfunction "8_8") (pintype "passive"))
    )
    (net (code "199") (name "Net-(IC4A-E)") (class "Default")
      (node (ref "IC4") (pin "3") (pinfunction "E_3") (pintype "input"))
      (node (ref "R282") (pin "8") (pinfunction "8_8") (pintype "bidirectional"))
      (node (ref "S12") (pin "1") (pinfunction "1_1") (pintype "passive"))
    )
    (net (code "200") (name "Net-(IC4A-F)") (class "Default")
      (node (ref "IC4") (pin "4") (pinfunction "F_4") (pintype "input"))
      (node (ref "R282") (pin "7") (pinfunction "7_7") (pintype "bidirectional"))
      (node (ref "S12") (pin "2") (pinfunction "2_2") (pintype "passive"))
    )
    (net (code "201") (name "Net-(IC4A-G)") (class "Default")
      (node (ref "IC4") (pin "5") (pinfunction "G_5") (pintype "input"))
      (node (ref "R282") (pin "6") (pinfunction "6_6") (pintype "bidirectional"))
      (node (ref "S12") (pin "4") (pinfunction "4_4") (pintype "passive"))
    )
    (net (code "202") (name "Net-(IC4A-H)") (class "Default")
      (node (ref "IC4") (pin "6") (pinfunction "H_6") (pintype "input"))
      (node (ref "R282") (pin "5") (pinfunction "5_5") (pintype "bidirectional"))
      (node (ref "S12") (pin "8") (pinfunction "8_8") (pintype "passive"))
    )
    (net (code "203") (name "Net-(IC4A-SER)") (class "Default")
      (node (ref "IC4") (pin "10") (pinfunction "SER_10") (pintype "input"))
      (node (ref "IC5") (pin "9") (pinfunction "QH_9") (pintype "output"))
    )
    (net (code "204") (name "Net-(IC5A-A)") (class "Default")
      (node (ref "IC5") (pin "11") (pinfunction "A_11") (pintype "input"))
      (node (ref "R291") (pin "8") (pinfunction "8_8") (pintype "bidirectional"))
      (node (ref "S13") (pin "8") (pinfunction "8_8") (pintype "passive"))
    )
    (net (code "205") (name "Net-(IC5A-B)") (class "Default")
      (node (ref "IC5") (pin "12") (pinfunction "B_12") (pintype "input"))
      (node (ref "R291") (pin "7") (pinfunction "7_7") (pintype "bidirectional"))
      (node (ref "S13") (pin "7") (pinfunction "7_7") (pintype "passive"))
    )
    (net (code "206") (name "Net-(IC5A-C)") (class "Default")
      (node (ref "IC5") (pin "13") (pinfunction "C_13") (pintype "input"))
      (node (ref "R291") (pin "6") (pinfunction "6_6") (pintype "bidirectional"))
      (node (ref "S13") (pin "6") (pinfunction "6_6") (pintype "passive"))
    )
    (net (code "207") (name "Net-(IC5A-D)") (class "Default")
      (node (ref "IC5") (pin "14") (pinfunction "D_14") (pintype "input"))
      (node (ref "R291") (pin "5") (pinfunction "5_5") (pintype "bidirectional"))
      (node (ref "S13") (pin "5") (pinfunction "5_5") (pintype "passive"))
    )
    (net (code "208") (name "Net-(IC10A-+IN)") (class "Default")
      (node (ref "C111") (pin "1") (pinfunction "1_1") (pintype "passive"))
      (node (ref "IC10") (pin "3") (pinfunction "+IN_3") (pintype "input"))
      (node (ref "J13") (pin "1") (pinfunction "1_1") (pintype "bidirectional"))
      (node (ref "R214") (pin "2") (pinfunction "2_2") (pintype "passive"))
    )
    (net (code "209") (name "Net-(IC10B-+IN)") (class "Default")
      (node (ref "C121") (pin "1") (pinfunction "1_1") (pintype "passive"))
      (node (ref "IC10") (pin "5") (pinfunction "+IN_5") (pintype "input"))
      (node (ref "J23") (pin "1") (pinfunction "1_1") (pintype "bidirectional"))
      (node (ref "R224") (pin "2") (pinfunction "2_2") (pintype "passive"))
    )
    (net (code "210") (name "Net-(IC11A-+IN)") (class "Default")
      (node (ref "C131") (pin "1") (pinfunction "1_1") (pintype "passive"))
      (node (ref "IC11") (pin "3") (pinfunction "+IN_3") (pintype "input"))
      (node (ref "J33") (pin "1") (pinfunction "1_1") (pintype "bidirectional"))
      (node (ref "R234") (pin "2") (pinfunction "2_2") (pintype "passive"))
    )
    (net (code "211") (name "Net-(IC11B-+IN)") (class "Default")
      (node (ref "C141") (pin "1") (pinfunction "1_1") (pintype "passive"))
      (node (ref "IC11") (pin "5") (pinfunction "+IN_5") (pintype "input"))
      (node (ref "J43") (pin "1") (pinfunction "1_1") (pintype "bidirectional"))
      (node (ref "R244") (pin "2") (pinfunction "2_2") (pintype "passive"))
    )
    (net (code "212") (name "Net-(IC12A-+IN)") (class "Default")
      (node (ref "C151") (pin "1") (pinfunction "1_1") (pintype "passive"))
      (node (ref "IC12") (pin "3") (pinfunction "+IN_3") (pintype "input"))
      (node (ref "J53") (pin "1") (pinfunction "1_1") (pintype "bidirectional"))
      (node (ref "R254") (pin "2") (pinfunction "2_2") (pintype "passive"))
    )
    (net (code "213") (name "Net-(IC12B-+IN)") (class "Default")
      (node (ref "C161") (pin "1") (pinfunction "1_1") (pintype "passive"))
      (node (ref "IC12") (pin "5") (pinfunction "+IN_5") (pintype "input"))
      (node (ref "J63") (pin "1") (pinfunction "1_1") (pintype "bidirectional"))
      (node (ref "R264") (pin "2") (pinfunction "2_2") (pintype "passive"))
    )
    (net (code "214") (name "Net-(J3-Pad1)") (class "Default")
      (node (ref "J3") (pin "1") (pinfunction "1_1") (pintype "bidirectional"))
      (node (ref "R69") (pin "2") (pinfunction "2_2") (pintype "passive"))
    )
    (net (code "215") (name "Net-(J11-Pad2)") (class "Default")
      (node (ref "J11") (pin "2") (pinfunction "2_2") (pintype "bidirectional"))
      (node (ref "R211") (pin "2") (pinfunction "2_2") (pintype "passive"))
    )
    (net (code "216") (name "Net-(J12-Pad2)") (class "Default")
      (node (ref "J12") (pin "2") (pinfunction "2_2") (pintype "bidirectional"))
      (node (ref "R212") (pin "1") (pinfunction "1_1") (pintype "passive"))
    )
    (net (code "217") (name "Net-(J13-Pad2)") (class "Default")
      (node (ref "J13") (pin "2") (pinfunction "2_2") (pintype "bidirectional"))
      (node (ref "R213") (pin "1") (pinfunction "1_1") (pintype "passive"))
    )
    (net (code "218") (name "Net-(J21-Pad2)") (class "Default")
      (node (ref "J21") (pin "2") (pinfunction "2_2") (pintype "bidirectional"))
      (node (ref "R221") (pin "2") (pinfunction "2_2") (pintype "passive"))
    )
    (net (code "219") (name "Net-(J22-Pad2)") (class "Default")
      (node (ref "J22") (pin "2") (pinfunction "2_2") (pintype "bidirectional"))
      (node (ref "R222") (pin "1") (pinfunction "1_1") (pintype "passive"))
    )
    (net (code "220") (name "Net-(J23-Pad2)") (class "Default")
      (node (ref "J23") (pin "2") (pinfunction "2_2") (pintype "bidirectional"))
      (node (ref "R223") (pin "1") (pinfunction "1_1") (pintype "passive"))
    )
    (net (code "221") (name "Net-(J31-Pad2)") (class "Default")
      (node (ref "J31") (pin "2") (pinfunction "2_2") (pintype "bidirectional"))
      (node (ref "R231") (pin "2") (pinfunction "2_2") (pintype "passive"))
    )
    (net (code "222") (name "Net-(J32-Pad2)") (class "Default")
      (node (ref "J32") (pin "2") (pinfunction "2_2") (pintype "bidirectional"))
      (node (ref "R232") (pin "1") (pinfunction "1_1") (pintype "passive"))
    )
    (net (code "223") (name "Net-(J33-Pad2)") (class "Default")
      (node (ref "J33") (pin "2") (pinfunction "2_2") (pintype "bidirectional"))
      (node (ref "R233") (pin "1") (pinfunction "1_1") (pintype "passive"))
    )
    (net (code "224") (name "Net-(J41-Pad2)") (class "Default")
      (node (ref "J41") (pin "2") (pinfunction "2_2") (pintype "bidirectional"))
      (node (ref "R241") (pin "2") (pinfunction "2_2") (pintype "passive"))
    )
    (net (code "225") (name "Net-(J42-Pad2)") (class "Default")
      (node (ref "J42") (pin "2") (pinfunction "2_2") (pintype "bidirectional"))
      (node (ref "R242") (pin "1") (pinfunction "1_1") (pintype "passive"))
    )
    (net (code "226") (name "Net-(J43-Pad2)") (class "Default")
      (node (ref "J43") (pin "2") (pinfunction "2_2") (pintype "bidirectional"))
      (node (ref "R243") (pin "1") (pinfunction "1_1") (pintype "passive"))
    )
    (net (code "227") (name "Net-(J51-Pad2)") (class "Default")
      (node (ref "J51") (pin "2") (pinfunction "2_2") (pintype "bidirectional"))
      (node (ref "R251") (pin "2") (pinfunction "2_2") (pintype "passive"))
    )
    (net (code "228") (name "Net-(J52-Pad2)") (class "Default")
      (node (ref "J52") (pin "2") (pinfunction "2_2") (pintype "bidirectional"))
      (node (ref "R252") (pin "1") (pinfunction "1_1") (pintype "passive"))
    )
    (net (code "229") (name "Net-(J53-Pad2)") (class "Default")
      (node (ref "J53") (pin "2") (pinfunction "2_2") (pintype "bidirectional"))
      (node (ref "R253") (pin "1") (pinfunction "1_1") (pintype "passive"))
    )
    (net (code "230") (name "Net-(J61-Pad2)") (class "Default")
      (node (ref "J61") (pin "2") (pinfunction "2_2") (pintype "bidirectional"))
      (node (ref "R261") (pin "2") (pinfunction "2_2") (pintype "passive"))
    )
    (net (code "231") (name "Net-(J62-Pad2)") (class "Default")
      (node (ref "J62") (pin "2") (pinfunction "2_2") (pintype "bidirectional"))
      (node (ref "R262") (pin "1") (pinfunction "1_1") (pintype "passive"))
    )
    (net (code "232") (name "Net-(J63-Pad2)") (class "Default")
      (node (ref "J63") (pin "2") (pinfunction "2_2") (pintype "bidirectional"))
      (node (ref "R263") (pin "1") (pinfunction "1_1") (pintype "passive"))
    )
    (net (code "233") (name "Net-(K5B-P)") (class "Default")
      (node (ref "K5") (pin "C") (pinfunction "P_C") (pintype "passive"))
      (node (ref "X21") (pin "1") (pinfunction "SK_1") (pintype "passive"))
    )
    (net (code "234") (name "Net-(K5B-S)") (class "Default")
      (node (ref "K5") (pin "NO") (pinfunction "S_NO") (pintype "passive"))
      (node (ref "X21") (pin "2") (pinfunction "SK_2") (pintype "passive"))
    )
    (net (code "235") (name "Net-(R10-Pad1)") (class "Default")
      (node (ref "R10") (pin "1") (pinfunction "1_1") (pintype "passive"))
      (node (ref "X1") (pin "VBUS") (pinfunction "VBUS_VBUS") (pintype "input"))
    )
    (net (code "236") (name "Net-(R11-Pad1)") (class "Default")
      (node (ref "R11") (pin "1") (pinfunction "1_1") (pintype "passive"))
      (node (ref "S1") (pin "1") (pinfunction "1_1") (pintype "bidirectional"))
      (node (ref "S1") (pin "3") (pinfunction "3_3") (pintype "bidirectional"))
    )
    (net (code "237") (name "Net-(RTC1-VBAT)") (class "Default")
      (node (ref "G1") (pin "+") (pinfunction "+_+") (pintype "passive"))
      (node (ref "RTC1") (pin "6") (pinfunction "VBAT_6") (pintype "power_in"))
    )
    (net (code "238") (name "Net-(T4-1)") (class "Default")
      (node (ref "T4") (pin "P$1") (pinfunction "1_P$1") (pintype "passive"))
      (node (ref "U40") (pin "1") (pinfunction "D1_1") (pintype "passive"))
    )
    (net (code "239") (name "Net-(T4-4)") (class "Default")
      (node (ref "T4") (pin "P$4") (pinfunction "4_P$4") (pintype "passive"))
      (node (ref "U40") (pin "2") (pinfunction "D2_2") (pintype "passive"))
    )
    (net (code "240") (name "Net-(T4-5)") (class "Default")
      (node (ref "D404") (pin "A") (pinfunction "A_A") (pintype "passive"))
      (node (ref "T4") (pin "P$5") (pinfunction "5_P$5") (pintype "passive"))
    )
    (net (code "241") (name "Net-(T4-8)") (class "Default")
      (node (ref "D403") (pin "A") (pinfunction "A_A") (pintype "passive"))
      (node (ref "T4") (pin "P$8") (pinfunction "8_P$8") (pintype "passive"))
    )
    (net (code "242") (name "Net-(U1A-EEPROM_WP)") (class "Default")
      (node (ref "J1") (pin "1") (pinfunction "1_1") (pintype "bidirectional"))
      (node (ref "U1") (pin "M2") (pinfunction "EEPROM_WP_M2") (pintype "bidirectional"))
    )
    (net (code "243") (name "Net-(U1A-PWRONRSTN_OD)") (class "Default")
      (node (ref "R5") (pin "1") (pinfunction "1_1") (pintype "passive"))
      (node (ref "U1") (pin "C17") (pinfunction "PWRONRSTN_OD_C17") (pintype "bidirectional"))
    )
    (net (code "244") (name "Net-(U1A-SYS_VDD1_CTL)") (class "Default")
      (node (ref "TP33") (pin "TP") (pinfunction "TP_TP") (pintype "input"))
      (node (ref "U1") (pin "F18") (pinfunction "SYS_VDD1_CTL_F18") (pintype "bidirectional"))
    )
    (net (code "245") (name "Net-(U1C-XDMA_EVENT_INTR0)") (class "Default")
      (node (ref "R4") (pin "1") (pinfunction "1_1") (pintype "passive"))
      (node (ref "U1") (pin "W14") (pinfunction "XDMA_EVENT_INTR0_W14") (pintype "bidirectional"))
    )
    (net (code "246") (name "Net-(U1C-XDMA_EVENT_INTR1)") (class "Default")
      (node (ref "R3") (pin "1") (pinfunction "1_1") (pintype "passive"))
      (node (ref "U1") (pin "V14") (pinfunction "XDMA_EVENT_INTR1_V14") (pintype "bidirectional"))
    )
    (net (code "247") (name "Net-(U1D-LCD_AC_BIAS_EN)") (class "Default")
      (node (ref "R28") (pin "1") (pinfunction "1_1") (pintype "passive"))
      (node (ref "U1") (pin "V20") (pinfunction "LCD_AC_BIAS_EN_V20") (pintype "bidirectional"))
    )
    (net (code "248") (name "Net-(U1D-LCD_HSYNC)") (class "Default")
      (node (ref "R29") (pin "1") (pinfunction "1_1") (pintype "passive"))
      (node (ref "U1") (pin "U19") (pinfunction "LCD_HSYNC_U19") (pintype "bidirectional"))
    )
    (net (code "249") (name "Net-(U1D-LCD_PCLK)") (class "Default")
      (node (ref "R31") (pin "1") (pinfunction "1_1") (pintype "passive"))
      (node (ref "U1") (pin "U20") (pinfunction "LCD_PCLK_U20") (pintype "bidirectional"))
    )
    (net (code "250") (name "Net-(U1D-LCD_VSYNC)") (class "Default")
      (node (ref "R30") (pin "1") (pinfunction "1_1") (pintype "passive"))
      (node (ref "U1") (pin "U18") (pinfunction "LCD_VSYNC_U18") (pintype "bidirectional"))
    )
    (net (code "251") (name "Net-(U4-MR#)") (class "Default")
      (node (ref "R11") (pin "2") (pinfunction "2_2") (pintype "passive"))
      (node (ref "R5") (pin "2") (pinfunction "2_2") (pintype "passive"))
      (node (ref "U4") (pin "3") (pinfunction "MR#_3") (pintype "bidirectional"))
    )
    (net (code "252") (name "Net-(U4-RESET#)") (class "Default")
      (node (ref "R8") (pin "2") (pinfunction "2_2") (pintype "passive"))
      (node (ref "U4") (pin "2") (pinfunction "RESET#_2") (pintype "bidirectional"))
    )
    (net (code "253") (name "Net-(U5-CATHODE)") (class "Default")
      (node (ref "Q1") (pin "B") (pinfunction "B_B") (pintype "passive"))
      (node (ref "R21") (pin "1") (pinfunction "1_1") (pintype "passive"))
      (node (ref "U5") (pin "2") (pinfunction "CATHODE_2") (pintype "bidirectional"))
    )
    (net (code "254") (name "Net-(U5-REF)") (class "Default")
      (node (ref "R15") (pin "2") (pinfunction "2_2") (pintype "passive"))
      (node (ref "R20") (pin "1") (pinfunction "1_1") (pintype "passive"))
      (node (ref "U5") (pin "1") (pinfunction "REF_1") (pintype "bidirectional"))
    )
    (net (code "255") (name "Net-(U27-NINT{slash}TXER{slash}TXD4)") (class "Default")
      (node (ref "ER129") (pin "1") (pinfunction "1_1") (pintype "passive"))
      (node (ref "U27") (pin "18") (pinfunction "NINT/TXER/TXD4_18") (pintype "bidirectional"))
    )
    (net (code "256") (name "Net-(U27-RBIAS)") (class "Default")
      (node (ref "ER128") (pin "2") (pinfunction "2_2") (pintype "passive"))
      (node (ref "U27") (pin "32") (pinfunction "RBIAS_32") (pintype "passive"))
    )
    (net (code "257") (name "Net-(U27-VDDCR)") (class "Default")
      (node (ref "EC33") (pin "1") (pinfunction "1_1") (pintype "passive"))
      (node (ref "EC35") (pin "1") (pinfunction "1_1") (pintype "passive"))
      (node (ref "U27") (pin "6") (pinfunction "VDDCR_6") (pintype "power_in"))
    )
    (net (code "258") (name "Net-(U27-XTAL1{slash}CLKIN)") (class "Default")
      (node (ref "ER126") (pin "1") (pinfunction "1_1") (pintype "passive"))
      (node (ref "U27") (pin "5") (pinfunction "XTAL1/CLKIN_5") (pintype "input"))
    )
    (net (code "259") (name "Net-(U27-XTAL2)") (class "Default")
      (node (ref "ER125") (pin "1") (pinfunction "1_1") (pintype "passive"))
      (node (ref "ER127") (pin "1") (pinfunction "1_1") (pintype "passive"))
      (node (ref "U27") (pin "4") (pinfunction "XTAL2_4") (pintype "input"))
    )
    (net (code "260") (name "Net-(VREG1-IN)") (class "Default")
      (node (ref "C100") (pin "1") (pinfunction "1_1") (pintype "passive"))
      (node (ref "C101") (pin "1") (pinfunction "1_1") (pintype "passive"))
      (node (ref "D3") (pin "C") (pinfunction "C_C") (pintype "passive"))
      (node (ref "J24") (pin "2") (pinfunction "2_2") (pintype "bidirectional"))
      (node (ref "VREG1") (pin "1") (pinfunction "IN_1") (pintype "input"))
    )
    (net (code "261") (name "Net-(X2-GRNC)") (class "Default")
      (node (ref "ER117") (pin "2") (pinfunction "2_2") (pintype "passive"))
      (node (ref "X2") (pin "10") (pinfunction "GRNC_10") (pintype "passive"))
    )
    (net (code "262") (name "Net-(X2-RCT)") (class "Default")
      (node (ref "EC40") (pin "1") (pinfunction "1_1") (pintype "passive"))
      (node (ref "ER122") (pin "2") (pinfunction "2_2") (pintype "passive"))
      (node (ref "X2") (pin "4") (pinfunction "TCT_4") (pintype "passive"))
      (node (ref "X2") (pin "5") (pinfunction "RCT_5") (pintype "passive"))
    )
    (net (code "263") (name "Net-(X2-YELC)") (class "Default")
      (node (ref "ER115") (pin "2") (pinfunction "2_2") (pintype "passive"))
      (node (ref "X2") (pin "11") (pinfunction "YELC_11") (pintype "passive"))
    )
    (net (code "264") (name "Net-(X10A-SK)") (class "Default")
      (node (ref "J11") (pin "1") (pinfunction "1_1") (pintype "bidirectional"))
      (node (ref "J12") (pin "1") (pinfunction "1_1") (pintype "bidirectional"))
      (node (ref "R181") (pin "1") (pinfunction "1_1") (pintype "passive"))
      (node (ref "R214") (pin "1") (pinfunction "1_1") (pintype "passive"))
      (node (ref "X10") (pin "1") (pinfunction "SK_1") (pintype "passive"))
    )
    (net (code "265") (name "Net-(X10C-SK)") (class "Default")
      (node (ref "J21") (pin "1") (pinfunction "1_1") (pintype "bidirectional"))
      (node (ref "J22") (pin "1") (pinfunction "1_1") (pintype "bidirectional"))
      (node (ref "R182") (pin "1") (pinfunction "1_1") (pintype "passive"))
      (node (ref "R224") (pin "1") (pinfunction "1_1") (pintype "passive"))
      (node (ref "X10") (pin "3") (pinfunction "SK_3") (pintype "passive"))
    )
    (net (code "266") (name "Net-(X11A-SK)") (class "Default")
      (node (ref "J31") (pin "1") (pinfunction "1_1") (pintype "bidirectional"))
      (node (ref "J32") (pin "1") (pinfunction "1_1") (pintype "bidirectional"))
      (node (ref "R183") (pin "1") (pinfunction "1_1") (pintype "passive"))
      (node (ref "R234") (pin "1") (pinfunction "1_1") (pintype "passive"))
      (node (ref "X11") (pin "1") (pinfunction "SK_1") (pintype "passive"))
    )
    (net (code "267") (name "Net-(X11C-SK)") (class "Default")
      (node (ref "J41") (pin "1") (pinfunction "1_1") (pintype "bidirectional"))
      (node (ref "J42") (pin "1") (pinfunction "1_1") (pintype "bidirectional"))
      (node (ref "R184") (pin "1") (pinfunction "1_1") (pintype "passive"))
      (node (ref "R244") (pin "1") (pinfunction "1_1") (pintype "passive"))
      (node (ref "X11") (pin "3") (pinfunction "SK_3") (pintype "passive"))
    )
    (net (code "268") (name "Net-(X12A-SK)") (class "Default")
      (node (ref "J51") (pin "1") (pinfunction "1_1") (pintype "bidirectional"))
      (node (ref "J52") (pin "1") (pinfunction "1_1") (pintype "bidirectional"))
      (node (ref "R185") (pin "1") (pinfunction "1_1") (pintype "passive"))
      (node (ref "R254") (pin "1") (pinfunction "1_1") (pintype "passive"))
      (node (ref "X12") (pin "1") (pinfunction "SK_1") (pintype "passive"))
    )
    (net (code "269") (name "Net-(X12C-SK)") (class "Default")
      (node (ref "J61") (pin "1") (pinfunction "1_1") (pintype "bidirectional"))
      (node (ref "J62") (pin "1") (pinfunction "1_1") (pintype "bidirectional"))
      (node (ref "R186") (pin "1") (pinfunction "1_1") (pintype "passive"))
      (node (ref "R264") (pin "1") (pinfunction "1_1") (pintype "passive"))
      (node (ref "X12") (pin "3") (pinfunction "SK_3") (pintype "passive"))
    )
    (net (code "270") (name "Net-(X41B-1)") (class "Default")
      (node (ref "F402") (pin "1") (pinfunction "1_1") (pintype "passive"))
      (node (ref "GDT1") (pin "1") (pinfunction "1_1") (pintype "passive"))
      (node (ref "X41") (pin "2") (pinfunction "1_2") (pintype "passive"))
    )
    (net (code "271") (name "Net-(Y7-1)") (class "Default")
      (node (ref "EC41") (pin "1") (pinfunction "1_1") (pintype "passive"))
      (node (ref "ER127") (pin "2") (pinfunction "2_2") (pintype "passive"))
      (node (ref "Y7") (pin "P$1") (pinfunction "1_P$1") (pintype "passive"))
    )
    (net (code "272") (name "Net-(Y7-2)") (class "Default")
      (node (ref "EC42") (pin "1") (pinfunction "1_1") (pintype "passive"))
      (node (ref "ER125") (pin "2") (pinfunction "2_2") (pintype "passive"))
      (node (ref "ER126") (pin "2") (pinfunction "2_2") (pintype "passive"))
      (node (ref "Y7") (pin "P$2") (pinfunction "2_P$2") (pintype "passive"))
    )
    (net (code "273") (name "SYS_ADC_1P8V") (class "Default")
      (node (ref "C10") (pin "1") (pinfunction "1_1") (pintype "passive"))
      (node (ref "IC14") (pin "3") (pinfunction "+IN_3") (pintype "input"))
      (node (ref "IC14") (pin "5") (pinfunction "+IN_5") (pintype "input"))
      (node (ref "R33") (pin "2") (pinfunction "2_2") (pintype "passive"))
      (node (ref "U1") (pin "Y12") (pinfunction "SYS_ADC_1P8V_Y12") (pintype "bidirectional"))
    )
    (net (code "274") (name "SYS_RTC_1P8V") (class "Default")
      (node (ref "Q1") (pin "C") (pinfunction "C_C") (pintype "passive"))
      (node (ref "R15") (pin "1") (pinfunction "1_1") (pintype "passive"))
      (node (ref "TP14") (pin "TP") (pinfunction "TP_TP") (pintype "input"))
      (node (ref "U1") (pin "K13") (pinfunction "SYS_RTC_1P8V_K13") (pintype "power_in"))
      (node (ref "U1") (pin "K14") (pinfunction "SYS_RTC_1P8V_K14") (pintype "power_in"))
      (node (ref "U1") (pin "L13") (pinfunction "SYS_RTC_1P8V_L13") (pintype "power_in"))
      (node (ref "U1") (pin "L14") (pinfunction "SYS_RTC_1P8V_L14") (pintype "power_in"))
      (node (ref "U1") (pin "M13") (pinfunction "VDDS_RTC_M13") (pintype "bidirectional"))
      (node (ref "U1") (pin "M14") (pinfunction "VDDS_M14") (pintype "bidirectional"))
      (node (ref "U5") (pin "3") (pinfunction "ANODE_3") (pintype "bidirectional"))
    )
    (net (code "275") (name "SYS_VDD1_3P3V") (class "Default")
      (node (ref "C104") (pin "1") (pinfunction "1_1") (pintype "passive"))
      (node (ref "C15") (pin "1") (pinfunction "1_1") (pintype "passive"))
      (node (ref "C21") (pin "1") (pinfunction "1_1") (pintype "passive"))
      (node (ref "C22") (pin "1") (pinfunction "1_1") (pintype "passive"))
      (node (ref "C301") (pin "1") (pinfunction "1_1") (pintype "passive"))
      (node (ref "C401") (pin "1") (pinfunction "1_1") (pintype "passive"))
      (node (ref "C404") (pin "1") (pinfunction "1_1") (pintype "passive"))
      (node (ref "C6") (pin "2") (pinfunction "2_2") (pintype "passive"))
      (node (ref "C79") (pin "1") (pinfunction "1_1") (pintype "passive"))
      (node (ref "C801") (pin "1") (pinfunction "1_1") (pintype "passive"))
      (node (ref "C85") (pin "1") (pinfunction "1_1") (pintype "passive"))
      (node (ref "C87") (pin "1") (pinfunction "1_1") (pintype "passive"))
      (node (ref "C88") (pin "1") (pinfunction "1_1") (pintype "passive"))
      (node (ref "EC34") (pin "1") (pinfunction "1_1") (pintype "passive"))
      (node (ref "ER100") (pin "1") (pinfunction "1_1") (pintype "passive"))
      (node (ref "ER105") (pin "1") (pinfunction "1_1") (pintype "passive"))
      (node (ref "ER98") (pin "1") (pinfunction "1_1") (pintype "passive"))
      (node (ref "ER99") (pin "1") (pinfunction "1_1") (pintype "passive"))
      (node (ref "FB7") (pin "1") (pinfunction "1_1") (pintype "passive"))
      (node (ref "IC14") (pin "8") (pinfunction "V+_8") (pintype "power_in"))
      (node (ref "R12") (pin "2") (pinfunction "2_2") (pintype "passive"))
      (node (ref "R13") (pin "2") (pinfunction "2_2") (pintype "passive"))
      (node (ref "R163") (pin "2") (pinfunction "2_2") (pintype "passive"))
      (node (ref "R164") (pin "1") (pinfunction "1_1") (pintype "passive"))
      (node (ref "R169") (pin "2") (pinfunction "2_2") (pintype "passive"))
      (node (ref "R170") (pin "2") (pinfunction "2_2") (pintype "passive"))
      (node (ref "R22") (pin "2") (pinfunction "2_2") (pintype "passive"))
      (node (ref "R303") (pin "2") (pinfunction "2_2") (pintype "passive"))
      (node (ref "R40") (pin "2") (pinfunction "2_2") (pintype "passive"))
      (node (ref "R41") (pin "2") (pinfunction "2_2") (pintype "passive"))
      (node (ref "R70") (pin "2") (pinfunction "2_2") (pintype "passive"))
      (node (ref "R71") (pin "2") (pinfunction "2_2") (pintype "passive"))
      (node (ref "R72") (pin "2") (pinfunction "2_2") (pintype "passive"))
      (node (ref "R73") (pin "2") (pinfunction "2_2") (pintype "passive"))
      (node (ref "R74") (pin "2") (pinfunction "2_2") (pintype "passive"))
      (node (ref "R75") (pin "2") (pinfunction "2_2") (pintype "passive"))
      (node (ref "R76") (pin "2") (pinfunction "2_2") (pintype "passive"))
      (node (ref "R77") (pin "2") (pinfunction "2_2") (pintype "passive"))
      (node (ref "R78") (pin "2") (pinfunction "2_2") (pintype "passive"))
      (node (ref "R79") (pin "2") (pinfunction "2_2") (pintype "passive"))
      (node (ref "R80") (pin "2") (pinfunction "2_2") (pintype "passive"))
      (node (ref "R81") (pin "2") (pinfunction "2_2") (pintype "passive"))
      (node (ref "R82") (pin "2") (pinfunction "2_2") (pintype "passive"))
      (node (ref "R83") (pin "2") (pinfunction "2_2") (pintype "passive"))
      (node (ref "R84") (pin "2") (pinfunction "2_2") (pintype "passive"))
      (node (ref "R85") (pin "2") (pinfunction "2_2") (pintype "passive"))
      (node (ref "R86") (pin "2") (pinfunction "2_2") (pintype "passive"))
      (node (ref "R87") (pin "2") (pinfunction "2_2") (pintype "passive"))
      (node (ref "R88") (pin "2") (pinfunction "2_2") (pintype "passive"))
      (node (ref "R89") (pin "2") (pinfunction "2_2") (pintype "passive"))
      (node (ref "R90") (pin "2") (pinfunction "2_2") (pintype "passive"))
      (node (ref "R91") (pin "2") (pinfunction "2_2") (pintype "passive"))
      (node (ref "R92") (pin "2") (pinfunction "2_2") (pintype "passive"))
      (node (ref "RTC1") (pin "2") (pinfunction "VCC_2") (pintype "power_in"))
      (node (ref "S11") (pin "C") (pinfunction "C_C") (pintype "passive"))
      (node (ref "S12") (pin "C") (pinfunction "C_C") (pintype "passive"))
      (node (ref "S13") (pin "1") (pinfunction "1_1") (pintype "passive"))
      (node (ref "S13") (pin "2") (pinfunction "2_2") (pintype "passive"))
      (node (ref "S13") (pin "3") (pinfunction "3_3") (pintype "passive"))
      (node (ref "S13") (pin "4") (pinfunction "4_4") (pintype "passive"))
      (node (ref "T4") (pin "P$2") (pinfunction "2_P$2") (pintype "passive"))
      (node (ref "T4") (pin "P$3") (pinfunction "3_P$3") (pintype "passive"))
      (node (ref "TP12") (pin "TP") (pinfunction "TP_TP") (pintype "input"))
      (node (ref "U1") (pin "F8") (pinfunction "EMMC_VCC_F8") (pintype "bidirectional"))
      (node (ref "U1") (pin "F9") (pinfunction "EMMC_VCC_F9") (pintype "bidirectional"))
      (node (ref "U1") (pin "G8") (pinfunction "EMMC_VCC_G8") (pintype "bidirectional"))
      (node (ref "U1") (pin "G9") (pinfunction "EMMC_VCC_G9") (pintype "bidirectional"))
      (node (ref "U1") (pin "H14") (pinfunction "SYS_VDD1_3P3V_H14") (pintype "power_in"))
      (node (ref "U1") (pin "H15") (pinfunction "SYS_VDD1_3P3V_H15") (pintype "power_in"))
      (node (ref "U1") (pin "H7") (pinfunction "EMMC_VCCQ_H7") (pintype "bidirectional"))
      (node (ref "U1") (pin "H8") (pinfunction "EMMC_VCCQ_H8") (pintype "bidirectional"))
      (node (ref "U1") (pin "J14") (pinfunction "SYS_VDD1_3P3V_J14") (pintype "power_in"))
      (node (ref "U1") (pin "J15") (pinfunction "SYS_VDD1_3P3V_J15") (pintype "power_in"))
      (node (ref "U1") (pin "J7") (pinfunction "EMMC_VCCQ_J7") (pintype "bidirectional"))
      (node (ref "U1") (pin "J8") (pinfunction "EMMC_VCCQ_J8") (pintype "bidirectional"))
      (node (ref "U16") (pin "1") (pinfunction "VCC_1") (pintype "bidirectional"))
      (node (ref "U16") (pin "22") (pinfunction "VCC_22") (pintype "bidirectional"))
      (node (ref "U16") (pin "8") (pinfunction "VCC_8") (pintype "bidirectional"))
      (node (ref "U27") (pin "12") (pinfunction "VDDIO_12") (pintype "power_in"))
      (node (ref "U28") (pin "3") (pinfunction "VCC_3") (pintype "power_in"))
      (node (ref "U29") (pin "8") (pinfunction "VCC_8") (pintype "power_in"))
      (node (ref "U4") (pin "4") (pinfunction "VCC_4") (pintype "bidirectional"))
      (node (ref "U40") (pin "4") (pinfunction "VCC1_4") (pintype "power_in"))
      (node (ref "U6") (pin "7") (pinfunction "2OE_7") (pintype "input"))
      (node (ref "U6") (pin "8") (pinfunction "VCC_8") (pintype "power_in"))
      (node (ref "X4") (pin "5") (pinfunction "TVDD_5") (pintype "bidirectional"))
      (node (ref "X5") (pin "4") (pinfunction "VDD_4") (pintype "bidirectional"))
    )
    (net (code "276") (name "SYS_VDD2_3P3V") (class "Default")
      (node (ref "D1") (pin "1") (pinfunction "A_1") (pintype "passive"))
      (node (ref "TP13") (pin "TP") (pinfunction "TP_TP") (pintype "input"))
      (node (ref "U1") (pin "F12") (pinfunction "SYS_VDD2_3P3V_F12") (pintype "power_in"))
      (node (ref "U1") (pin "F13") (pinfunction "SYS_VDD2_3P3V_F13") (pintype "power_in"))
      (node (ref "U1") (pin "G12") (pinfunction "SYS_VDD2_3P3V_G12") (pintype "power_in"))
      (node (ref "U1") (pin "G13") (pinfunction "SYS_VDD2_3P3V_G13") (pintype "power_in"))
    )
    (net (code "277") (name "SYS_VDD3_3P3V") (class "Default")
      (node (ref "Q1") (pin "E") (pinfunction "E_E") (pintype "passive"))
      (node (ref "R20") (pin "2") (pinfunction "2_2") (pintype "passive"))
      (node (ref "R21") (pin "2") (pinfunction "2_2") (pintype "passive"))
      (node (ref "TP16") (pin "TP") (pinfunction "TP_TP") (pintype "input"))
      (node (ref "U1") (pin "K10") (pinfunction "SYS_VDD3_3P3V_K10") (pintype "power_in"))
      (node (ref "U1") (pin "K11") (pinfunction "SYS_VDD3_3P3V_K11") (pintype "power_in"))
      (node (ref "U1") (pin "L10") (pinfunction "SYS_VDD3_3P3V_L10") (pintype "power_in"))
      (node (ref "U1") (pin "L11") (pinfunction "SYS_VDD3_3P3V_L11") (pintype "power_in"))
      (node (ref "U1") (pin "L12") (pinfunction "SYS_VDD3_3P3V_L12") (pintype "power_in"))
      (node (ref "U1") (pin "L7") (pinfunction "SYS_VDD3_3P3V_L7") (pintype "power_in"))
      (node (ref "U1") (pin "L8") (pinfunction "SYS_VDD3_3P3V_L8") (pintype "power_in"))
      (node (ref "U1") (pin "L9") (pinfunction "SYS_VDD3_3P3V_L9") (pintype "power_in"))
      (node (ref "U1") (pin "M10") (pinfunction "VDDSHV2_M10") (pintype "power_in"))
      (node (ref "U1") (pin "M11") (pinfunction "VDDSHV1_M11") (pintype "power_in"))
      (node (ref "U1") (pin "M12") (pinfunction "VDDSHV6_M12") (pintype "power_in"))
      (node (ref "U1") (pin "M7") (pinfunction "VDDSHV4_M7") (pintype "power_in"))
      (node (ref "U1") (pin "M8") (pinfunction "VDDSHV5_M8") (pintype "power_in"))
      (node (ref "U1") (pin "M9") (pinfunction "VDDSHV3_M9") (pintype "power_in"))
    )
    (net (code "278") (name "SYS_VDD_1P8V") (class "Default")
      (node (ref "TP15") (pin "TP") (pinfunction "TP_TP") (pintype "input"))
      (node (ref "U1") (pin "N10") (pinfunction "SYS_VDD_1P8V_N10") (pintype "power_in"))
      (node (ref "U1") (pin "N11") (pinfunction "SYS_VDD_1P8V_N11") (pintype "power_in"))
      (node (ref "U1") (pin "N12") (pinfunction "SYS_VDD_1P8V_N12") (pintype "power_in"))
      (node (ref "U1") (pin "N13") (pinfunction "SYS_VDD_1P8V_N13") (pintype "power_in"))
      (node (ref "U1") (pin "N14") (pinfunction "SYS_VDD_1P8V_N14") (pintype "power_in"))
      (node (ref "U1") (pin "N7") (pinfunction "SYS_VDD_1P8V_N7") (pintype "power_in"))
      (node (ref "U1") (pin "N8") (pinfunction "SYS_VDD_1P8V_N8") (pintype "power_in"))
      (node (ref "U1") (pin "N9") (pinfunction "SYS_VDD_1P8V_N9") (pintype "power_in"))
      (node (ref "U1") (pin "P10") (pinfunction "SYS_VDD_1P8V_P10") (pintype "power_in"))
      (node (ref "U1") (pin "P11") (pinfunction "SYS_VDD_1P8V_P11") (pintype "power_in"))
    )
    (net (code "279") (name "SYS_VOUT") (class "Default")
      (node (ref "C4") (pin "1") (pinfunction "1_1") (pintype "passive"))
      (node (ref "TP11") (pin "TP") (pinfunction "TP_TP") (pintype "input"))
      (node (ref "U1") (pin "F14") (pinfunction "SYS_VOUT_F14") (pintype "power_in"))
      (node (ref "U1") (pin "F15") (pinfunction "SYS_VOUT_F15") (pintype "power_in"))
      (node (ref "U1") (pin "G14") (pinfunction "SYS_VOUT_G14") (pintype "power_in"))
      (node (ref "U1") (pin "G15") (pinfunction "SYS_VOUT_G15") (pintype "power_in"))
    )
    (net (code "280") (name "VDD_5V") (class "Default")
      (node (ref "C102") (pin "1") (pinfunction "1_1") (pintype "passive"))
      (node (ref "C11") (pin "+") (pinfunction "+_+") (pintype "passive"))
      (node (ref "L2") (pin "2") (pinfunction "2_2") (pintype "passive"))
      (node (ref "U1") (pin "C18") (pinfunction "VIN_AC_C18") (pintype "power_in"))
      (node (ref "U1") (pin "C19") (pinfunction "VIN_AC_C19") (pintype "power_in"))
      (node (ref "U1") (pin "C20") (pinfunction "VIN_AC_C20") (pintype "power_in"))
      (node (ref "VREG1") (pin "4") (pinfunction "FB_4") (pintype "input"))
    )
    (net (code "281") (name "VDD_BAT") (class "Default")
      (node (ref "TP5") (pin "P$1") (pinfunction "TP_P$1") (pintype "bidirectional"))
      (node (ref "U1") (pin "D18") (pinfunction "VIN_BAT_D18") (pintype "power_in"))
      (node (ref "U1") (pin "D19") (pinfunction "VIN_BAT_D19") (pintype "power_in"))
      (node (ref "U1") (pin "D20") (pinfunction "VIN_BAT_D20") (pintype "power_in"))
    )
    (net (code "282") (name "VDD_ETH_PHY") (class "Default")
      (node (ref "EC30") (pin "1") (pinfunction "1_1") (pintype "passive"))
      (node (ref "EC31") (pin "1") (pinfunction "1_1") (pintype "passive"))
      (node (ref "EC32") (pin "1") (pinfunction "1_1") (pintype "passive"))
      (node (ref "ER106") (pin "1") (pinfunction "1_1") (pintype "passive"))
      (node (ref "ER107") (pin "1") (pinfunction "1_1") (pintype "passive"))
      (node (ref "ER108") (pin "1") (pinfunction "1_1") (pintype "passive"))
      (node (ref "ER109") (pin "1") (pinfunction "1_1") (pintype "passive"))
      (node (ref "ER122") (pin "1") (pinfunction "1_1") (pintype "passive"))
      (node (ref "FB7") (pin "2") (pinfunction "2_2") (pintype "passive"))
      (node (ref "U27") (pin "1") (pinfunction "VDD2A_1") (pintype "power_in"))
      (node (ref "U27") (pin "27") (pinfunction "VDD1A_27") (pintype "power_in"))
    )
    (net (code "283") (name "VDD_USB_5V") (class "Default")
      (node (ref "C3") (pin "1") (pinfunction "1_1") (pintype "passive"))
      (node (ref "R10") (pin "2") (pinfunction "2_2") (pintype "passive"))
      (node (ref "U1") (pin "B18") (pinfunction "VIN_USB_B18") (pintype "power_in"))
      (node (ref "U1") (pin "B19") (pinfunction "VIN_USB_B19") (pintype "power_in"))
      (node (ref "U1") (pin "B20") (pinfunction "VIN_USB_B20") (pintype "power_in"))
      (node (ref "U1") (pin "K1") (pinfunction "USB0_VBUS_K1") (pintype "bidirectional"))
      (node (ref "U2") (pin "6") (pinfunction "VBUS_6") (pintype "passive"))
    )
    (net (code "284") (name "unconnected-(F401-Pad2)") (class "Default")
      (node (ref "F401") (pin "2") (pinfunction "2_2") (pintype "passive"))
    )
    (net (code "285") (name "unconnected-(F402-Pad2)") (class "Default")
      (node (ref "F402") (pin "2") (pinfunction "2_2") (pintype "passive"))
    )
    (net (code "286") (name "unconnected-(FUD1-PadP$1)") (class "Default")
      (node (ref "FUD1") (pin "P$1") (pinfunction "P$1_P$1") (pintype "no_connect"))
    )
    (net (code "287") (name "unconnected-(FUD2-PadP$1)") (class "Default")
      (node (ref "FUD2") (pin "P$1") (pinfunction "P$1_P$1") (pintype "no_connect"))
    )
    (net (code "288") (name "unconnected-(FUD3-PadP$1)") (class "Default")
      (node (ref "FUD3") (pin "P$1") (pinfunction "P$1_P$1") (pintype "no_connect"))
    )
    (net (code "289") (name "unconnected-(FUD4-PadP$1)") (class "Default")
      (node (ref "FUD4") (pin "P$1") (pinfunction "P$1_P$1") (pintype "no_connect"))
    )
    (net (code "290") (name "unconnected-(FUD5-PadP$1)") (class "Default")
      (node (ref "FUD5") (pin "P$1") (pinfunction "P$1_P$1") (pintype "no_connect"))
    )
    (net (code "291") (name "unconnected-(FUD6-PadP$1)") (class "Default")
      (node (ref "FUD6") (pin "P$1") (pinfunction "P$1_P$1") (pintype "no_connect"))
    )
    (net (code "292") (name "unconnected-(G1-+-Pad+@1)") (class "Default")
      (node (ref "G1") (pin "+@1") (pinfunction "+_+@1") (pintype "passive"))
    )
    (net (code "293") (name "unconnected-(IC2-I6-Pad6)") (class "Default")
      (node (ref "IC2") (pin "6") (pinfunction "I6_6") (pintype "input"))
    )
    (net (code "294") (name "unconnected-(IC2-I7-Pad7)") (class "Default")
      (node (ref "IC2") (pin "7") (pinfunction "I7_7") (pintype "input"))
    )
    (net (code "295") (name "unconnected-(IC2-O6-Pad11)") (class "Default")
      (node (ref "IC2") (pin "11") (pinfunction "O6_11") (pintype "open_collector"))
    )
    (net (code "296") (name "unconnected-(IC2-O7-Pad10)") (class "Default")
      (node (ref "IC2") (pin "10") (pinfunction "O7_10") (pintype "open_collector"))
    )
    (net (code "297") (name "unconnected-(IC4A-~{QH}-Pad7)") (class "Default")
      (node (ref "IC4") (pin "7") (pinfunction "~{QH}_7") (pintype "output"))
    )
    (net (code "298") (name "unconnected-(IC5A-~{QH}-Pad7)") (class "Default")
      (node (ref "IC5") (pin "7") (pinfunction "~{QH}_7") (pintype "output"))
    )
    (net (code "299") (name "unconnected-(K1B-O-PadNC)") (class "Default")
      (node (ref "K1") (pin "NC") (pinfunction "O_NC") (pintype "passive"))
    )
    (net (code "300") (name "unconnected-(K2B-O-PadNC)") (class "Default")
      (node (ref "K2") (pin "NC") (pinfunction "O_NC") (pintype "passive"))
    )
    (net (code "301") (name "unconnected-(K3B-O-PadNC)") (class "Default")
      (node (ref "K3") (pin "NC") (pinfunction "O_NC") (pintype "passive"))
    )
    (net (code "302") (name "unconnected-(K4B-O-PadNC)") (class "Default")
      (node (ref "K4") (pin "NC") (pinfunction "O_NC") (pintype "passive"))
    )
    (net (code "303") (name "unconnected-(K5B-O-PadNC)") (class "Default")
      (node (ref "K5") (pin "NC") (pinfunction "O_NC") (pintype "passive"))
    )
    (net (code "304") (name "unconnected-(RTC1-SQW-Pad3)") (class "Default")
      (node (ref "RTC1") (pin "3") (pinfunction "SQW_3") (pintype "output"))
    )
    (net (code "305") (name "unconnected-(U1A-VDDS_RTC-PadU14)") (class "Default")
      (node (ref "U1") (pin "U14") (pinfunction "VDDS_RTC_U14") (pintype "bidirectional"))
    )
    (net (code "306") (name "unconnected-(U1B-USB0_CE-PadL3)") (class "Default")
      (node (ref "U1") (pin "L3") (pinfunction "USB0_CE_L3") (pintype "bidirectional"))
    )
    (net (code "307") (name "unconnected-(U1B-USB1_CE-PadJ3)") (class "Default")
      (node (ref "U1") (pin "J3") (pinfunction "USB1_CE_J3") (pintype "bidirectional"))
    )
    (net (code "308") (name "unconnected-(U1B-USB1_DM-PadH2)") (class "Default")
      (node (ref "U1") (pin "H2") (pinfunction "USB1_DM_H2") (pintype "bidirectional"))
    )
    (net (code "309") (name "unconnected-(U1B-USB1_DP-PadJ2)") (class "Default")
      (node (ref "U1") (pin "J2") (pinfunction "USB1_DP_J2") (pintype "bidirectional"))
    )
    (net (code "310") (name "unconnected-(U1B-USB1_DRVVBUS-PadH3)") (class "Default")
      (node (ref "U1") (pin "H3") (pinfunction "USB1_DRVVBUS_H3") (pintype "bidirectional"))
    )
    (net (code "311") (name "unconnected-(U1B-USB1_ID-PadJ1)") (class "Default")
      (node (ref "U1") (pin "J1") (pinfunction "USB1_ID_J1") (pintype "bidirectional"))
    )
    (net (code "312") (name "unconnected-(U1B-USB1_VBUS-PadH1)") (class "Default")
      (node (ref "U1") (pin "H1") (pinfunction "USB1_VBUS_H1") (pintype "bidirectional"))
    )
    (net (code "313") (name "unconnected-(U1C-EMMC_RSTN-PadA4)") (class "Default")
      (node (ref "U1") (pin "A4") (pinfunction "EMMC_RSTN_A4") (pintype "bidirectional"))
    )
    (net (code "314") (name "unconnected-(U1C-GPMC_A0-PadA13)") (class "Default")
      (node (ref "U1") (pin "A13") (pinfunction "GPMC_A0_A13") (pintype "bidirectional"))
    )
    (net (code "315") (name "unconnected-(U1C-GPMC_A4-PadB12)") (class "Default")
      (node (ref "U1") (pin "B12") (pinfunction "GPMC_A4_B12") (pintype "bidirectional"))
    )
    (net (code "316") (name "unconnected-(U1C-GPMC_A9-PadA10)") (class "Default")
      (node (ref "U1") (pin "A10") (pinfunction "GPMC_A9_A10") (pintype "bidirectional"))
    )
    (net (code "317") (name "unconnected-(U1C-GPMC_A10-PadB10)") (class "Default")
      (node (ref "U1") (pin "B10") (pinfunction "GPMC_A10_B10") (pintype "bidirectional"))
    )
    (net (code "318") (name "unconnected-(U1C-GPMC_A11-PadC10)") (class "Default")
      (node (ref "U1") (pin "C10") (pinfunction "GPMC_A11_C10") (pintype "bidirectional"))
    )
    (net (code "319") (name "unconnected-(U1C-GPMC_AD10-PadB16)") (class "Default")
      (node (ref "U1") (pin "B16") (pinfunction "GPMC_AD10_B16") (pintype "bidirectional"))
    )
    (net (code "320") (name "unconnected-(U1C-GPMC_AD11-PadA16)") (class "Default")
      (node (ref "U1") (pin "A16") (pinfunction "GPMC_AD11_A16") (pintype "bidirectional"))
    )
    (net (code "321") (name "unconnected-(U1C-GPMC_ADVN_ALE-PadL19)") (class "Default")
      (node (ref "U1") (pin "L19") (pinfunction "GPMC_ADVN_ALE_L19") (pintype "bidirectional"))
    )
    (net (code "322") (name "unconnected-(U1C-GPMC_BEN0_CLE-PadL20)") (class "Default")
      (node (ref "U1") (pin "L20") (pinfunction "GPMC_BEN0_CLE_L20") (pintype "bidirectional"))
    )
    (net (code "323") (name "unconnected-(U1C-GPMC_CLK-PadA14)") (class "Default")
      (node (ref "U1") (pin "A14") (pinfunction "GPMC_CLK_A14") (pintype "bidirectional"))
    )
    (net (code "324") (name "unconnected-(U1C-GPMC_OEN_REN-PadK19)") (class "Default")
      (node (ref "U1") (pin "K19") (pinfunction "GPMC_OEN_REN_K19") (pintype "bidirectional"))
    )
    (net (code "325") (name "unconnected-(U1C-GPMC_WEN-PadK18)") (class "Default")
      (node (ref "U1") (pin "K18") (pinfunction "GPMC_WEN_K18") (pintype "bidirectional"))
    )
    (net (code "326") (name "unconnected-(U1C-MCASP0_ACLKR-PadY15)") (class "Default")
      (node (ref "U1") (pin "Y15") (pinfunction "MCASP0_ACLKR_Y15") (pintype "bidirectional"))
    )
    (net (code "327") (name "unconnected-(U1D-RMII1_REF_CLK-PadM3)") (class "Default")
      (node (ref "U1") (pin "M3") (pinfunction "RMII1_REF_CLK_M3") (pintype "bidirectional"))
    )
    (net (code "328") (name "unconnected-(U1F-CAP_VDD_RTC-PadV13)") (class "Default")
      (node (ref "U1") (pin "V13") (pinfunction "CAP_VDD_RTC_V13") (pintype "bidirectional"))
    )
    (net (code "329") (name "unconnected-(U1G-NC-PadA2)") (class "Default")
      (node (ref "U1") (pin "A2") (pinfunction "NC_A2") (pintype "bidirectional"))
    )
    (net (code "330") (name "unconnected-(U1G-NC-PadA3)") (class "Default")
      (node (ref "U1") (pin "A3") (pinfunction "NC_A3") (pintype "bidirectional"))
    )
    (net (code "331") (name "unconnected-(U1G-NC-PadA5)") (class "Default")
      (node (ref "U1") (pin "A5") (pinfunction "NC_A5") (pintype "bidirectional"))
    )
    (net (code "332") (name "unconnected-(U1G-NC-PadA6)") (class "Default")
      (node (ref "U1") (pin "A6") (pinfunction "NC_A6") (pintype "bidirectional"))
    )
    (net (code "333") (name "unconnected-(U1G-NC-PadA7)") (class "Default")
      (node (ref "U1") (pin "A7") (pinfunction "NC_A7") (pintype "bidirectional"))
    )
    (net (code "334") (name "unconnected-(U1G-NC-PadA8)") (class "Default")
      (node (ref "U1") (pin "A8") (pinfunction "NC_A8") (pintype "bidirectional"))
    )
    (net (code "335") (name "unconnected-(U1G-NC-PadB1)") (class "Default")
      (node (ref "U1") (pin "B1") (pinfunction "NC_B1") (pintype "bidirectional"))
    )
    (net (code "336") (name "unconnected-(U1G-NC-PadB2)") (class "Default")
      (node (ref "U1") (pin "B2") (pinfunction "NC_B2") (pintype "bidirectional"))
    )
    (net (code "337") (name "unconnected-(U1G-NC-PadB3)") (class "Default")
      (node (ref "U1") (pin "B3") (pinfunction "NC_B3") (pintype "bidirectional"))
    )
    (net (code "338") (name "unconnected-(U1G-NC-PadB4)") (class "Default")
      (node (ref "U1") (pin "B4") (pinfunction "NC_B4") (pintype "bidirectional"))
    )
    (net (code "339") (name "unconnected-(U1G-NC-PadB5)") (class "Default")
      (node (ref "U1") (pin "B5") (pinfunction "NC_B5") (pintype "bidirectional"))
    )
    (net (code "340") (name "unconnected-(U1G-NC-PadB6)") (class "Default")
      (node (ref "U1") (pin "B6") (pinfunction "NC_B6") (pintype "bidirectional"))
    )
    (net (code "341") (name "unconnected-(U1G-NC-PadB7)") (class "Default")
      (node (ref "U1") (pin "B7") (pinfunction "NC_B7") (pintype "bidirectional"))
    )
    (net (code "342") (name "unconnected-(U1G-NC-PadB8)") (class "Default")
      (node (ref "U1") (pin "B8") (pinfunction "NC_B8") (pintype "bidirectional"))
    )
    (net (code "343") (name "unconnected-(U1G-NC-PadC1)") (class "Default")
      (node (ref "U1") (pin "C1") (pinfunction "NC_C1") (pintype "bidirectional"))
    )
    (net (code "344") (name "unconnected-(U1G-NC-PadC2)") (class "Default")
      (node (ref "U1") (pin "C2") (pinfunction "NC_C2") (pintype "bidirectional"))
    )
    (net (code "345") (name "unconnected-(U1G-NC-PadC3)") (class "Default")
      (node (ref "U1") (pin "C3") (pinfunction "NC_C3") (pintype "bidirectional"))
    )
    (net (code "346") (name "unconnected-(U1G-NC-PadC4)") (class "Default")
      (node (ref "U1") (pin "C4") (pinfunction "NC_C4") (pintype "bidirectional"))
    )
    (net (code "347") (name "unconnected-(U1G-NC-PadC5)") (class "Default")
      (node (ref "U1") (pin "C5") (pinfunction "NC_C5") (pintype "bidirectional"))
    )
    (net (code "348") (name "unconnected-(U1G-NC-PadC6)") (class "Default")
      (node (ref "U1") (pin "C6") (pinfunction "NC_C6") (pintype "bidirectional"))
    )
    (net (code "349") (name "unconnected-(U1G-NC-PadC7)") (class "Default")
      (node (ref "U1") (pin "C7") (pinfunction "NC_C7") (pintype "bidirectional"))
    )
    (net (code "350") (name "unconnected-(U1G-NC-PadC8)") (class "Default")
      (node (ref "U1") (pin "C8") (pinfunction "NC_C8") (pintype "bidirectional"))
    )
    (net (code "351") (name "unconnected-(U1G-NC-PadD1)") (class "Default")
      (node (ref "U1") (pin "D1") (pinfunction "NC_D1") (pintype "bidirectional"))
    )
    (net (code "352") (name "unconnected-(U1G-NC-PadD2)") (class "Default")
      (node (ref "U1") (pin "D2") (pinfunction "NC_D2") (pintype "bidirectional"))
    )
    (net (code "353") (name "unconnected-(U1G-NC-PadD3)") (class "Default")
      (node (ref "U1") (pin "D3") (pinfunction "NC_D3") (pintype "bidirectional"))
    )
    (net (code "354") (name "unconnected-(U1G-NC-PadD6)") (class "Default")
      (node (ref "U1") (pin "D6") (pinfunction "NC_D6") (pintype "bidirectional"))
    )
    (net (code "355") (name "unconnected-(U1G-NC-PadD7)") (class "Default")
      (node (ref "U1") (pin "D7") (pinfunction "NC_D7") (pintype "bidirectional"))
    )
    (net (code "356") (name "unconnected-(U1G-NC-PadD8)") (class "Default")
      (node (ref "U1") (pin "D8") (pinfunction "NC_D8") (pintype "bidirectional"))
    )
    (net (code "357") (name "unconnected-(U1G-NC-PadE1)") (class "Default")
      (node (ref "U1") (pin "E1") (pinfunction "NC_E1") (pintype "bidirectional"))
    )
    (net (code "358") (name "unconnected-(U1G-NC-PadE2)") (class "Default")
      (node (ref "U1") (pin "E2") (pinfunction "NC_E2") (pintype "bidirectional"))
    )
    (net (code "359") (name "unconnected-(U1G-NC-PadE3)") (class "Default")
      (node (ref "U1") (pin "E3") (pinfunction "NC_E3") (pintype "bidirectional"))
    )
    (net (code "360") (name "unconnected-(U1G-NC-PadE18)") (class "Default")
      (node (ref "U1") (pin "E18") (pinfunction "NC_E18") (pintype "bidirectional"))
    )
    (net (code "361") (name "unconnected-(U1G-NC-PadF1)") (class "Default")
      (node (ref "U1") (pin "F1") (pinfunction "NC_F1") (pintype "bidirectional"))
    )
    (net (code "362") (name "unconnected-(U1G-NC-PadF2)") (class "Default")
      (node (ref "U1") (pin "F2") (pinfunction "NC_F2") (pintype "bidirectional"))
    )
    (net (code "363") (name "unconnected-(U1G-NC-PadF3)") (class "Default")
      (node (ref "U1") (pin "F3") (pinfunction "NC_F3") (pintype "bidirectional"))
    )
    (net (code "364") (name "unconnected-(U1G-NC-PadF4)") (class "Default")
      (node (ref "U1") (pin "F4") (pinfunction "NC_F4") (pintype "bidirectional"))
    )
    (net (code "365") (name "unconnected-(U1G-NC-PadF6)") (class "Default")
      (node (ref "U1") (pin "F6") (pinfunction "NC_F6") (pintype "bidirectional"))
    )
    (net (code "366") (name "unconnected-(U1G-NC-PadF7)") (class "Default")
      (node (ref "U1") (pin "F7") (pinfunction "NC_F7") (pintype "bidirectional"))
    )
    (net (code "367") (name "unconnected-(U1G-NC-PadF20)") (class "Default")
      (node (ref "U1") (pin "F20") (pinfunction "NC_F20") (pintype "bidirectional"))
    )
    (net (code "368") (name "unconnected-(U1G-NC-PadG1)") (class "Default")
      (node (ref "U1") (pin "G1") (pinfunction "NC_G1") (pintype "bidirectional"))
    )
    (net (code "369") (name "unconnected-(U1G-NC-PadG2)") (class "Default")
      (node (ref "U1") (pin "G2") (pinfunction "NC_G2") (pintype "bidirectional"))
    )
    (net (code "370") (name "unconnected-(U1G-NC-PadG3)") (class "Default")
      (node (ref "U1") (pin "G3") (pinfunction "NC_G3") (pintype "bidirectional"))
    )
    (net (code "371") (name "unconnected-(U1G-NC-PadG4)") (class "Default")
      (node (ref "U1") (pin "G4") (pinfunction "NC_G4") (pintype "bidirectional"))
    )
    (net (code "372") (name "unconnected-(U1G-NC-PadG6)") (class "Default")
      (node (ref "U1") (pin "G6") (pinfunction "NC_G6") (pintype "bidirectional"))
    )
    (net (code "373") (name "unconnected-(U1G-NC-PadG7)") (class "Default")
      (node (ref "U1") (pin "G7") (pinfunction "NC_G7") (pintype "bidirectional"))
    )
    (net (code "374") (name "unconnected-(U1G-NC-PadG10)") (class "Default")
      (node (ref "U1") (pin "G10") (pinfunction "NC_G10") (pintype "bidirectional"))
    )
    (net (code "375") (name "unconnected-(U1G-NC-PadG11)") (class "Default")
      (node (ref "U1") (pin "G11") (pinfunction "NC_G11") (pintype "bidirectional"))
    )
    (net (code "376") (name "unconnected-(U1G-NC-PadG18)") (class "Default")
      (node (ref "U1") (pin "G18") (pinfunction "NC_G18") (pintype "bidirectional"))
    )
    (net (code "377") (name "unconnected-(U1G-NC-PadG19)") (class "Default")
      (node (ref "U1") (pin "G19") (pinfunction "NC_G19") (pintype "bidirectional"))
    )
    (net (code "378") (name "unconnected-(U1G-NC-PadG20)") (class "Default")
      (node (ref "U1") (pin "G20") (pinfunction "NC_G20") (pintype "bidirectional"))
    )
    (net (code "379") (name "unconnected-(U1G-NC-PadH4)") (class "Default")
      (node (ref "U1") (pin "H4") (pinfunction "NC_H4") (pintype "bidirectional"))
    )
    (net (code "380") (name "unconnected-(U1G-NC-PadH6)") (class "Default")
      (node (ref "U1") (pin "H6") (pinfunction "NC_H6") (pintype "bidirectional"))
    )
    (net (code "381") (name "unconnected-(U1G-NC-PadH9)") (class "Default")
      (node (ref "U1") (pin "H9") (pinfunction "NC_H9") (pintype "bidirectional"))
    )
    (net (code "382") (name "unconnected-(U1G-NC-PadH10)") (class "Default")
      (node (ref "U1") (pin "H10") (pinfunction "NC_H10") (pintype "bidirectional"))
    )
    (net (code "383") (name "unconnected-(U1G-NC-PadH11)") (class "Default")
      (node (ref "U1") (pin "H11") (pinfunction "NC_H11") (pintype "bidirectional"))
    )
    (net (code "384") (name "unconnected-(U1G-NC-PadH12)") (class "Default")
      (node (ref "U1") (pin "H12") (pinfunction "NC_H12") (pintype "bidirectional"))
    )
    (net (code "385") (name "unconnected-(U1G-NC-PadH13)") (class "Default")
      (node (ref "U1") (pin "H13") (pinfunction "NC_H13") (pintype "bidirectional"))
    )
    (net (code "386") (name "unconnected-(U1G-NC-PadH18)") (class "Default")
      (node (ref "U1") (pin "H18") (pinfunction "NC_H18") (pintype "bidirectional"))
    )
    (net (code "387") (name "unconnected-(U1G-NC-PadH19)") (class "Default")
      (node (ref "U1") (pin "H19") (pinfunction "NC_H19") (pintype "bidirectional"))
    )
    (net (code "388") (name "unconnected-(U1G-NC-PadH20)") (class "Default")
      (node (ref "U1") (pin "H20") (pinfunction "NC_H20") (pintype "bidirectional"))
    )
    (net (code "389") (name "unconnected-(U1G-NC-PadJ4)") (class "Default")
      (node (ref "U1") (pin "J4") (pinfunction "NC_J4") (pintype "bidirectional"))
    )
    (net (code "390") (name "unconnected-(U1G-NC-PadJ6)") (class "Default")
      (node (ref "U1") (pin "J6") (pinfunction "NC_J6") (pintype "bidirectional"))
    )
    (net (code "391") (name "unconnected-(U1G-NC-PadJ18)") (class "Default")
      (node (ref "U1") (pin "J18") (pinfunction "NC_J18") (pintype "bidirectional"))
    )
    (net (code "392") (name "unconnected-(U1G-NC-PadJ19)") (class "Default")
      (node (ref "U1") (pin "J19") (pinfunction "NC_J19") (pintype "bidirectional"))
    )
    (net (code "393") (name "unconnected-(U1G-NC-PadJ20)") (class "Default")
      (node (ref "U1") (pin "J20") (pinfunction "NC_J20") (pintype "bidirectional"))
    )
    (net (code "394") (name "unconnected-(U1G-NC-PadK4)") (class "Default")
      (node (ref "U1") (pin "K4") (pinfunction "NC_K4") (pintype "bidirectional"))
    )
    (net (code "395") (name "unconnected-(U1G-NC-PadL4)") (class "Default")
      (node (ref "U1") (pin "L4") (pinfunction "NC_L4") (pintype "bidirectional"))
    )
    (net (code "396") (name "unconnected-(U1G-NC-PadL17)") (class "Default")
      (node (ref "U1") (pin "L17") (pinfunction "NC_L17") (pintype "bidirectional"))
    )
    (net (code "397") (name "unconnected-(U1G-NC-PadM4)") (class "Default")
      (node (ref "U1") (pin "M4") (pinfunction "NC_M4") (pintype "bidirectional"))
    )
    (net (code "398") (name "unconnected-(U1G-NC-PadM6)") (class "Default")
      (node (ref "U1") (pin "M6") (pinfunction "NC_M6") (pintype "bidirectional"))
    )
    (net (code "399") (name "unconnected-(U1G-NC-PadM17)") (class "Default")
      (node (ref "U1") (pin "M17") (pinfunction "NC_M17") (pintype "bidirectional"))
    )
    (net (code "400") (name "unconnected-(U1G-NC-PadN4)") (class "Default")
      (node (ref "U1") (pin "N4") (pinfunction "NC_N4") (pintype "bidirectional"))
    )
    (net (code "401") (name "unconnected-(U1G-NC-PadN17)") (class "Default")
      (node (ref "U1") (pin "N17") (pinfunction "NC_N17") (pintype "bidirectional"))
    )
    (net (code "402") (name "unconnected-(U1G-NC-PadP4)") (class "Default")
      (node (ref "U1") (pin "P4") (pinfunction "NC_P4") (pintype "bidirectional"))
    )
    (net (code "403") (name "unconnected-(U1G-NC-PadP17)") (class "Default")
      (node (ref "U1") (pin "P17") (pinfunction "NC_P17") (pintype "bidirectional"))
    )
    (net (code "404") (name "unconnected-(U1G-NC-PadR4)") (class "Default")
      (node (ref "U1") (pin "R4") (pinfunction "NC_R4") (pintype "bidirectional"))
    )
    (net (code "405") (name "unconnected-(U1G-NC-PadR6)") (class "Default")
      (node (ref "U1") (pin "R6") (pinfunction "NC_R6") (pintype "bidirectional"))
    )
    (net (code "406") (name "unconnected-(U1G-NC-PadR7)") (class "Default")
      (node (ref "U1") (pin "R7") (pinfunction "NC_R7") (pintype "bidirectional"))
    )
    (net (code "407") (name "unconnected-(U1G-NC-PadR8)") (class "Default")
      (node (ref "U1") (pin "R8") (pinfunction "NC_R8") (pintype "bidirectional"))
    )
    (net (code "408") (name "unconnected-(U1G-NC-PadR13)") (class "Default")
      (node (ref "U1") (pin "R13") (pinfunction "NC_R13") (pintype "bidirectional"))
    )
    (net (code "409") (name "unconnected-(U1G-NC-PadR14)") (class "Default")
      (node (ref "U1") (pin "R14") (pinfunction "NC_R14") (pintype "bidirectional"))
    )
    (net (code "410") (name "unconnected-(U1G-NC-PadR15)") (class "Default")
      (node (ref "U1") (pin "R15") (pinfunction "NC_R15") (pintype "bidirectional"))
    )
    (net (code "411") (name "unconnected-(U1G-NC-PadR17)") (class "Default")
      (node (ref "U1") (pin "R17") (pinfunction "NC_R17") (pintype "bidirectional"))
    )
    (net (code "412") (name "unconnected-(U1G-NC-PadU11)") (class "Default")
      (node (ref "U1") (pin "U11") (pinfunction "NC_U11") (pintype "bidirectional"))
    )
    (net (code "413") (name "unconnected-(U2-N.C.-Pad5)") (class "Default")
      (node (ref "U2") (pin "5") (pinfunction "N.C._5") (pintype "no_connect"))
    )
    (net (code "414") (name "unconnected-(U16-NC-Pad7)") (class "Default")
      (node (ref "U16") (pin "7") (pinfunction "NC_7") (pintype "bidirectional"))
    )
    (net (code "415") (name "unconnected-(U16-NC-Pad10)") (class "Default")
      (node (ref "U16") (pin "10") (pinfunction "NC_10") (pintype "bidirectional"))
    )
    (net (code "416") (name "unconnected-(U16-NC-Pad11)") (class "Default")
      (node (ref "U16") (pin "11") (pinfunction "NC_11") (pintype "bidirectional"))
    )
    (net (code "417") (name "unconnected-(U16-NC-Pad13)") (class "Default")
      (node (ref "U16") (pin "13") (pinfunction "NC_13") (pintype "bidirectional"))
    )
    (net (code "418") (name "unconnected-(U16-NC-Pad14)") (class "Default")
      (node (ref "U16") (pin "14") (pinfunction "NC_14") (pintype "bidirectional"))
    )
    (net (code "419") (name "unconnected-(U16-NC-Pad15)") (class "Default")
      (node (ref "U16") (pin "15") (pinfunction "NC_15") (pintype "bidirectional"))
    )
    (net (code "420") (name "unconnected-(U16-NC-Pad16)") (class "Default")
      (node (ref "U16") (pin "16") (pinfunction "NC_16") (pintype "bidirectional"))
    )
    (net (code "421") (name "unconnected-(U16-NC-Pad25)") (class "Default")
      (node (ref "U16") (pin "25") (pinfunction "NC_25") (pintype "bidirectional"))
    )
    (net (code "422") (name "unconnected-(U16-NC-Pad26)") (class "Default")
      (node (ref "U16") (pin "26") (pinfunction "NC_26") (pintype "bidirectional"))
    )
    (net (code "423") (name "unconnected-(U16-NC-Pad27)") (class "Default")
      (node (ref "U16") (pin "27") (pinfunction "NC_27") (pintype "bidirectional"))
    )
    (net (code "424") (name "unconnected-(U16-NC-Pad28)") (class "Default")
      (node (ref "U16") (pin "28") (pinfunction "NC_28") (pintype "bidirectional"))
    )
    (net (code "425") (name "unconnected-(U16-NC-Pad31)") (class "Default")
      (node (ref "U16") (pin "31") (pinfunction "NC_31") (pintype "bidirectional"))
    )
    (net (code "426") (name "unconnected-(U16-PAD-Pad33)") (class "Default")
      (node (ref "U16") (pin "33") (pinfunction "PAD_33") (pintype "bidirectional"))
    )
    (net (code "427") (name "unconnected-(U28-S-Pad8)") (class "Default")
      (node (ref "U28") (pin "8") (pinfunction "S_8") (pintype "input"))
    )
    (net (code "428") (name "unconnected-(U40-NC-Pad10)") (class "Default")
      (node (ref "U40") (pin "10") (pinfunction "NC_10") (pintype "passive"))
    )
    (net (code "429") (name "unconnected-(VREG4-BYPASS-Pad4)") (class "Default")
      (node (ref "VREG4") (pin "4") (pinfunction "BYPASS_4") (pintype "passive"))
    )
    (net (code "430") (name "unconnected-(X2-NC-Pad7)") (class "Default")
      (node (ref "X2") (pin "7") (pinfunction "NC_7") (pintype "passive"))
    )
    (net (code "431") (name "unconnected-(X4-NC-Pad6)") (class "Default")
      (node (ref "X4") (pin "6") (pinfunction "NC_6") (pintype "bidirectional"))
    )
    (net (code "432") (name "unconnected-(X6-Pad2)") (class "Default")
      (node (ref "X6") (pin "2") (pinfunction "2_2") (pintype "bidirectional"))
    )
    (net (code "433") (name "unconnected-(X6-Pad3)") (class "Default")
      (node (ref "X6") (pin "3") (pinfunction "3_3") (pintype "bidirectional"))
    )
    (net (code "434") (name "unconnected-(X6-Pad6)") (class "Default")
      (node (ref "X6") (pin "6") (pinfunction "6_6") (pintype "bidirectional"))
    )
  )
)
